# GDPHS_VGA_-_v1_3.net
KiCad netlist of a schematic drawn in EAGLE
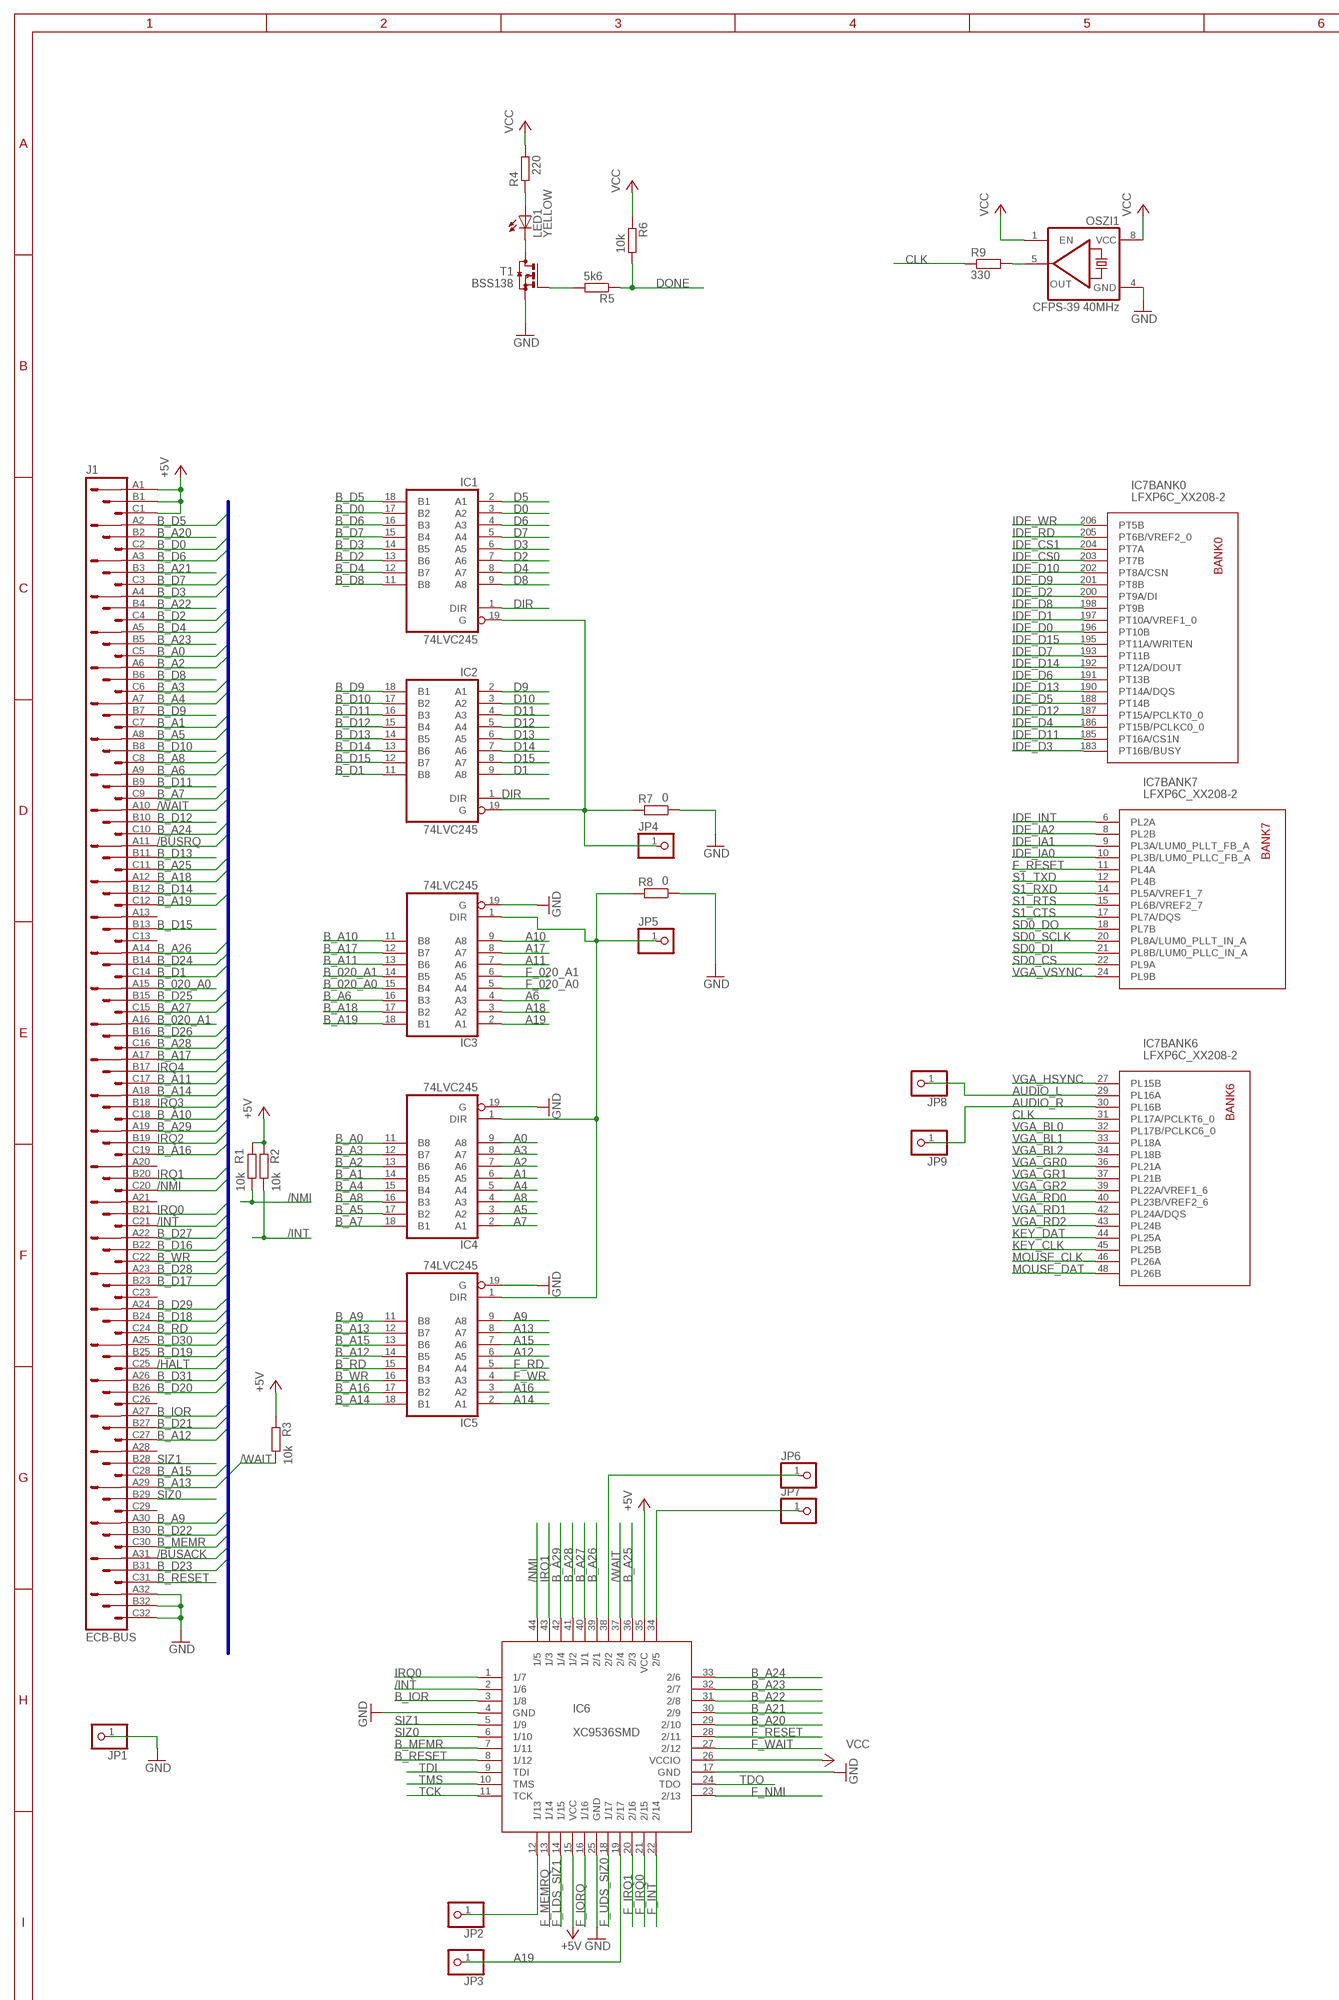
[diagram p0: schematic, sheet 1, part 1 of 2]
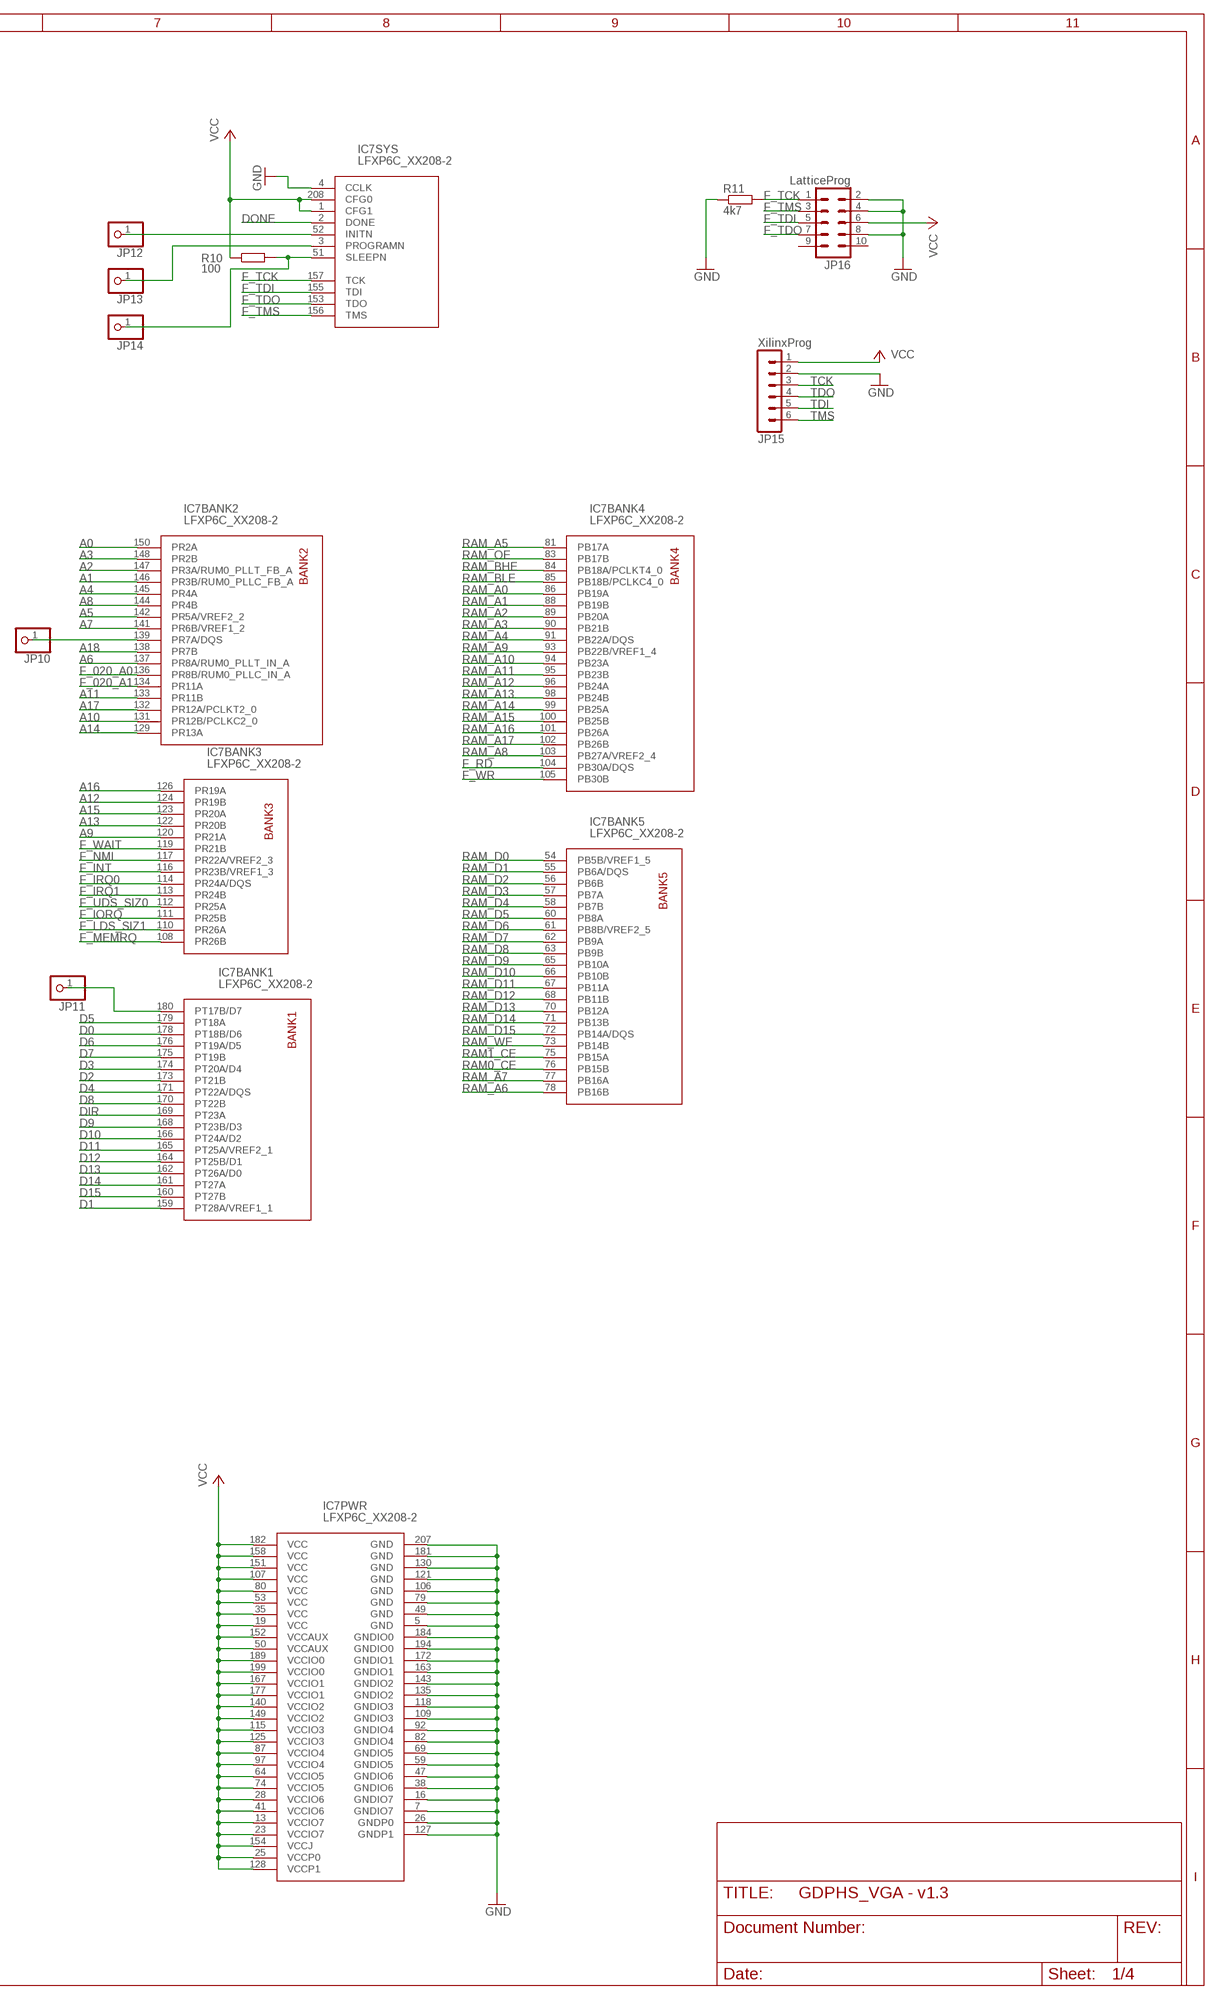
[diagram p1: schematic, sheet 1, part 2 of 2]
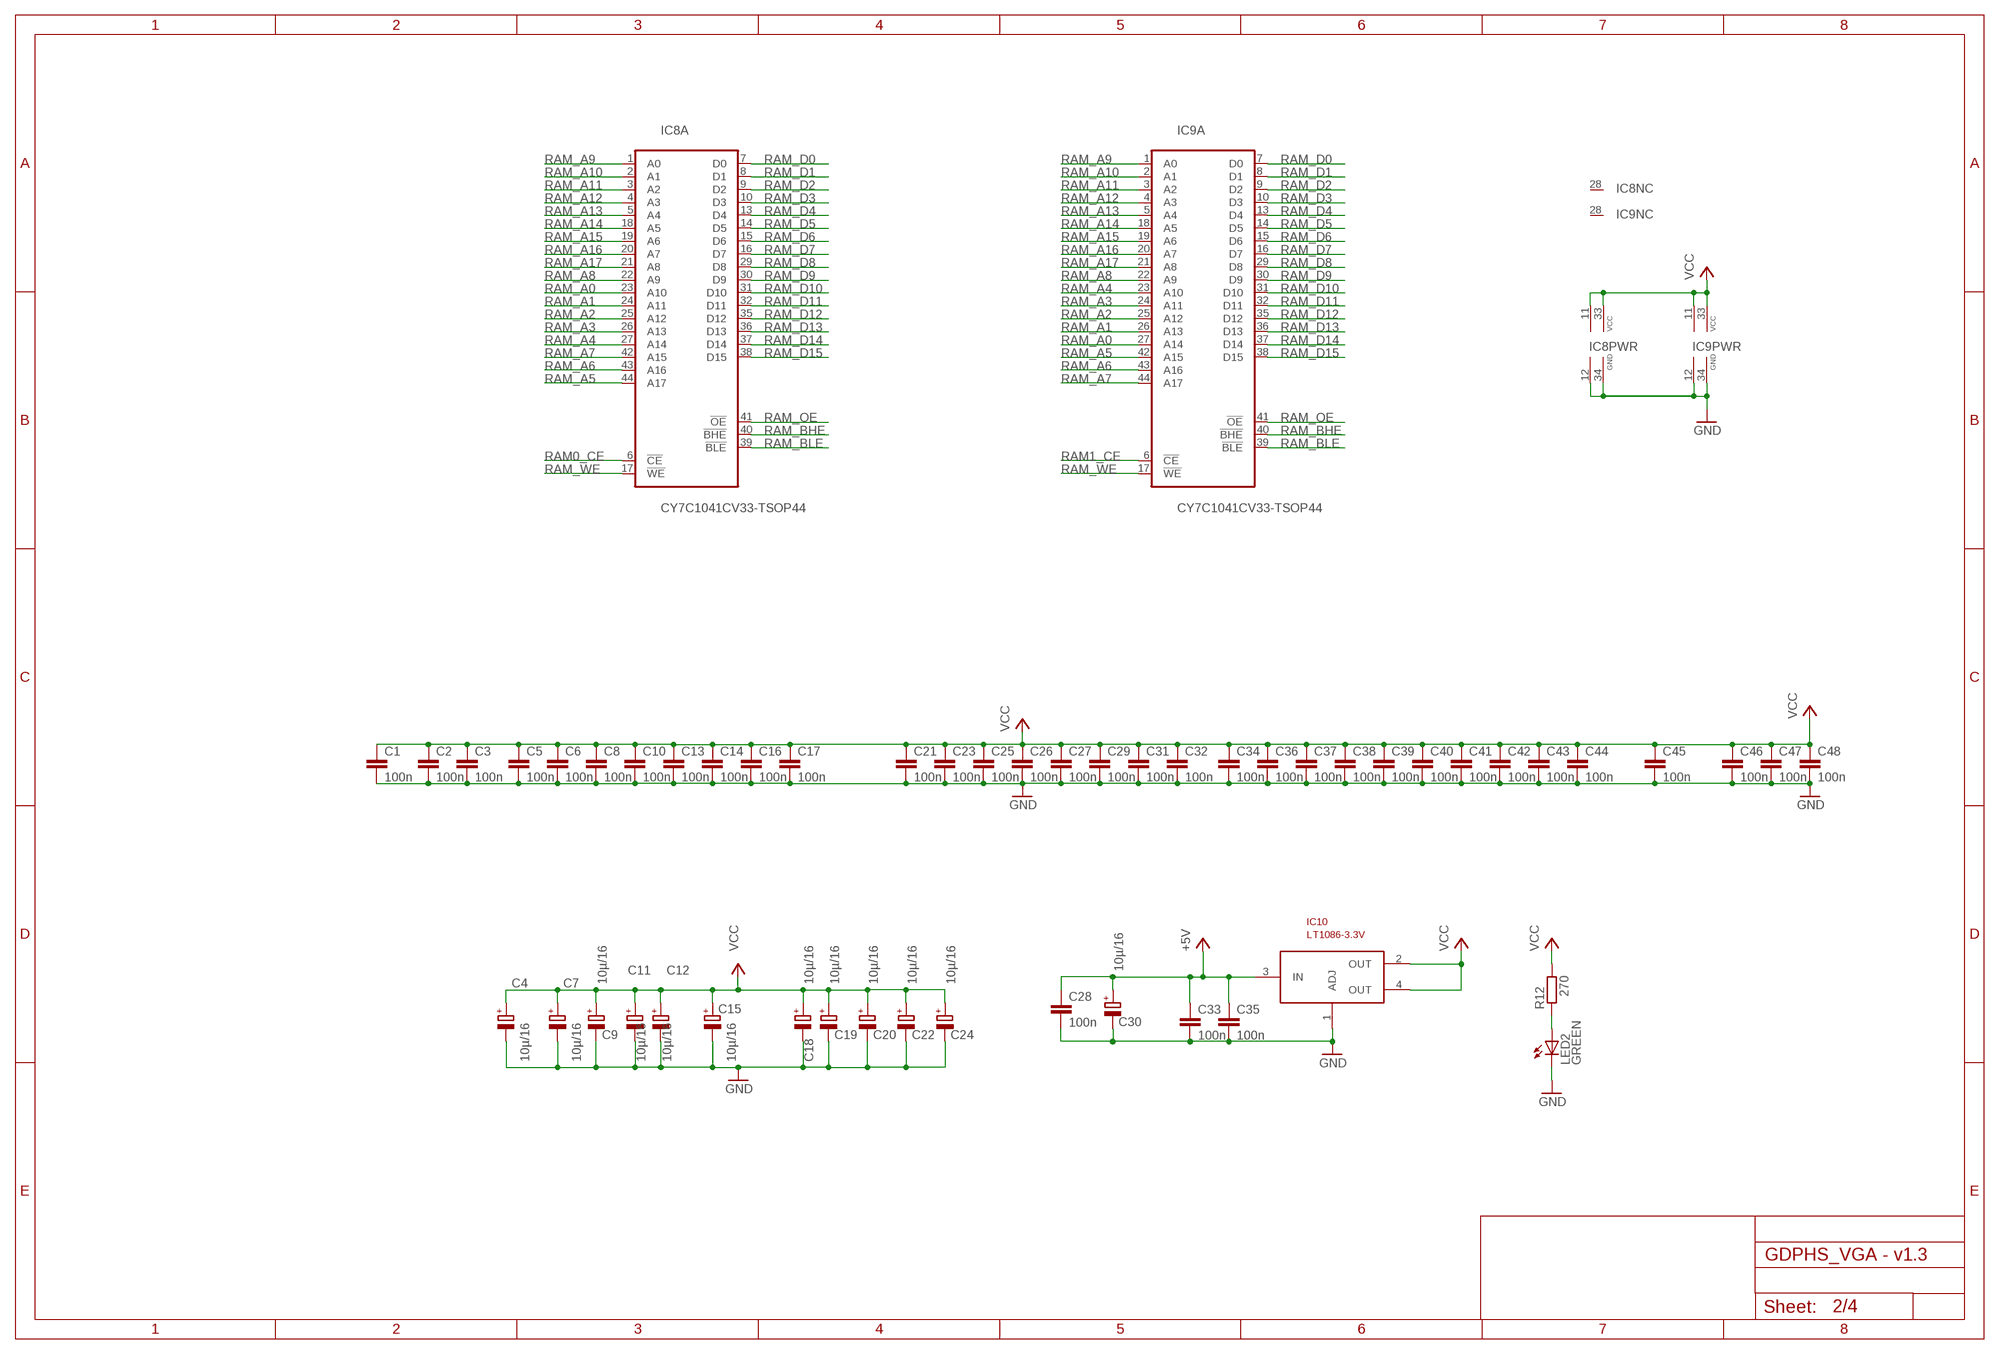
[diagram p2: schematic, sheet 2]
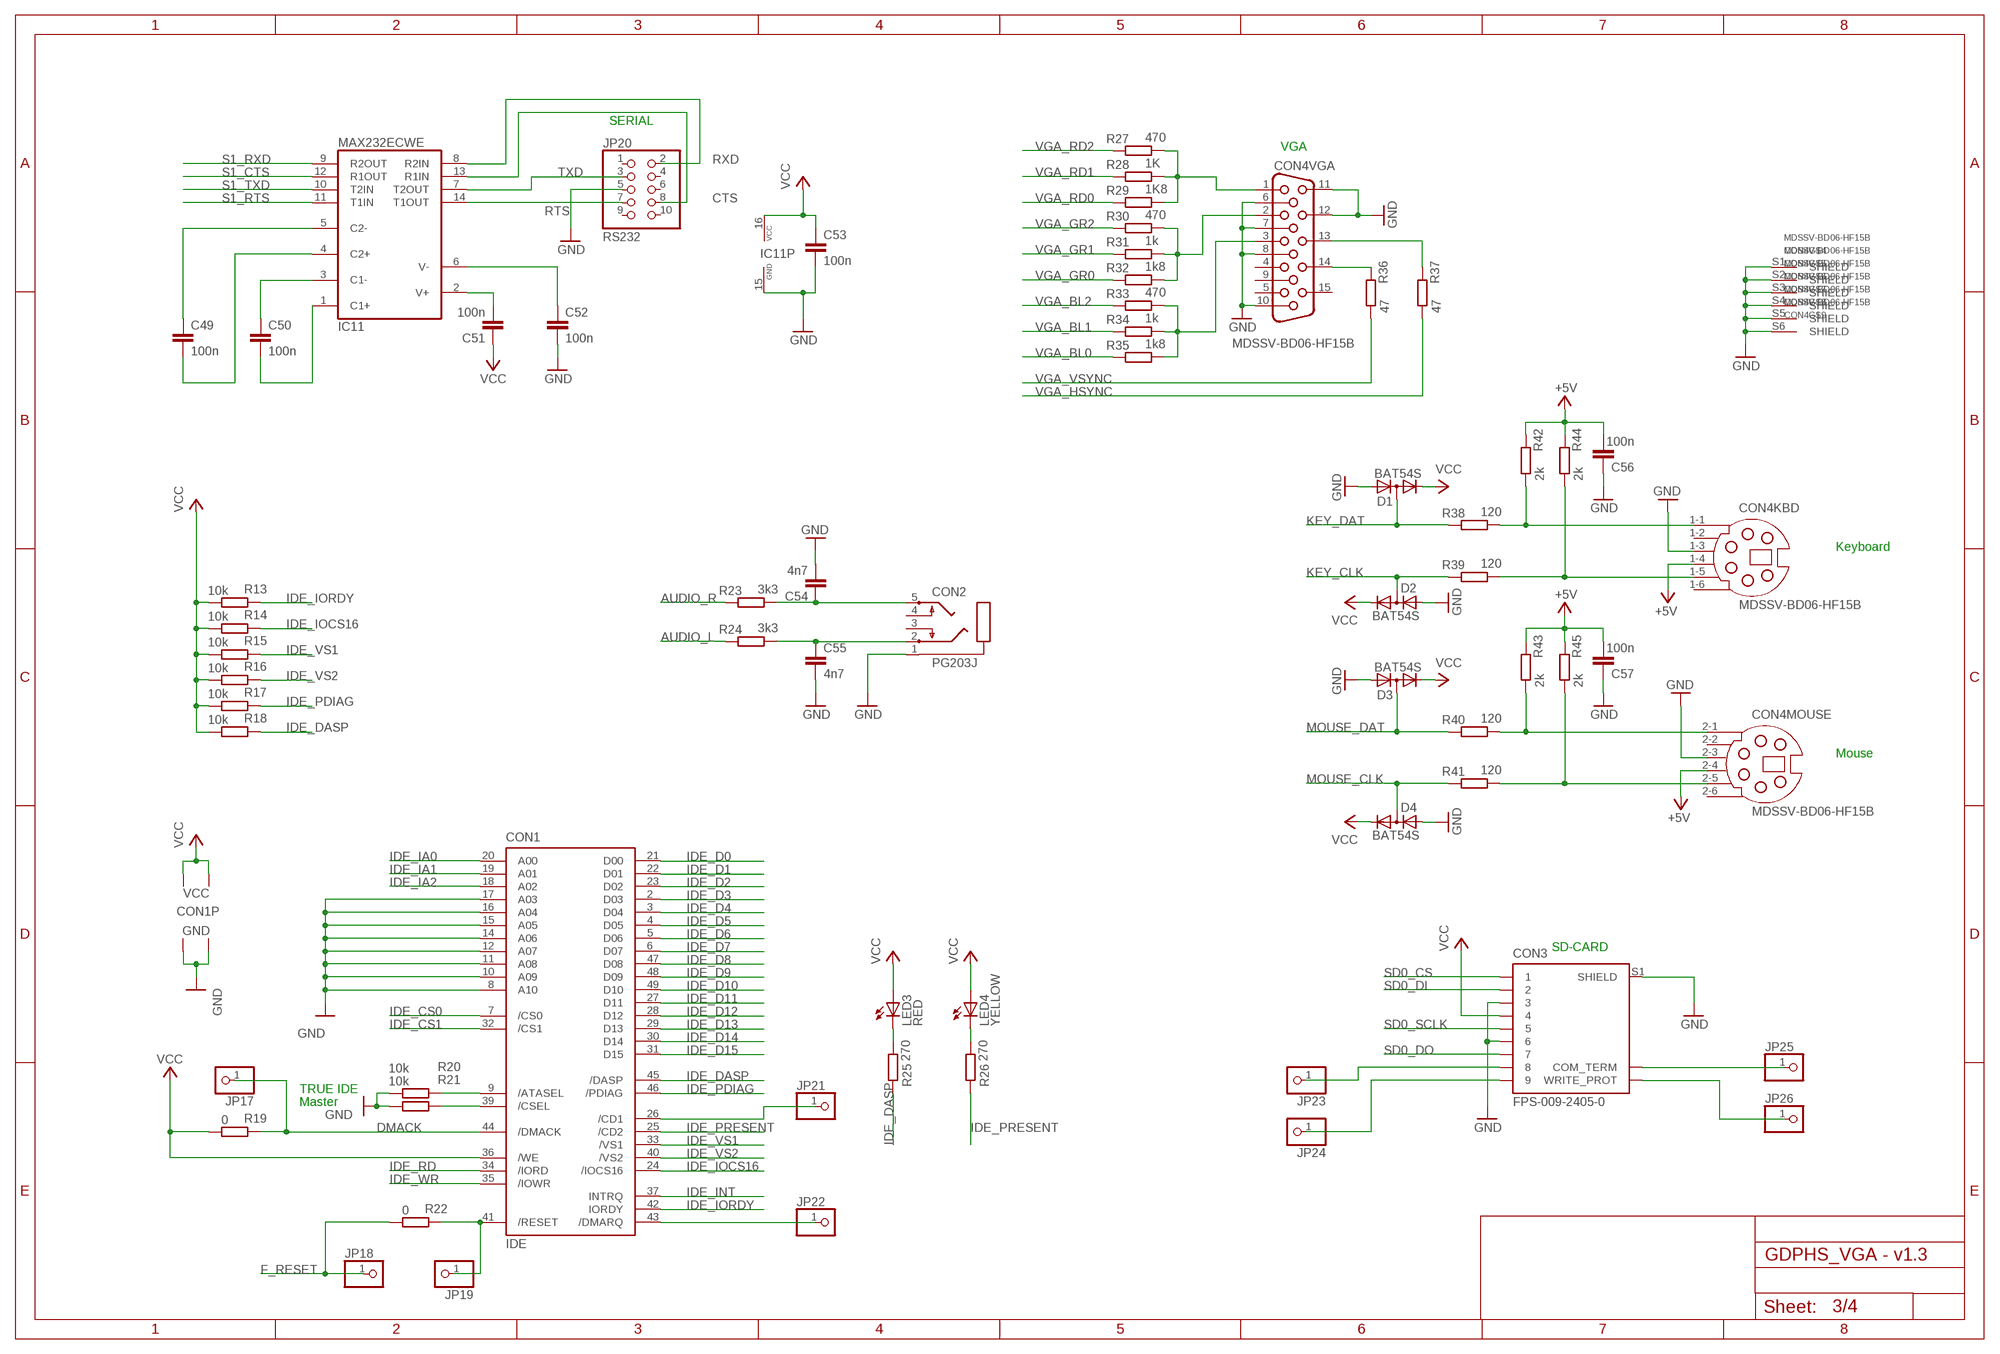
[diagram p3: schematic, sheet 3]
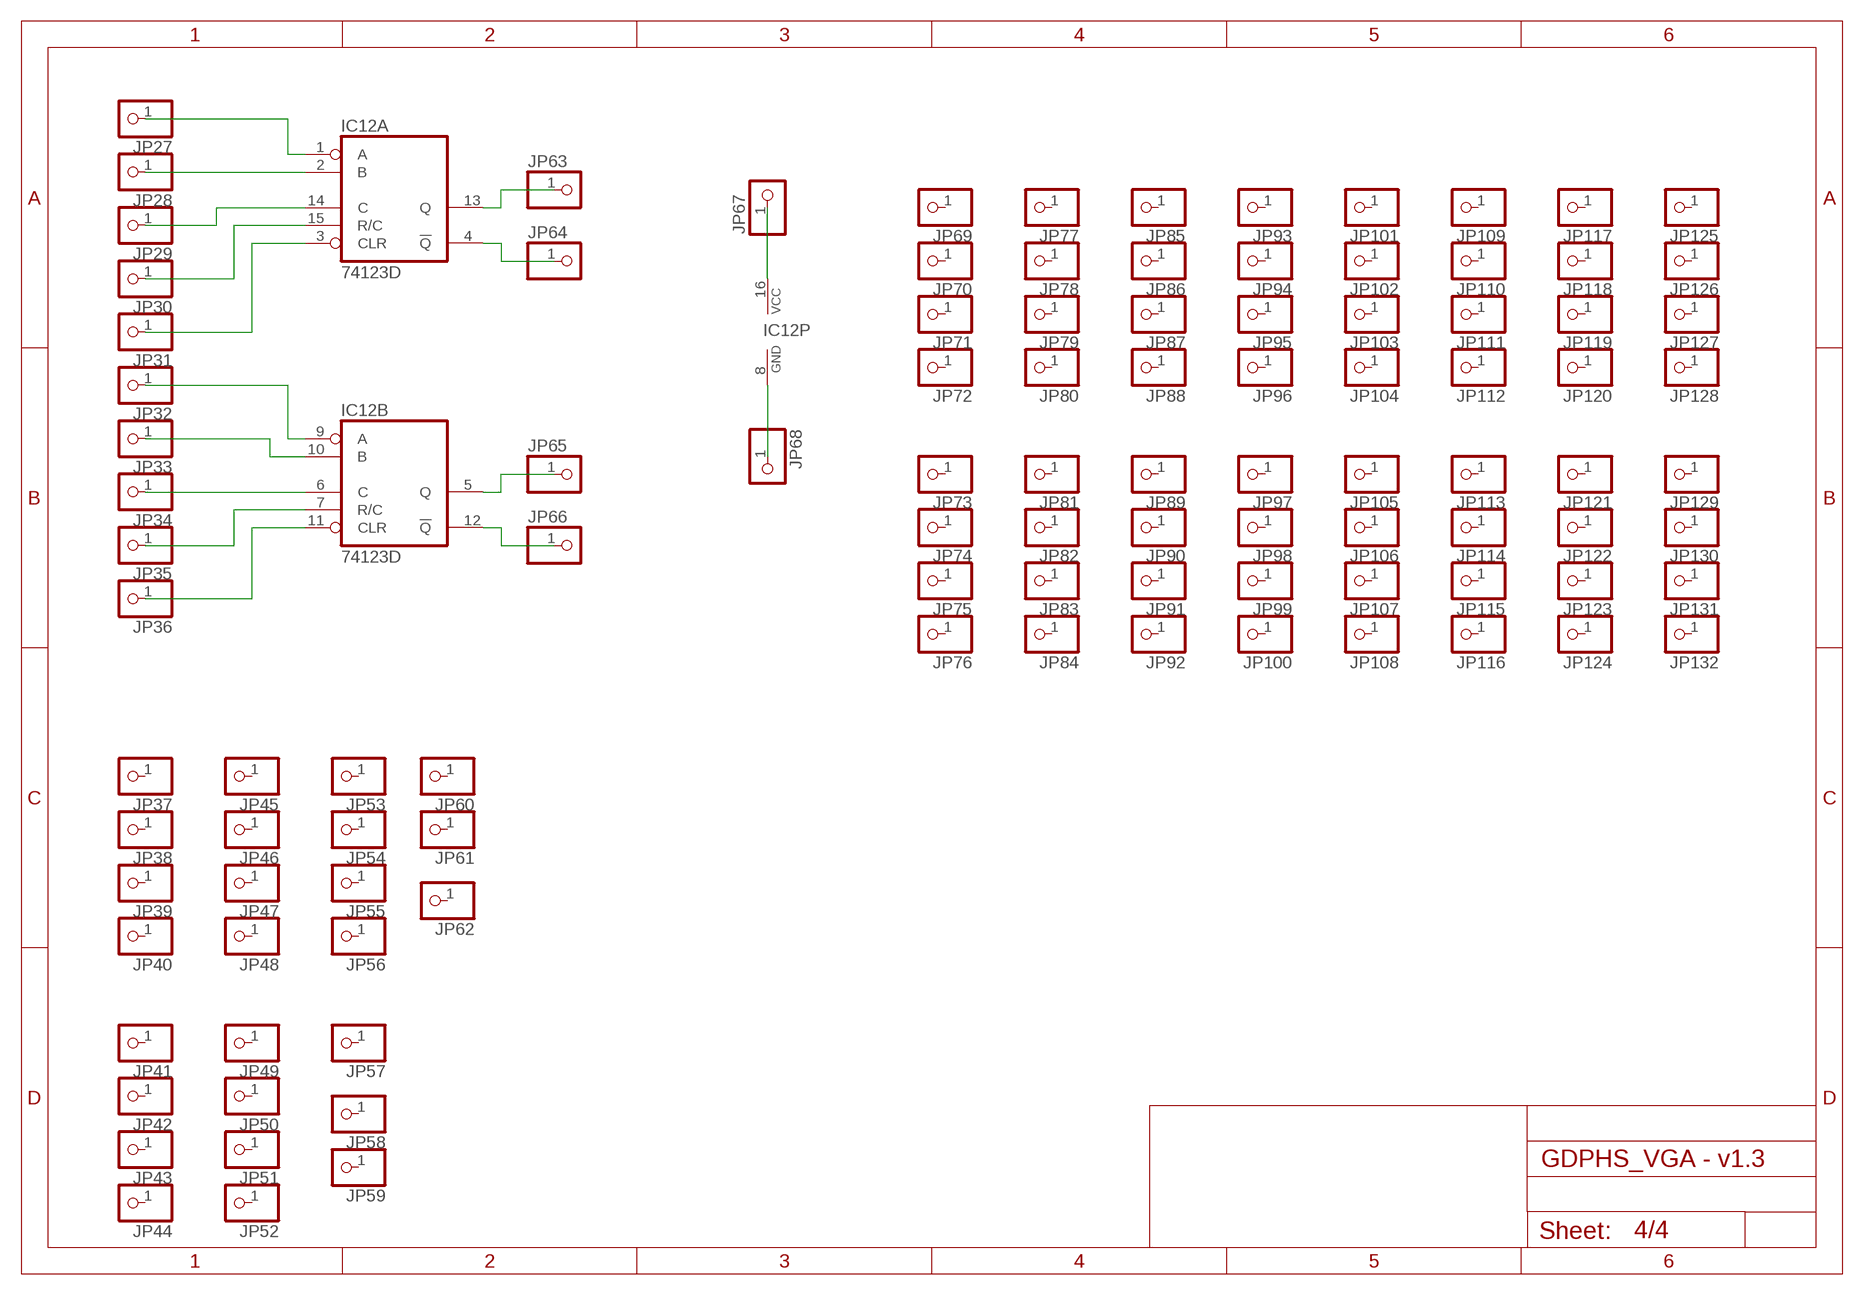
[diagram p4: schematic, sheet 4]

(export (version "E")
  (design (tool "Eeschema 10.0.6"))
  (components
    (comp (ref "IC12")
      (value "74123D")
      (footprint "eagle-import:SO16")
      (libsource (lib "eagle-import") (part "74123D"))
    )
    (comp (ref "JP27")
      (value "PINHD-1X1")
      (footprint "eagle-import:1X01")
      (libsource (lib "eagle-import") (part "PINHD-1X1"))
    )
    (comp (ref "JP28")
      (value "PINHD-1X1")
      (footprint "eagle-import:1X01")
      (libsource (lib "eagle-import") (part "PINHD-1X1"))
    )
    (comp (ref "JP29")
      (value "PINHD-1X1")
      (footprint "eagle-import:1X01")
      (libsource (lib "eagle-import") (part "PINHD-1X1"))
    )
    (comp (ref "JP30")
      (value "PINHD-1X1")
      (footprint "eagle-import:1X01")
      (libsource (lib "eagle-import") (part "PINHD-1X1"))
    )
    (comp (ref "JP31")
      (value "PINHD-1X1")
      (footprint "eagle-import:1X01")
      (libsource (lib "eagle-import") (part "PINHD-1X1"))
    )
    (comp (ref "JP32")
      (value "PINHD-1X1")
      (footprint "eagle-import:1X01")
      (libsource (lib "eagle-import") (part "PINHD-1X1"))
    )
    (comp (ref "JP33")
      (value "PINHD-1X1")
      (footprint "eagle-import:1X01")
      (libsource (lib "eagle-import") (part "PINHD-1X1"))
    )
    (comp (ref "JP34")
      (value "PINHD-1X1")
      (footprint "eagle-import:1X01")
      (libsource (lib "eagle-import") (part "PINHD-1X1"))
    )
    (comp (ref "JP35")
      (value "PINHD-1X1")
      (footprint "eagle-import:1X01")
      (libsource (lib "eagle-import") (part "PINHD-1X1"))
    )
    (comp (ref "JP36")
      (value "PINHD-1X1")
      (footprint "eagle-import:1X01")
      (libsource (lib "eagle-import") (part "PINHD-1X1"))
    )
    (comp (ref "JP37")
      (value "PINHD-1X1")
      (footprint "eagle-import:1X01")
      (libsource (lib "eagle-import") (part "PINHD-1X1"))
    )
    (comp (ref "JP38")
      (value "PINHD-1X1")
      (footprint "eagle-import:1X01")
      (libsource (lib "eagle-import") (part "PINHD-1X1"))
    )
    (comp (ref "JP39")
      (value "PINHD-1X1")
      (footprint "eagle-import:1X01")
      (libsource (lib "eagle-import") (part "PINHD-1X1"))
    )
    (comp (ref "JP40")
      (value "PINHD-1X1")
      (footprint "eagle-import:1X01")
      (libsource (lib "eagle-import") (part "PINHD-1X1"))
    )
    (comp (ref "JP41")
      (value "PINHD-1X1")
      (footprint "eagle-import:1X01")
      (libsource (lib "eagle-import") (part "PINHD-1X1"))
    )
    (comp (ref "JP42")
      (value "PINHD-1X1")
      (footprint "eagle-import:1X01")
      (libsource (lib "eagle-import") (part "PINHD-1X1"))
    )
    (comp (ref "JP43")
      (value "PINHD-1X1")
      (footprint "eagle-import:1X01")
      (libsource (lib "eagle-import") (part "PINHD-1X1"))
    )
    (comp (ref "JP44")
      (value "PINHD-1X1")
      (footprint "eagle-import:1X01")
      (libsource (lib "eagle-import") (part "PINHD-1X1"))
    )
    (comp (ref "JP45")
      (value "PINHD-1X1")
      (footprint "eagle-import:1X01")
      (libsource (lib "eagle-import") (part "PINHD-1X1"))
    )
    (comp (ref "JP46")
      (value "PINHD-1X1")
      (footprint "eagle-import:1X01")
      (libsource (lib "eagle-import") (part "PINHD-1X1"))
    )
    (comp (ref "JP47")
      (value "PINHD-1X1")
      (footprint "eagle-import:1X01")
      (libsource (lib "eagle-import") (part "PINHD-1X1"))
    )
    (comp (ref "JP48")
      (value "PINHD-1X1")
      (footprint "eagle-import:1X01")
      (libsource (lib "eagle-import") (part "PINHD-1X1"))
    )
    (comp (ref "JP49")
      (value "PINHD-1X1")
      (footprint "eagle-import:1X01")
      (libsource (lib "eagle-import") (part "PINHD-1X1"))
    )
    (comp (ref "JP50")
      (value "PINHD-1X1")
      (footprint "eagle-import:1X01")
      (libsource (lib "eagle-import") (part "PINHD-1X1"))
    )
    (comp (ref "JP51")
      (value "PINHD-1X1")
      (footprint "eagle-import:1X01")
      (libsource (lib "eagle-import") (part "PINHD-1X1"))
    )
    (comp (ref "JP52")
      (value "PINHD-1X1")
      (footprint "eagle-import:1X01")
      (libsource (lib "eagle-import") (part "PINHD-1X1"))
    )
    (comp (ref "JP53")
      (value "PINHD-1X1")
      (footprint "eagle-import:1X01")
      (libsource (lib "eagle-import") (part "PINHD-1X1"))
    )
    (comp (ref "JP54")
      (value "PINHD-1X1")
      (footprint "eagle-import:1X01")
      (libsource (lib "eagle-import") (part "PINHD-1X1"))
    )
    (comp (ref "JP55")
      (value "PINHD-1X1")
      (footprint "eagle-import:1X01")
      (libsource (lib "eagle-import") (part "PINHD-1X1"))
    )
    (comp (ref "JP56")
      (value "PINHD-1X1")
      (footprint "eagle-import:1X01")
      (libsource (lib "eagle-import") (part "PINHD-1X1"))
    )
    (comp (ref "JP57")
      (value "PINHD-1X1")
      (footprint "eagle-import:1X01")
      (libsource (lib "eagle-import") (part "PINHD-1X1"))
    )
    (comp (ref "JP58")
      (value "PINHD-1X1")
      (footprint "eagle-import:1X01")
      (libsource (lib "eagle-import") (part "PINHD-1X1"))
    )
    (comp (ref "JP59")
      (value "PINHD-1X1")
      (footprint "eagle-import:1X01")
      (libsource (lib "eagle-import") (part "PINHD-1X1"))
    )
    (comp (ref "JP60")
      (value "PINHD-1X1")
      (footprint "eagle-import:1X01")
      (libsource (lib "eagle-import") (part "PINHD-1X1"))
    )
    (comp (ref "JP61")
      (value "PINHD-1X1")
      (footprint "eagle-import:1X01")
      (libsource (lib "eagle-import") (part "PINHD-1X1"))
    )
    (comp (ref "JP62")
      (value "PINHD-1X1")
      (footprint "eagle-import:1X01")
      (libsource (lib "eagle-import") (part "PINHD-1X1"))
    )
    (comp (ref "JP63")
      (value "PINHD-1X1")
      (footprint "eagle-import:1X01")
      (libsource (lib "eagle-import") (part "PINHD-1X1"))
    )
    (comp (ref "JP64")
      (value "PINHD-1X1")
      (footprint "eagle-import:1X01")
      (libsource (lib "eagle-import") (part "PINHD-1X1"))
    )
    (comp (ref "JP65")
      (value "PINHD-1X1")
      (footprint "eagle-import:1X01")
      (libsource (lib "eagle-import") (part "PINHD-1X1"))
    )
    (comp (ref "JP66")
      (value "PINHD-1X1")
      (footprint "eagle-import:1X01")
      (libsource (lib "eagle-import") (part "PINHD-1X1"))
    )
    (comp (ref "JP67")
      (value "PINHD-1X1")
      (footprint "eagle-import:1X01")
      (libsource (lib "eagle-import") (part "PINHD-1X1"))
    )
    (comp (ref "JP68")
      (value "PINHD-1X1")
      (footprint "eagle-import:1X01")
      (libsource (lib "eagle-import") (part "PINHD-1X1"))
    )
    (comp (ref "JP69")
      (value "PINHD-1X1")
      (footprint "eagle-import:1X01")
      (libsource (lib "eagle-import") (part "PINHD-1X1"))
    )
    (comp (ref "JP70")
      (value "PINHD-1X1")
      (footprint "eagle-import:1X01")
      (libsource (lib "eagle-import") (part "PINHD-1X1"))
    )
    (comp (ref "JP71")
      (value "PINHD-1X1")
      (footprint "eagle-import:1X01")
      (libsource (lib "eagle-import") (part "PINHD-1X1"))
    )
    (comp (ref "JP72")
      (value "PINHD-1X1")
      (footprint "eagle-import:1X01")
      (libsource (lib "eagle-import") (part "PINHD-1X1"))
    )
    (comp (ref "JP73")
      (value "PINHD-1X1")
      (footprint "eagle-import:1X01")
      (libsource (lib "eagle-import") (part "PINHD-1X1"))
    )
    (comp (ref "JP74")
      (value "PINHD-1X1")
      (footprint "eagle-import:1X01")
      (libsource (lib "eagle-import") (part "PINHD-1X1"))
    )
    (comp (ref "JP75")
      (value "PINHD-1X1")
      (footprint "eagle-import:1X01")
      (libsource (lib "eagle-import") (part "PINHD-1X1"))
    )
    (comp (ref "JP76")
      (value "PINHD-1X1")
      (footprint "eagle-import:1X01")
      (libsource (lib "eagle-import") (part "PINHD-1X1"))
    )
    (comp (ref "JP77")
      (value "PINHD-1X1")
      (footprint "eagle-import:1X01")
      (libsource (lib "eagle-import") (part "PINHD-1X1"))
    )
    (comp (ref "JP78")
      (value "PINHD-1X1")
      (footprint "eagle-import:1X01")
      (libsource (lib "eagle-import") (part "PINHD-1X1"))
    )
    (comp (ref "JP79")
      (value "PINHD-1X1")
      (footprint "eagle-import:1X01")
      (libsource (lib "eagle-import") (part "PINHD-1X1"))
    )
    (comp (ref "JP80")
      (value "PINHD-1X1")
      (footprint "eagle-import:1X01")
      (libsource (lib "eagle-import") (part "PINHD-1X1"))
    )
    (comp (ref "JP81")
      (value "PINHD-1X1")
      (footprint "eagle-import:1X01")
      (libsource (lib "eagle-import") (part "PINHD-1X1"))
    )
    (comp (ref "JP82")
      (value "PINHD-1X1")
      (footprint "eagle-import:1X01")
      (libsource (lib "eagle-import") (part "PINHD-1X1"))
    )
    (comp (ref "JP83")
      (value "PINHD-1X1")
      (footprint "eagle-import:1X01")
      (libsource (lib "eagle-import") (part "PINHD-1X1"))
    )
    (comp (ref "JP84")
      (value "PINHD-1X1")
      (footprint "eagle-import:1X01")
      (libsource (lib "eagle-import") (part "PINHD-1X1"))
    )
    (comp (ref "JP85")
      (value "PINHD-1X1")
      (footprint "eagle-import:1X01")
      (libsource (lib "eagle-import") (part "PINHD-1X1"))
    )
    (comp (ref "JP86")
      (value "PINHD-1X1")
      (footprint "eagle-import:1X01")
      (libsource (lib "eagle-import") (part "PINHD-1X1"))
    )
    (comp (ref "JP87")
      (value "PINHD-1X1")
      (footprint "eagle-import:1X01")
      (libsource (lib "eagle-import") (part "PINHD-1X1"))
    )
    (comp (ref "JP88")
      (value "PINHD-1X1")
      (footprint "eagle-import:1X01")
      (libsource (lib "eagle-import") (part "PINHD-1X1"))
    )
    (comp (ref "JP89")
      (value "PINHD-1X1")
      (footprint "eagle-import:1X01")
      (libsource (lib "eagle-import") (part "PINHD-1X1"))
    )
    (comp (ref "JP90")
      (value "PINHD-1X1")
      (footprint "eagle-import:1X01")
      (libsource (lib "eagle-import") (part "PINHD-1X1"))
    )
    (comp (ref "JP91")
      (value "PINHD-1X1")
      (footprint "eagle-import:1X01")
      (libsource (lib "eagle-import") (part "PINHD-1X1"))
    )
    (comp (ref "JP92")
      (value "PINHD-1X1")
      (footprint "eagle-import:1X01")
      (libsource (lib "eagle-import") (part "PINHD-1X1"))
    )
    (comp (ref "JP93")
      (value "PINHD-1X1")
      (footprint "eagle-import:1X01")
      (libsource (lib "eagle-import") (part "PINHD-1X1"))
    )
    (comp (ref "JP94")
      (value "PINHD-1X1")
      (footprint "eagle-import:1X01")
      (libsource (lib "eagle-import") (part "PINHD-1X1"))
    )
    (comp (ref "JP95")
      (value "PINHD-1X1")
      (footprint "eagle-import:1X01")
      (libsource (lib "eagle-import") (part "PINHD-1X1"))
    )
    (comp (ref "JP96")
      (value "PINHD-1X1")
      (footprint "eagle-import:1X01")
      (libsource (lib "eagle-import") (part "PINHD-1X1"))
    )
    (comp (ref "JP97")
      (value "PINHD-1X1")
      (footprint "eagle-import:1X01")
      (libsource (lib "eagle-import") (part "PINHD-1X1"))
    )
    (comp (ref "JP98")
      (value "PINHD-1X1")
      (footprint "eagle-import:1X01")
      (libsource (lib "eagle-import") (part "PINHD-1X1"))
    )
    (comp (ref "JP99")
      (value "PINHD-1X1")
      (footprint "eagle-import:1X01")
      (libsource (lib "eagle-import") (part "PINHD-1X1"))
    )
    (comp (ref "JP100")
      (value "PINHD-1X1")
      (footprint "eagle-import:1X01")
      (libsource (lib "eagle-import") (part "PINHD-1X1"))
    )
    (comp (ref "JP101")
      (value "PINHD-1X1")
      (footprint "eagle-import:1X01")
      (libsource (lib "eagle-import") (part "PINHD-1X1"))
    )
    (comp (ref "JP102")
      (value "PINHD-1X1")
      (footprint "eagle-import:1X01")
      (libsource (lib "eagle-import") (part "PINHD-1X1"))
    )
    (comp (ref "JP103")
      (value "PINHD-1X1")
      (footprint "eagle-import:1X01")
      (libsource (lib "eagle-import") (part "PINHD-1X1"))
    )
    (comp (ref "JP104")
      (value "PINHD-1X1")
      (footprint "eagle-import:1X01")
      (libsource (lib "eagle-import") (part "PINHD-1X1"))
    )
    (comp (ref "JP105")
      (value "PINHD-1X1")
      (footprint "eagle-import:1X01")
      (libsource (lib "eagle-import") (part "PINHD-1X1"))
    )
    (comp (ref "JP106")
      (value "PINHD-1X1")
      (footprint "eagle-import:1X01")
      (libsource (lib "eagle-import") (part "PINHD-1X1"))
    )
    (comp (ref "JP107")
      (value "PINHD-1X1")
      (footprint "eagle-import:1X01")
      (libsource (lib "eagle-import") (part "PINHD-1X1"))
    )
    (comp (ref "JP108")
      (value "PINHD-1X1")
      (footprint "eagle-import:1X01")
      (libsource (lib "eagle-import") (part "PINHD-1X1"))
    )
    (comp (ref "JP109")
      (value "PINHD-1X1")
      (footprint "eagle-import:1X01")
      (libsource (lib "eagle-import") (part "PINHD-1X1"))
    )
    (comp (ref "JP110")
      (value "PINHD-1X1")
      (footprint "eagle-import:1X01")
      (libsource (lib "eagle-import") (part "PINHD-1X1"))
    )
    (comp (ref "JP111")
      (value "PINHD-1X1")
      (footprint "eagle-import:1X01")
      (libsource (lib "eagle-import") (part "PINHD-1X1"))
    )
    (comp (ref "JP112")
      (value "PINHD-1X1")
      (footprint "eagle-import:1X01")
      (libsource (lib "eagle-import") (part "PINHD-1X1"))
    )
    (comp (ref "JP113")
      (value "PINHD-1X1")
      (footprint "eagle-import:1X01")
      (libsource (lib "eagle-import") (part "PINHD-1X1"))
    )
    (comp (ref "JP114")
      (value "PINHD-1X1")
      (footprint "eagle-import:1X01")
      (libsource (lib "eagle-import") (part "PINHD-1X1"))
    )
    (comp (ref "JP115")
      (value "PINHD-1X1")
      (footprint "eagle-import:1X01")
      (libsource (lib "eagle-import") (part "PINHD-1X1"))
    )
    (comp (ref "JP116")
      (value "PINHD-1X1")
      (footprint "eagle-import:1X01")
      (libsource (lib "eagle-import") (part "PINHD-1X1"))
    )
    (comp (ref "JP117")
      (value "PINHD-1X1")
      (footprint "eagle-import:1X01")
      (libsource (lib "eagle-import") (part "PINHD-1X1"))
    )
    (comp (ref "JP118")
      (value "PINHD-1X1")
      (footprint "eagle-import:1X01")
      (libsource (lib "eagle-import") (part "PINHD-1X1"))
    )
    (comp (ref "JP119")
      (value "PINHD-1X1")
      (footprint "eagle-import:1X01")
      (libsource (lib "eagle-import") (part "PINHD-1X1"))
    )
    (comp (ref "JP120")
      (value "PINHD-1X1")
      (footprint "eagle-import:1X01")
      (libsource (lib "eagle-import") (part "PINHD-1X1"))
    )
    (comp (ref "JP121")
      (value "PINHD-1X1")
      (footprint "eagle-import:1X01")
      (libsource (lib "eagle-import") (part "PINHD-1X1"))
    )
    (comp (ref "JP122")
      (value "PINHD-1X1")
      (footprint "eagle-import:1X01")
      (libsource (lib "eagle-import") (part "PINHD-1X1"))
    )
    (comp (ref "JP123")
      (value "PINHD-1X1")
      (footprint "eagle-import:1X01")
      (libsource (lib "eagle-import") (part "PINHD-1X1"))
    )
    (comp (ref "JP124")
      (value "PINHD-1X1")
      (footprint "eagle-import:1X01")
      (libsource (lib "eagle-import") (part "PINHD-1X1"))
    )
    (comp (ref "JP125")
      (value "PINHD-1X1")
      (footprint "eagle-import:1X01")
      (libsource (lib "eagle-import") (part "PINHD-1X1"))
    )
    (comp (ref "JP126")
      (value "PINHD-1X1")
      (footprint "eagle-import:1X01")
      (libsource (lib "eagle-import") (part "PINHD-1X1"))
    )
    (comp (ref "JP127")
      (value "PINHD-1X1")
      (footprint "eagle-import:1X01")
      (libsource (lib "eagle-import") (part "PINHD-1X1"))
    )
    (comp (ref "JP128")
      (value "PINHD-1X1")
      (footprint "eagle-import:1X01")
      (libsource (lib "eagle-import") (part "PINHD-1X1"))
    )
    (comp (ref "JP129")
      (value "PINHD-1X1")
      (footprint "eagle-import:1X01")
      (libsource (lib "eagle-import") (part "PINHD-1X1"))
    )
    (comp (ref "JP130")
      (value "PINHD-1X1")
      (footprint "eagle-import:1X01")
      (libsource (lib "eagle-import") (part "PINHD-1X1"))
    )
    (comp (ref "JP131")
      (value "PINHD-1X1")
      (footprint "eagle-import:1X01")
      (libsource (lib "eagle-import") (part "PINHD-1X1"))
    )
    (comp (ref "JP132")
      (value "PINHD-1X1")
      (footprint "eagle-import:1X01")
      (libsource (lib "eagle-import") (part "PINHD-1X1"))
    )
    (comp (ref "C1")
      (value "100n")
      (footprint "eagle-import:C0805")
      (libsource (lib "eagle-import") (part "C-EUC0805"))
    )
    (comp (ref "C2")
      (value "100n")
      (footprint "eagle-import:C0805")
      (libsource (lib "eagle-import") (part "C-EUC0805"))
    )
    (comp (ref "C3")
      (value "100n")
      (footprint "eagle-import:C0805")
      (libsource (lib "eagle-import") (part "C-EUC0805"))
    )
    (comp (ref "C4")
      (value "10µ/16")
      (footprint "eagle-import:SMC_C")
      (libsource (lib "eagle-import") (part "CPOL-EUSMCC"))
    )
    (comp (ref "C5")
      (value "100n")
      (footprint "eagle-import:C0805")
      (libsource (lib "eagle-import") (part "C-EUC0805"))
    )
    (comp (ref "C6")
      (value "100n")
      (footprint "eagle-import:C0805")
      (libsource (lib "eagle-import") (part "C-EUC0805"))
    )
    (comp (ref "C7")
      (value "10µ/16")
      (footprint "eagle-import:SMC_C")
      (libsource (lib "eagle-import") (part "CPOL-EUSMCC"))
    )
    (comp (ref "C8")
      (value "100n")
      (footprint "eagle-import:C0805")
      (libsource (lib "eagle-import") (part "C-EUC0805"))
    )
    (comp (ref "C9")
      (value "10µ/16")
      (footprint "eagle-import:SMC_C")
      (libsource (lib "eagle-import") (part "CPOL-EUSMCC"))
    )
    (comp (ref "C10")
      (value "100n")
      (footprint "eagle-import:C0805")
      (libsource (lib "eagle-import") (part "C-EUC0805"))
    )
    (comp (ref "C11")
      (value "10µ/16")
      (footprint "eagle-import:SMC_C")
      (libsource (lib "eagle-import") (part "CPOL-EUSMCC"))
    )
    (comp (ref "C12")
      (value "10µ/16")
      (footprint "eagle-import:SMC_C")
      (libsource (lib "eagle-import") (part "CPOL-EUSMCC"))
    )
    (comp (ref "C13")
      (value "100n")
      (footprint "eagle-import:C0805")
      (libsource (lib "eagle-import") (part "C-EUC0805"))
    )
    (comp (ref "C14")
      (value "100n")
      (footprint "eagle-import:C0805")
      (libsource (lib "eagle-import") (part "C-EUC0805"))
    )
    (comp (ref "C15")
      (value "10µ/16")
      (footprint "eagle-import:SMC_C")
      (libsource (lib "eagle-import") (part "CPOL-EUSMCC"))
    )
    (comp (ref "C16")
      (value "100n")
      (footprint "eagle-import:C0805")
      (libsource (lib "eagle-import") (part "C-EUC0805"))
    )
    (comp (ref "C17")
      (value "100n")
      (footprint "eagle-import:C0805")
      (libsource (lib "eagle-import") (part "C-EUC0805"))
    )
    (comp (ref "C18")
      (value "10µ/16")
      (footprint "eagle-import:SMC_C")
      (libsource (lib "eagle-import") (part "CPOL-EUSMCC"))
    )
    (comp (ref "C19")
      (value "10µ/16")
      (footprint "eagle-import:SMC_C")
      (libsource (lib "eagle-import") (part "CPOL-EUSMCC"))
    )
    (comp (ref "C20")
      (value "10µ/16")
      (footprint "eagle-import:SMC_C")
      (libsource (lib "eagle-import") (part "CPOL-EUSMCC"))
    )
    (comp (ref "C21")
      (value "100n")
      (footprint "eagle-import:C0805")
      (libsource (lib "eagle-import") (part "C-EUC0805"))
    )
    (comp (ref "C22")
      (value "10µ/16")
      (footprint "eagle-import:SMC_C")
      (libsource (lib "eagle-import") (part "CPOL-EUSMCC"))
    )
    (comp (ref "C23")
      (value "100n")
      (footprint "eagle-import:C0805")
      (libsource (lib "eagle-import") (part "C-EUC0805"))
    )
    (comp (ref "C24")
      (value "10µ/16")
      (footprint "eagle-import:SMC_C")
      (libsource (lib "eagle-import") (part "CPOL-EUSMCC"))
    )
    (comp (ref "C25")
      (value "100n")
      (footprint "eagle-import:C0805")
      (libsource (lib "eagle-import") (part "C-EUC0805"))
    )
    (comp (ref "C26")
      (value "100n")
      (footprint "eagle-import:C0805")
      (libsource (lib "eagle-import") (part "C-EUC0805"))
    )
    (comp (ref "C27")
      (value "100n")
      (footprint "eagle-import:C0805")
      (libsource (lib "eagle-import") (part "C-EUC0805"))
    )
    (comp (ref "C28")
      (value "100n")
      (footprint "eagle-import:C0805")
      (libsource (lib "eagle-import") (part "C-EUC0805"))
    )
    (comp (ref "C29")
      (value "100n")
      (footprint "eagle-import:C0805")
      (libsource (lib "eagle-import") (part "C-EUC0805"))
    )
    (comp (ref "C30")
      (value "10µ/16")
      (footprint "eagle-import:SMC_C")
      (libsource (lib "eagle-import") (part "CPOL-EUSMCC"))
    )
    (comp (ref "C31")
      (value "100n")
      (footprint "eagle-import:C0805")
      (libsource (lib "eagle-import") (part "C-EUC0805"))
    )
    (comp (ref "C32")
      (value "100n")
      (footprint "eagle-import:C0805")
      (libsource (lib "eagle-import") (part "C-EUC0805"))
    )
    (comp (ref "C33")
      (value "100n")
      (footprint "eagle-import:C0805")
      (libsource (lib "eagle-import") (part "C-EUC0805"))
    )
    (comp (ref "C34")
      (value "100n")
      (footprint "eagle-import:C0805")
      (libsource (lib "eagle-import") (part "C-EUC0805"))
    )
    (comp (ref "C35")
      (value "100n")
      (footprint "eagle-import:C0805")
      (libsource (lib "eagle-import") (part "C-EUC0805"))
    )
    (comp (ref "C36")
      (value "100n")
      (footprint "eagle-import:C0805")
      (libsource (lib "eagle-import") (part "C-EUC0805"))
    )
    (comp (ref "C37")
      (value "100n")
      (footprint "eagle-import:C0805")
      (libsource (lib "eagle-import") (part "C-EUC0805"))
    )
    (comp (ref "C38")
      (value "100n")
      (footprint "eagle-import:C0805")
      (libsource (lib "eagle-import") (part "C-EUC0805"))
    )
    (comp (ref "C39")
      (value "100n")
      (footprint "eagle-import:C0805")
      (libsource (lib "eagle-import") (part "C-EUC0805"))
    )
    (comp (ref "C40")
      (value "100n")
      (footprint "eagle-import:C0805")
      (libsource (lib "eagle-import") (part "C-EUC0805"))
    )
    (comp (ref "C41")
      (value "100n")
      (footprint "eagle-import:C0805")
      (libsource (lib "eagle-import") (part "C-EUC0805"))
    )
    (comp (ref "C42")
      (value "100n")
      (footprint "eagle-import:C0805")
      (libsource (lib "eagle-import") (part "C-EUC0805"))
    )
    (comp (ref "C43")
      (value "100n")
      (footprint "eagle-import:C0805")
      (libsource (lib "eagle-import") (part "C-EUC0805"))
    )
    (comp (ref "C44")
      (value "100n")
      (footprint "eagle-import:C0805")
      (libsource (lib "eagle-import") (part "C-EUC0805"))
    )
    (comp (ref "C45")
      (value "100n")
      (footprint "eagle-import:C0805")
      (libsource (lib "eagle-import") (part "C-EUC0805"))
    )
    (comp (ref "C46")
      (value "100n")
      (footprint "eagle-import:C0805")
      (libsource (lib "eagle-import") (part "C-EUC0805"))
    )
    (comp (ref "C47")
      (value "100n")
      (footprint "eagle-import:C0805")
      (libsource (lib "eagle-import") (part "C-EUC0805"))
    )
    (comp (ref "C48")
      (value "100n")
      (footprint "eagle-import:C0805")
      (libsource (lib "eagle-import") (part "C-EUC0805"))
    )
    (comp (ref "IC8")
      (value "CY7C1041CV33-TSOP44")
      (footprint "eagle-import:TSOP44-400")
      (fields
        (field (name "MF") "Cypress")
        (field (name "MPN") "CY7C1041CV33-10ZSXA")
        (field (name "OC_DIGIKEY") "CY7C1041CV33-10ZSXA-ND")
      )
      (libsource (lib "eagle-import") (part "CY7C1041CV33-TSOP44"))
    )
    (comp (ref "IC9")
      (value "CY7C1041CV33-TSOP44")
      (footprint "eagle-import:TSOP44-400")
      (fields
        (field (name "MF") "Cypress")
        (field (name "MPN") "CY7C1041CV33-10ZSXA")
        (field (name "OC_DIGIKEY") "CY7C1041CV33-10ZSXA-ND")
      )
      (libsource (lib "eagle-import") (part "CY7C1041CV33-TSOP44"))
    )
    (comp (ref "IC10")
      (value "LT1086-3.3V")
      (footprint "eagle-import:MDD")
      (fields (field (name "MF") "Linear Technology") (field (name "MPN") "LT1086CM-3.3#PBF"))
      (libsource (lib "eagle-import") (part "LT1086"))
    )
    (comp (ref "LED2")
      (value "GREEN")
      (footprint "eagle-import:CHIPLED_0805")
      (libsource (lib "eagle-import") (part "LEDCHIPLED_0805"))
    )
    (comp (ref "R12")
      (value "270")
      (footprint "eagle-import:M0805")
      (libsource (lib "eagle-import") (part "R-EU_M0805"))
    )
    (comp (ref "IC1")
      (value "74LVC245")
      (footprint "eagle-import:SO20W")
      (fields
        (field (name "MF") "Texas Instruments")
        (field (name "MPN") "SN74LVC245ADWR")
        (field (name "OC_DIGIKEY") "296-1232-1-ND")
      )
      (libsource (lib "eagle-import") (part "74245DWHCT"))
    )
    (comp (ref "IC2")
      (value "74LVC245")
      (footprint "eagle-import:SO20W")
      (fields
        (field (name "MF") "Texas Instruments")
        (field (name "MPN") "SN74LVC245ADWR")
        (field (name "OC_DIGIKEY") "296-1232-1-ND")
      )
      (libsource (lib "eagle-import") (part "74245DWHCT"))
    )
    (comp (ref "IC3")
      (value "74LVC245")
      (footprint "eagle-import:SO20W")
      (fields
        (field (name "MF") "Texas Instruments")
        (field (name "MF_1") "Texas Instruments")
        (field (name "MPN") "SN74LVC245ADWR")
      )
      (libsource (lib "eagle-import") (part "74245DWHCT"))
    )
    (comp (ref "IC4")
      (value "74LVC245")
      (footprint "eagle-import:SO20W")
      (fields
        (field (name "MF") "Texas Instruments")
        (field (name "MPN") "SN74LVC245ADWR")
        (field (name "OC_DIGIKEY") "296-1232-1-ND")
      )
      (libsource (lib "eagle-import") (part "74245DWHCT"))
    )
    (comp (ref "IC5")
      (value "74LVC245")
      (footprint "eagle-import:SO20W")
      (fields
        (field (name "MF") "Texas Instruments")
        (field (name "MPN") "SN74LVC245ADWR")
        (field (name "OC_DIGIKEY") "296-1232-1-ND")
      )
      (libsource (lib "eagle-import") (part "74245DWHCT"))
    )
    (comp (ref "IC6")
      (value "XC9536SMD")
      (footprint "eagle-import:TQFP44")
      (fields (field (name "MF") "Xilinx") (field (name "MPN") "XC9536-7VQ44C"))
      (libsource (lib "eagle-import") (part "XC9536SMD"))
    )
    (comp (ref "IC7")
      (value "LFXP6C_XX208-2")
      (footprint "eagle-import:PQFP_208")
      (fields
        (field (name "MF") "Lattice Semiconductor")
        (field (name "MPN") "LFXP6C-3QN208C")
        (field (name "OC_DIGIKEY") "220-1261-ND")
      )
      (libsource (lib "eagle-import") (part "LFXP6C_XX208-2"))
    )
    (comp (ref "J1")
      (value "ECB-BUS")
      (footprint "eagle-import:VG96K")
      (libsource (lib "eagle-import") (part "VG96K"))
    )
    (comp (ref "JP1")
      (value "PINHD-1X1")
      (footprint "eagle-import:1X01")
      (libsource (lib "eagle-import") (part "PINHD-1X1"))
    )
    (comp (ref "JP2")
      (value "PINHD-1X1")
      (footprint "eagle-import:1X01")
      (libsource (lib "eagle-import") (part "PINHD-1X1"))
    )
    (comp (ref "JP3")
      (value "PINHD-1X1")
      (footprint "eagle-import:1X01")
      (libsource (lib "eagle-import") (part "PINHD-1X1"))
    )
    (comp (ref "JP4")
      (value "PINHD-1X1")
      (footprint "eagle-import:1X01")
      (libsource (lib "eagle-import") (part "PINHD-1X1"))
    )
    (comp (ref "JP5")
      (value "PINHD-1X1")
      (footprint "eagle-import:1X01")
      (libsource (lib "eagle-import") (part "PINHD-1X1"))
    )
    (comp (ref "JP6")
      (value "PINHD-1X1")
      (footprint "eagle-import:1X01")
      (libsource (lib "eagle-import") (part "PINHD-1X1"))
    )
    (comp (ref "JP7")
      (value "PINHD-1X1")
      (footprint "eagle-import:1X01")
      (libsource (lib "eagle-import") (part "PINHD-1X1"))
    )
    (comp (ref "JP8")
      (value "PINHD-1X1")
      (footprint "eagle-import:1X01")
      (libsource (lib "eagle-import") (part "PINHD-1X1"))
    )
    (comp (ref "JP9")
      (value "PINHD-1X1")
      (footprint "eagle-import:1X01")
      (libsource (lib "eagle-import") (part "PINHD-1X1"))
    )
    (comp (ref "JP10")
      (value "PINHD-1X1")
      (footprint "eagle-import:1X01")
      (libsource (lib "eagle-import") (part "PINHD-1X1"))
    )
    (comp (ref "JP11")
      (value "PINHD-1X1")
      (footprint "eagle-import:1X01")
      (libsource (lib "eagle-import") (part "PINHD-1X1"))
    )
    (comp (ref "JP12")
      (value "PINHD-1X1")
      (footprint "eagle-import:1X01")
      (libsource (lib "eagle-import") (part "PINHD-1X1"))
    )
    (comp (ref "JP13")
      (value "PINHD-1X1")
      (footprint "eagle-import:1X01")
      (libsource (lib "eagle-import") (part "PINHD-1X1"))
    )
    (comp (ref "JP14")
      (value "PINHD-1X1")
      (footprint "eagle-import:1X01")
      (libsource (lib "eagle-import") (part "PINHD-1X1"))
    )
    (comp (ref "JP15")
      (value "XilinxProg")
      (footprint "eagle-import:MA06-1")
      (libsource (lib "eagle-import") (part "MA06-1"))
    )
    (comp (ref "JP16")
      (value "LatticeProg")
      (footprint "eagle-import:MA05-2")
      (libsource (lib "eagle-import") (part "MA05-2"))
    )
    (comp (ref "LED1")
      (value "YELLOW")
      (footprint "eagle-import:CHIPLED_0805")
      (libsource (lib "eagle-import") (part "LEDCHIPLED_0805"))
    )
    (comp (ref "OSZI1")
      (value "CFPS-39 40MHz")
      (footprint "eagle-import:CFPS7X")
      (fields
        (field (name "MF") "    IQD FREQUENCY PRODUCTS")
        (field (name "MPN") "LF SPXO018042 - QUARZ, 40MHZ, 15PF, SMD")
      )
      (libsource (lib "eagle-import") (part "CRYSTAL_RESONATORCFPS7X"))
    )
    (comp (ref "R1")
      (value "10k")
      (footprint "eagle-import:M0805")
      (libsource (lib "eagle-import") (part "R-EU_M0805"))
    )
    (comp (ref "R2")
      (value "10k")
      (footprint "eagle-import:M0805")
      (libsource (lib "eagle-import") (part "R-EU_M0805"))
    )
    (comp (ref "R3")
      (value "10k")
      (footprint "eagle-import:M0805")
      (libsource (lib "eagle-import") (part "R-EU_M0805"))
    )
    (comp (ref "R4")
      (value "220")
      (footprint "eagle-import:M0805")
      (libsource (lib "eagle-import") (part "R-EU_M0805"))
    )
    (comp (ref "R5")
      (value "5k6")
      (footprint "eagle-import:M0805")
      (libsource (lib "eagle-import") (part "R-EU_M0805"))
    )
    (comp (ref "R6")
      (value "10k")
      (footprint "eagle-import:M0805")
      (libsource (lib "eagle-import") (part "R-EU_M0805"))
    )
    (comp (ref "R7")
      (value "0")
      (footprint "eagle-import:M0805")
      (libsource (lib "eagle-import") (part "R-EU_M0805"))
    )
    (comp (ref "R8")
      (value "0")
      (footprint "eagle-import:M0805")
      (libsource (lib "eagle-import") (part "R-EU_M0805"))
    )
    (comp (ref "R9")
      (value "330")
      (footprint "eagle-import:M0805")
      (libsource (lib "eagle-import") (part "R-EU_M0805"))
    )
    (comp (ref "R10")
      (value "100")
      (footprint "eagle-import:M0805")
      (libsource (lib "eagle-import") (part "R-EU_M0805"))
    )
    (comp (ref "R11")
      (value "4k7")
      (footprint "eagle-import:M0805")
      (libsource (lib "eagle-import") (part "R-EU_M0805"))
    )
    (comp (ref "T1")
      (value "BSS138")
      (footprint "eagle-import:SOT23")
      (fields (field (name "MF") "Fairchild Semiconductor"))
      (libsource (lib "eagle-import") (part "BSS123"))
    )
    (comp (ref "C49")
      (value "100n")
      (footprint "eagle-import:C0805")
      (libsource (lib "eagle-import") (part "C-EUC0805"))
    )
    (comp (ref "C50")
      (value "100n")
      (footprint "eagle-import:C0805")
      (libsource (lib "eagle-import") (part "C-EUC0805"))
    )
    (comp (ref "C51")
      (value "100n")
      (footprint "eagle-import:C0805")
      (libsource (lib "eagle-import") (part "C-EUC0805"))
    )
    (comp (ref "C52")
      (value "100n")
      (footprint "eagle-import:C0805")
      (libsource (lib "eagle-import") (part "C-EUC0805"))
    )
    (comp (ref "C53")
      (value "100n")
      (footprint "eagle-import:C0805")
      (libsource (lib "eagle-import") (part "C-EUC0805"))
    )
    (comp (ref "C54")
      (value "4n7")
      (footprint "eagle-import:C0805")
      (libsource (lib "eagle-import") (part "C-EUC0805"))
    )
    (comp (ref "C55")
      (value "4n7")
      (footprint "eagle-import:C0805")
      (libsource (lib "eagle-import") (part "C-EUC0805"))
    )
    (comp (ref "C56")
      (value "100n")
      (footprint "eagle-import:C0805")
      (libsource (lib "eagle-import") (part "C-EUC0805"))
    )
    (comp (ref "C57")
      (value "100n")
      (footprint "eagle-import:C0805")
      (libsource (lib "eagle-import") (part "C-EUC0805"))
    )
    (comp (ref "CON1")
      (value "IDE")
      (footprint "eagle-import:CF-050-P2-X03-10-DS-1")
      (fields
        (field (name "MF") "Yamaichi")
        (field (name "MPN") "CF-050P2-103-10-DS1")
        (field (name "OC_REICHELT") "CONNECTOR CF 02")
      )
      (libsource (lib "eagle-import") (part "CF-CARD-IDE_MODEYAMAI-CF-CARD-I-II"))
    )
    (comp (ref "CON2")
      (value "PG203J")
      (footprint "eagle-import:PG203J")
      (libsource (lib "eagle-import") (part "PG203J"))
    )
    (comp (ref "CON3")
      (value "FPS-009-2405-0")
      (footprint "eagle-import:FPS-009-2405-0")
      (fields (field (name "MF") "Yamaichi"))
      (libsource (lib "eagle-import") (part "FPS-009-2405-0"))
    )
    (comp (ref "CON4")
      (value "MDSSV-BD06-HF15B")
      (footprint "eagle-import:MDSSV-BD06-HF15-B")
      (fields
        (field (name "MF") "Norcomp Inc.")
        (field (name "MPN") "999-H15-PS2L571")
        (field (name "OC_DIGIKEY") "999-H15FA-ND")
      )
      (libsource (lib "eagle-import") (part "MDSSV-BD06-HF15B"))
    )
    (comp (ref "D1")
      (value "BAT54S")
      (footprint "eagle-import:SOT23")
      (libsource (lib "eagle-import") (part "DIODE_2CACA-SOT23"))
    )
    (comp (ref "D2")
      (value "BAT54S")
      (footprint "eagle-import:SOT23")
      (libsource (lib "eagle-import") (part "DIODE_2CACA-SOT23"))
    )
    (comp (ref "D3")
      (value "BAT54S")
      (footprint "eagle-import:SOT23")
      (libsource (lib "eagle-import") (part "DIODE_2CACA-SOT23"))
    )
    (comp (ref "D4")
      (value "BAT54S")
      (footprint "eagle-import:SOT23")
      (libsource (lib "eagle-import") (part "DIODE_2CACA-SOT23"))
    )
    (comp (ref "IC11")
      (value "MAX232ECWE")
      (footprint "eagle-import:SO16L")
      (fields (field (name "MF") "MAXIM") (field (name "MPN") "MAX232ECWE+"))
      (libsource (lib "eagle-import") (part "MAX232ECWE"))
    )
    (comp (ref "JP17")
      (value "PINHD-1X1")
      (footprint "eagle-import:1X01")
      (libsource (lib "eagle-import") (part "PINHD-1X1"))
    )
    (comp (ref "JP18")
      (value "PINHD-1X1")
      (footprint "eagle-import:1X01")
      (libsource (lib "eagle-import") (part "PINHD-1X1"))
    )
    (comp (ref "JP19")
      (value "PINHD-1X1")
      (footprint "eagle-import:1X01")
      (libsource (lib "eagle-import") (part "PINHD-1X1"))
    )
    (comp (ref "JP20")
      (value "RS232")
      (footprint "eagle-import:2X05")
      (libsource (lib "eagle-import") (part "PINHD-2X5"))
    )
    (comp (ref "JP21")
      (value "PINHD-1X1")
      (footprint "eagle-import:1X01")
      (libsource (lib "eagle-import") (part "PINHD-1X1"))
    )
    (comp (ref "JP22")
      (value "PINHD-1X1")
      (footprint "eagle-import:1X01")
      (libsource (lib "eagle-import") (part "PINHD-1X1"))
    )
    (comp (ref "JP23")
      (value "PINHD-1X1")
      (footprint "eagle-import:1X01")
      (libsource (lib "eagle-import") (part "PINHD-1X1"))
    )
    (comp (ref "JP24")
      (value "PINHD-1X1")
      (footprint "eagle-import:1X01")
      (libsource (lib "eagle-import") (part "PINHD-1X1"))
    )
    (comp (ref "JP25")
      (value "PINHD-1X1")
      (footprint "eagle-import:1X01")
      (libsource (lib "eagle-import") (part "PINHD-1X1"))
    )
    (comp (ref "JP26")
      (value "PINHD-1X1")
      (footprint "eagle-import:1X01")
      (libsource (lib "eagle-import") (part "PINHD-1X1"))
    )
    (comp (ref "LED3")
      (value "RED")
      (footprint "eagle-import:CHIPLED_0805")
      (libsource (lib "eagle-import") (part "LEDCHIPLED_0805"))
    )
    (comp (ref "LED4")
      (value "YELLOW")
      (footprint "eagle-import:CHIPLED_0805")
      (libsource (lib "eagle-import") (part "LEDCHIPLED_0805"))
    )
    (comp (ref "R13")
      (value "10k")
      (footprint "eagle-import:M0805")
      (libsource (lib "eagle-import") (part "R-EU_M0805"))
    )
    (comp (ref "R14")
      (value "10k")
      (footprint "eagle-import:M0805")
      (libsource (lib "eagle-import") (part "R-EU_M0805"))
    )
    (comp (ref "R15")
      (value "10k")
      (footprint "eagle-import:M0805")
      (libsource (lib "eagle-import") (part "R-EU_M0805"))
    )
    (comp (ref "R16")
      (value "10k")
      (footprint "eagle-import:M0805")
      (libsource (lib "eagle-import") (part "R-EU_M0805"))
    )
    (comp (ref "R17")
      (value "10k")
      (footprint "eagle-import:M0805")
      (libsource (lib "eagle-import") (part "R-EU_M0805"))
    )
    (comp (ref "R18")
      (value "10k")
      (footprint "eagle-import:M0805")
      (libsource (lib "eagle-import") (part "R-EU_M0805"))
    )
    (comp (ref "R19")
      (value "0")
      (footprint "eagle-import:M0805")
      (libsource (lib "eagle-import") (part "R-EU_M0805"))
    )
    (comp (ref "R20")
      (value "10k")
      (footprint "eagle-import:M0805")
      (libsource (lib "eagle-import") (part "R-EU_M0805"))
    )
    (comp (ref "R21")
      (value "10k")
      (footprint "eagle-import:M0805")
      (libsource (lib "eagle-import") (part "R-EU_M0805"))
    )
    (comp (ref "R22")
      (value "0")
      (footprint "eagle-import:M0805")
      (libsource (lib "eagle-import") (part "R-EU_M0805"))
    )
    (comp (ref "R23")
      (value "3k3")
      (footprint "eagle-import:M0805")
      (libsource (lib "eagle-import") (part "R-EU_M0805"))
    )
    (comp (ref "R24")
      (value "3k3")
      (footprint "eagle-import:M0805")
      (libsource (lib "eagle-import") (part "R-EU_M0805"))
    )
    (comp (ref "R25")
      (value "270")
      (footprint "eagle-import:M0805")
      (libsource (lib "eagle-import") (part "R-EU_M0805"))
    )
    (comp (ref "R26")
      (value "270")
      (footprint "eagle-import:M0805")
      (libsource (lib "eagle-import") (part "R-EU_M0805"))
    )
    (comp (ref "R27")
      (value "470")
      (footprint "eagle-import:M0805")
      (libsource (lib "eagle-import") (part "R-EU_M0805"))
    )
    (comp (ref "R28")
      (value "1K")
      (footprint "eagle-import:M0805")
      (libsource (lib "eagle-import") (part "R-EU_M0805"))
    )
    (comp (ref "R29")
      (value "1K8")
      (footprint "eagle-import:M0805")
      (libsource (lib "eagle-import") (part "R-EU_M0805"))
    )
    (comp (ref "R30")
      (value "470")
      (footprint "eagle-import:M0805")
      (libsource (lib "eagle-import") (part "R-EU_M0805"))
    )
    (comp (ref "R31")
      (value "1k")
      (footprint "eagle-import:M0805")
      (libsource (lib "eagle-import") (part "R-EU_M0805"))
    )
    (comp (ref "R32")
      (value "1k8")
      (footprint "eagle-import:M0805")
      (libsource (lib "eagle-import") (part "R-EU_M0805"))
    )
    (comp (ref "R33")
      (value "470")
      (footprint "eagle-import:M0805")
      (libsource (lib "eagle-import") (part "R-EU_M0805"))
    )
    (comp (ref "R34")
      (value "1k")
      (footprint "eagle-import:M0805")
      (libsource (lib "eagle-import") (part "R-EU_M0805"))
    )
    (comp (ref "R35")
      (value "1k8")
      (footprint "eagle-import:M0805")
      (libsource (lib "eagle-import") (part "R-EU_M0805"))
    )
    (comp (ref "R36")
      (value "47")
      (footprint "eagle-import:M0805")
      (libsource (lib "eagle-import") (part "R-EU_M0805"))
    )
    (comp (ref "R37")
      (value "47")
      (footprint "eagle-import:M0805")
      (libsource (lib "eagle-import") (part "R-EU_M0805"))
    )
    (comp (ref "R38")
      (value "120")
      (footprint "eagle-import:M0805")
      (libsource (lib "eagle-import") (part "R-EU_M0805"))
    )
    (comp (ref "R39")
      (value "120")
      (footprint "eagle-import:M0805")
      (libsource (lib "eagle-import") (part "R-EU_M0805"))
    )
    (comp (ref "R40")
      (value "120")
      (footprint "eagle-import:M0805")
      (libsource (lib "eagle-import") (part "R-EU_M0805"))
    )
    (comp (ref "R41")
      (value "120")
      (footprint "eagle-import:M0805")
      (libsource (lib "eagle-import") (part "R-EU_M0805"))
    )
    (comp (ref "R42")
      (value "2k")
      (footprint "eagle-import:M0805")
      (libsource (lib "eagle-import") (part "R-EU_M0805"))
    )
    (comp (ref "R43")
      (value "2k")
      (footprint "eagle-import:M0805")
      (libsource (lib "eagle-import") (part "R-EU_M0805"))
    )
    (comp (ref "R44")
      (value "2k")
      (footprint "eagle-import:M0805")
      (libsource (lib "eagle-import") (part "R-EU_M0805"))
    )
    (comp (ref "R45")
      (value "2k")
      (footprint "eagle-import:M0805")
      (libsource (lib "eagle-import") (part "R-EU_M0805"))
    )
  )
  (nets
    (net (code "1") (name "+5V") (class "Default")
      (node (ref "C28") (pin "1") (pinfunction "1_1") (pintype "passive"))
      (node (ref "C30") (pin "+") (pinfunction "+_+") (pintype "passive"))
      (node (ref "C33") (pin "1") (pinfunction "1_1") (pintype "passive"))
      (node (ref "C35") (pin "1") (pinfunction "1_1") (pintype "passive"))
      (node (ref "C56") (pin "2") (pinfunction "2_2") (pintype "passive"))
      (node (ref "C57") (pin "2") (pinfunction "2_2") (pintype "passive"))
      (node (ref "CON4") (pin "1-4") (pinfunction "4_1-4") (pintype "passive"))
      (node (ref "CON4") (pin "2-4") (pinfunction "4_2-4") (pintype "passive"))
      (node (ref "IC10") (pin "3") (pinfunction "IN_3") (pintype "power_in"))
      (node (ref "IC6") (pin "15") (pinfunction "VCC_15") (pintype "power_in"))
      (node (ref "IC6") (pin "35") (pinfunction "VCC_35") (pintype "power_in"))
      (node (ref "J1") (pin "A1") (pinfunction "A1_A1") (pintype "passive"))
      (node (ref "J1") (pin "B1") (pinfunction "B1_B1") (pintype "passive"))
      (node (ref "J1") (pin "C1") (pinfunction "C1_C1") (pintype "passive"))
      (node (ref "R1") (pin "2") (pinfunction "2_2") (pintype "passive"))
      (node (ref "R2") (pin "2") (pinfunction "2_2") (pintype "passive"))
      (node (ref "R3") (pin "2") (pinfunction "2_2") (pintype "passive"))
      (node (ref "R42") (pin "1") (pinfunction "1_1") (pintype "passive"))
      (node (ref "R43") (pin "1") (pinfunction "1_1") (pintype "passive"))
      (node (ref "R44") (pin "1") (pinfunction "1_1") (pintype "passive"))
      (node (ref "R45") (pin "1") (pinfunction "1_1") (pintype "passive"))
    )
    (net (code "2") (name "A0") (class "Default")
      (node (ref "IC4") (pin "9") (pinfunction "A8_9") (pintype "bidirectional"))
      (node (ref "IC7") (pin "150") (pinfunction "PR2A_150") (pintype "bidirectional"))
    )
    (net (code "3") (name "A1") (class "Default")
      (node (ref "IC4") (pin "6") (pinfunction "A5_6") (pintype "bidirectional"))
      (node (ref "IC7") (pin "146") (pinfunction "PR3B/RUM0_PLLC_FB_A_146") (pintype "bidirectional"))
    )
    (net (code "4") (name "A2") (class "Default")
      (node (ref "IC4") (pin "7") (pinfunction "A6_7") (pintype "bidirectional"))
      (node (ref "IC7") (pin "147") (pinfunction "PR3A/RUM0_PLLT_FB_A_147") (pintype "bidirectional"))
    )
    (net (code "5") (name "A3") (class "Default")
      (node (ref "IC4") (pin "8") (pinfunction "A7_8") (pintype "bidirectional"))
      (node (ref "IC7") (pin "148") (pinfunction "PR2B_148") (pintype "bidirectional"))
    )
    (net (code "6") (name "A4") (class "Default")
      (node (ref "IC4") (pin "5") (pinfunction "A4_5") (pintype "bidirectional"))
      (node (ref "IC7") (pin "145") (pinfunction "PR4A_145") (pintype "bidirectional"))
    )
    (net (code "7") (name "A5") (class "Default")
      (node (ref "IC4") (pin "3") (pinfunction "A2_3") (pintype "bidirectional"))
      (node (ref "IC7") (pin "142") (pinfunction "PR5A/VREF2_2_142") (pintype "bidirectional"))
    )
    (net (code "8") (name "A6") (class "Default")
      (node (ref "IC3") (pin "4") (pinfunction "A3_4") (pintype "bidirectional"))
      (node (ref "IC7") (pin "137") (pinfunction "PR8A/RUM0_PLLT_IN_A_137") (pintype "bidirectional"))
    )
    (net (code "9") (name "A7") (class "Default")
      (node (ref "IC4") (pin "2") (pinfunction "A1_2") (pintype "bidirectional"))
      (node (ref "IC7") (pin "141") (pinfunction "PR6B/VREF1_2_141") (pintype "bidirectional"))
    )
    (net (code "10") (name "A8") (class "Default")
      (node (ref "IC4") (pin "4") (pinfunction "A3_4") (pintype "bidirectional"))
      (node (ref "IC7") (pin "144") (pinfunction "PR4B_144") (pintype "bidirectional"))
    )
    (net (code "11") (name "A9") (class "Default")
      (node (ref "IC5") (pin "9") (pinfunction "A8_9") (pintype "bidirectional"))
      (node (ref "IC7") (pin "120") (pinfunction "PR21A_120") (pintype "bidirectional"))
    )
    (net (code "12") (name "A10") (class "Default")
      (node (ref "IC3") (pin "9") (pinfunction "A8_9") (pintype "bidirectional"))
      (node (ref "IC7") (pin "131") (pinfunction "PR12B/PCLKC2_0_131") (pintype "bidirectional"))
    )
    (net (code "13") (name "A11") (class "Default")
      (node (ref "IC3") (pin "7") (pinfunction "A6_7") (pintype "bidirectional"))
      (node (ref "IC7") (pin "133") (pinfunction "PR11B_133") (pintype "bidirectional"))
    )
    (net (code "14") (name "A12") (class "Default")
      (node (ref "IC5") (pin "6") (pinfunction "A5_6") (pintype "bidirectional"))
      (node (ref "IC7") (pin "124") (pinfunction "PR19B_124") (pintype "bidirectional"))
    )
    (net (code "15") (name "A13") (class "Default")
      (node (ref "IC5") (pin "8") (pinfunction "A7_8") (pintype "bidirectional"))
      (node (ref "IC7") (pin "122") (pinfunction "PR20B_122") (pintype "bidirectional"))
    )
    (net (code "16") (name "A14") (class "Default")
      (node (ref "IC5") (pin "2") (pinfunction "A1_2") (pintype "bidirectional"))
      (node (ref "IC7") (pin "129") (pinfunction "PR13A_129") (pintype "bidirectional"))
    )
    (net (code "17") (name "A15") (class "Default")
      (node (ref "IC5") (pin "7") (pinfunction "A6_7") (pintype "bidirectional"))
      (node (ref "IC7") (pin "123") (pinfunction "PR20A_123") (pintype "bidirectional"))
    )
    (net (code "18") (name "A16") (class "Default")
      (node (ref "IC5") (pin "3") (pinfunction "A2_3") (pintype "bidirectional"))
      (node (ref "IC7") (pin "126") (pinfunction "PR19A_126") (pintype "bidirectional"))
    )
    (net (code "19") (name "A17") (class "Default")
      (node (ref "IC3") (pin "8") (pinfunction "A7_8") (pintype "bidirectional"))
      (node (ref "IC7") (pin "132") (pinfunction "PR12A/PCLKT2_0_132") (pintype "bidirectional"))
    )
    (net (code "20") (name "A18") (class "Default")
      (node (ref "IC3") (pin "3") (pinfunction "A2_3") (pintype "bidirectional"))
      (node (ref "IC7") (pin "138") (pinfunction "PR7B_138") (pintype "bidirectional"))
    )
    (net (code "21") (name "A19") (class "Default")
      (node (ref "IC3") (pin "2") (pinfunction "A1_2") (pintype "bidirectional"))
      (node (ref "IC6") (pin "19") (pinfunction "2/17_19") (pintype "bidirectional"))
      (node (ref "JP3") (pin "1") (pinfunction "1_1") (pintype "passive"))
    )
    (net (code "22") (name "AUDIO_L") (class "Default")
      (node (ref "IC7") (pin "29") (pinfunction "PL16A_29") (pintype "bidirectional"))
      (node (ref "JP8") (pin "1") (pinfunction "1_1") (pintype "passive"))
      (node (ref "R24") (pin "1") (pinfunction "1_1") (pintype "passive"))
    )
    (net (code "23") (name "AUDIO_R") (class "Default")
      (node (ref "IC7") (pin "30") (pinfunction "PL16B_30") (pintype "bidirectional"))
      (node (ref "JP9") (pin "1") (pinfunction "1_1") (pintype "passive"))
      (node (ref "R23") (pin "1") (pinfunction "1_1") (pintype "passive"))
    )
    (net (code "24") (name "B_020_A0") (class "Default")
      (node (ref "IC3") (pin "15") (pinfunction "B4_15") (pintype "bidirectional"))
      (node (ref "J1") (pin "A15") (pinfunction "A15_A15") (pintype "passive"))
    )
    (net (code "25") (name "B_020_A1") (class "Default")
      (node (ref "IC3") (pin "14") (pinfunction "B5_14") (pintype "bidirectional"))
      (node (ref "J1") (pin "A16") (pinfunction "A16_A16") (pintype "passive"))
    )
    (net (code "26") (name "B_A0") (class "Default")
      (node (ref "IC4") (pin "11") (pinfunction "B8_11") (pintype "bidirectional"))
      (node (ref "J1") (pin "C5") (pinfunction "C5_C5") (pintype "passive"))
    )
    (net (code "27") (name "B_A1") (class "Default")
      (node (ref "IC4") (pin "14") (pinfunction "B5_14") (pintype "bidirectional"))
      (node (ref "J1") (pin "C7") (pinfunction "C7_C7") (pintype "passive"))
    )
    (net (code "28") (name "B_A2") (class "Default")
      (node (ref "IC4") (pin "13") (pinfunction "B6_13") (pintype "bidirectional"))
      (node (ref "J1") (pin "A6") (pinfunction "A6_A6") (pintype "passive"))
    )
    (net (code "29") (name "B_A3") (class "Default")
      (node (ref "IC4") (pin "12") (pinfunction "B7_12") (pintype "bidirectional"))
      (node (ref "J1") (pin "C6") (pinfunction "C6_C6") (pintype "passive"))
    )
    (net (code "30") (name "B_A4") (class "Default")
      (node (ref "IC4") (pin "15") (pinfunction "B4_15") (pintype "bidirectional"))
      (node (ref "J1") (pin "A7") (pinfunction "A7_A7") (pintype "passive"))
    )
    (net (code "31") (name "B_A5") (class "Default")
      (node (ref "IC4") (pin "17") (pinfunction "B2_17") (pintype "bidirectional"))
      (node (ref "J1") (pin "A8") (pinfunction "A8_A8") (pintype "passive"))
    )
    (net (code "32") (name "B_A6") (class "Default")
      (node (ref "IC3") (pin "16") (pinfunction "B3_16") (pintype "bidirectional"))
      (node (ref "J1") (pin "A9") (pinfunction "A9_A9") (pintype "passive"))
    )
    (net (code "33") (name "B_A7") (class "Default")
      (node (ref "IC4") (pin "18") (pinfunction "B1_18") (pintype "bidirectional"))
      (node (ref "J1") (pin "C9") (pinfunction "C9_C9") (pintype "passive"))
    )
    (net (code "34") (name "B_A8") (class "Default")
      (node (ref "IC4") (pin "16") (pinfunction "B3_16") (pintype "bidirectional"))
      (node (ref "J1") (pin "C8") (pinfunction "C8_C8") (pintype "passive"))
    )
    (net (code "35") (name "B_A9") (class "Default")
      (node (ref "IC5") (pin "11") (pinfunction "B8_11") (pintype "bidirectional"))
      (node (ref "J1") (pin "A30") (pinfunction "A30_A30") (pintype "passive"))
    )
    (net (code "36") (name "B_A10") (class "Default")
      (node (ref "IC3") (pin "11") (pinfunction "B8_11") (pintype "bidirectional"))
      (node (ref "J1") (pin "C18") (pinfunction "C18_C18") (pintype "passive"))
    )
    (net (code "37") (name "B_A11") (class "Default")
      (node (ref "IC3") (pin "13") (pinfunction "B6_13") (pintype "bidirectional"))
      (node (ref "J1") (pin "C17") (pinfunction "C17_C17") (pintype "passive"))
    )
    (net (code "38") (name "B_A12") (class "Default")
      (node (ref "IC5") (pin "14") (pinfunction "B5_14") (pintype "bidirectional"))
      (node (ref "J1") (pin "C27") (pinfunction "C27_C27") (pintype "passive"))
    )
    (net (code "39") (name "B_A13") (class "Default")
      (node (ref "IC5") (pin "12") (pinfunction "B7_12") (pintype "bidirectional"))
      (node (ref "J1") (pin "A29") (pinfunction "A29_A29") (pintype "passive"))
    )
    (net (code "40") (name "B_A14") (class "Default")
      (node (ref "IC5") (pin "18") (pinfunction "B1_18") (pintype "bidirectional"))
      (node (ref "J1") (pin "A18") (pinfunction "A18_A18") (pintype "passive"))
    )
    (net (code "41") (name "B_A15") (class "Default")
      (node (ref "IC5") (pin "13") (pinfunction "B6_13") (pintype "bidirectional"))
      (node (ref "J1") (pin "C28") (pinfunction "C28_C28") (pintype "passive"))
    )
    (net (code "42") (name "B_A16") (class "Default")
      (node (ref "IC5") (pin "17") (pinfunction "B2_17") (pintype "bidirectional"))
      (node (ref "J1") (pin "C19") (pinfunction "C19_C19") (pintype "passive"))
    )
    (net (code "43") (name "B_A17") (class "Default")
      (node (ref "IC3") (pin "12") (pinfunction "B7_12") (pintype "bidirectional"))
      (node (ref "J1") (pin "A17") (pinfunction "A17_A17") (pintype "passive"))
    )
    (net (code "44") (name "B_A18") (class "Default")
      (node (ref "IC3") (pin "17") (pinfunction "B2_17") (pintype "bidirectional"))
      (node (ref "J1") (pin "A12") (pinfunction "A12_A12") (pintype "passive"))
    )
    (net (code "45") (name "B_A19") (class "Default")
      (node (ref "IC3") (pin "18") (pinfunction "B1_18") (pintype "bidirectional"))
      (node (ref "J1") (pin "C12") (pinfunction "C12_C12") (pintype "passive"))
    )
    (net (code "46") (name "B_A20") (class "Default")
      (node (ref "IC6") (pin "29") (pinfunction "2/10_29") (pintype "bidirectional"))
      (node (ref "J1") (pin "B2") (pinfunction "B2_B2") (pintype "passive"))
    )
    (net (code "47") (name "B_A21") (class "Default")
      (node (ref "IC6") (pin "30") (pinfunction "2/9_30") (pintype "bidirectional"))
      (node (ref "J1") (pin "B3") (pinfunction "B3_B3") (pintype "passive"))
    )
    (net (code "48") (name "B_A22") (class "Default")
      (node (ref "IC6") (pin "31") (pinfunction "2/8_31") (pintype "bidirectional"))
      (node (ref "J1") (pin "B4") (pinfunction "B4_B4") (pintype "passive"))
    )
    (net (code "49") (name "B_A23") (class "Default")
      (node (ref "IC6") (pin "32") (pinfunction "2/7_32") (pintype "bidirectional"))
      (node (ref "J1") (pin "B5") (pinfunction "B5_B5") (pintype "passive"))
    )
    (net (code "50") (name "B_A24") (class "Default")
      (node (ref "IC6") (pin "33") (pinfunction "2/6_33") (pintype "bidirectional"))
      (node (ref "J1") (pin "C10") (pinfunction "C10_C10") (pintype "passive"))
    )
    (net (code "51") (name "B_A25") (class "Default")
      (node (ref "IC6") (pin "36") (pinfunction "2/3_36") (pintype "bidirectional"))
      (node (ref "J1") (pin "C11") (pinfunction "C11_C11") (pintype "passive"))
    )
    (net (code "52") (name "B_A26") (class "Default")
      (node (ref "IC6") (pin "39") (pinfunction "2/1_39") (pintype "bidirectional"))
      (node (ref "J1") (pin "A14") (pinfunction "A14_A14") (pintype "passive"))
    )
    (net (code "53") (name "B_A27") (class "Default")
      (node (ref "IC6") (pin "40") (pinfunction "1/1_40") (pintype "bidirectional"))
      (node (ref "J1") (pin "C15") (pinfunction "C15_C15") (pintype "passive"))
    )
    (net (code "54") (name "B_A28") (class "Default")
      (node (ref "IC6") (pin "41") (pinfunction "1/2_41") (pintype "bidirectional"))
      (node (ref "J1") (pin "C16") (pinfunction "C16_C16") (pintype "passive"))
    )
    (net (code "55") (name "B_A29") (class "Default")
      (node (ref "IC6") (pin "42") (pinfunction "1/4_42") (pintype "bidirectional"))
      (node (ref "J1") (pin "A19") (pinfunction "A19_A19") (pintype "passive"))
    )
    (net (code "56") (name "B_D0") (class "Default")
      (node (ref "IC1") (pin "17") (pinfunction "B2_17") (pintype "bidirectional"))
      (node (ref "J1") (pin "C2") (pinfunction "C2_C2") (pintype "passive"))
    )
    (net (code "57") (name "B_D1") (class "Default")
      (node (ref "IC2") (pin "11") (pinfunction "B8_11") (pintype "bidirectional"))
      (node (ref "J1") (pin "C14") (pinfunction "C14_C14") (pintype "passive"))
    )
    (net (code "58") (name "B_D2") (class "Default")
      (node (ref "IC1") (pin "13") (pinfunction "B6_13") (pintype "bidirectional"))
      (node (ref "J1") (pin "C4") (pinfunction "C4_C4") (pintype "passive"))
    )
    (net (code "59") (name "B_D3") (class "Default")
      (node (ref "IC1") (pin "14") (pinfunction "B5_14") (pintype "bidirectional"))
      (node (ref "J1") (pin "A4") (pinfunction "A4_A4") (pintype "passive"))
    )
    (net (code "60") (name "B_D4") (class "Default")
      (node (ref "IC1") (pin "12") (pinfunction "B7_12") (pintype "bidirectional"))
      (node (ref "J1") (pin "A5") (pinfunction "A5_A5") (pintype "passive"))
    )
    (net (code "61") (name "B_D5") (class "Default")
      (node (ref "IC1") (pin "18") (pinfunction "B1_18") (pintype "bidirectional"))
      (node (ref "J1") (pin "A2") (pinfunction "A2_A2") (pintype "passive"))
    )
    (net (code "62") (name "B_D6") (class "Default")
      (node (ref "IC1") (pin "16") (pinfunction "B3_16") (pintype "bidirectional"))
      (node (ref "J1") (pin "A3") (pinfunction "A3_A3") (pintype "passive"))
    )
    (net (code "63") (name "B_D7") (class "Default")
      (node (ref "IC1") (pin "15") (pinfunction "B4_15") (pintype "bidirectional"))
      (node (ref "J1") (pin "C3") (pinfunction "C3_C3") (pintype "passive"))
    )
    (net (code "64") (name "B_D8") (class "Default")
      (node (ref "IC1") (pin "11") (pinfunction "B8_11") (pintype "bidirectional"))
      (node (ref "J1") (pin "B6") (pinfunction "B6_B6") (pintype "passive"))
    )
    (net (code "65") (name "B_D9") (class "Default")
      (node (ref "IC2") (pin "18") (pinfunction "B1_18") (pintype "bidirectional"))
      (node (ref "J1") (pin "B7") (pinfunction "B7_B7") (pintype "passive"))
    )
    (net (code "66") (name "B_D10") (class "Default")
      (node (ref "IC2") (pin "17") (pinfunction "B2_17") (pintype "bidirectional"))
      (node (ref "J1") (pin "B8") (pinfunction "B8_B8") (pintype "passive"))
    )
    (net (code "67") (name "B_D11") (class "Default")
      (node (ref "IC2") (pin "16") (pinfunction "B3_16") (pintype "bidirectional"))
      (node (ref "J1") (pin "B9") (pinfunction "B9_B9") (pintype "passive"))
    )
    (net (code "68") (name "B_D12") (class "Default")
      (node (ref "IC2") (pin "15") (pinfunction "B4_15") (pintype "bidirectional"))
      (node (ref "J1") (pin "B10") (pinfunction "B10_B10") (pintype "passive"))
    )
    (net (code "69") (name "B_D13") (class "Default")
      (node (ref "IC2") (pin "14") (pinfunction "B5_14") (pintype "bidirectional"))
      (node (ref "J1") (pin "B11") (pinfunction "B11_B11") (pintype "passive"))
    )
    (net (code "70") (name "B_D14") (class "Default")
      (node (ref "IC2") (pin "13") (pinfunction "B6_13") (pintype "bidirectional"))
      (node (ref "J1") (pin "B12") (pinfunction "B12_B12") (pintype "passive"))
    )
    (net (code "71") (name "B_D15") (class "Default")
      (node (ref "IC2") (pin "12") (pinfunction "B7_12") (pintype "bidirectional"))
      (node (ref "J1") (pin "B13") (pinfunction "B13_B13") (pintype "passive"))
    )
    (net (code "72") (name "B_D16") (class "Default")
      (node (ref "J1") (pin "B22") (pinfunction "B22_B22") (pintype "passive"))
    )
    (net (code "73") (name "B_D17") (class "Default")
      (node (ref "J1") (pin "B23") (pinfunction "B23_B23") (pintype "passive"))
    )
    (net (code "74") (name "B_D18") (class "Default")
      (node (ref "J1") (pin "B24") (pinfunction "B24_B24") (pintype "passive"))
    )
    (net (code "75") (name "B_D19") (class "Default")
      (node (ref "J1") (pin "B25") (pinfunction "B25_B25") (pintype "passive"))
    )
    (net (code "76") (name "B_D20") (class "Default")
      (node (ref "J1") (pin "B26") (pinfunction "B26_B26") (pintype "passive"))
    )
    (net (code "77") (name "B_D21") (class "Default")
      (node (ref "J1") (pin "B27") (pinfunction "B27_B27") (pintype "passive"))
    )
    (net (code "78") (name "B_D22") (class "Default")
      (node (ref "J1") (pin "B30") (pinfunction "B30_B30") (pintype "passive"))
    )
    (net (code "79") (name "B_D23") (class "Default")
      (node (ref "J1") (pin "B31") (pinfunction "B31_B31") (pintype "passive"))
    )
    (net (code "80") (name "B_D24") (class "Default")
      (node (ref "J1") (pin "B14") (pinfunction "B14_B14") (pintype "passive"))
    )
    (net (code "81") (name "B_D25") (class "Default")
      (node (ref "J1") (pin "B15") (pinfunction "B15_B15") (pintype "passive"))
    )
    (net (code "82") (name "B_D26") (class "Default")
      (node (ref "J1") (pin "B16") (pinfunction "B16_B16") (pintype "passive"))
    )
    (net (code "83") (name "B_D27") (class "Default")
      (node (ref "J1") (pin "A22") (pinfunction "A22_A22") (pintype "passive"))
    )
    (net (code "84") (name "B_D28") (class "Default")
      (node (ref "J1") (pin "A23") (pinfunction "A23_A23") (pintype "passive"))
    )
    (net (code "85") (name "B_D29") (class "Default")
      (node (ref "J1") (pin "A24") (pinfunction "A24_A24") (pintype "passive"))
    )
    (net (code "86") (name "B_D30") (class "Default")
      (node (ref "J1") (pin "A25") (pinfunction "A25_A25") (pintype "passive"))
    )
    (net (code "87") (name "B_D31") (class "Default")
      (node (ref "J1") (pin "A26") (pinfunction "A26_A26") (pintype "passive"))
    )
    (net (code "88") (name "B_IOR") (class "Default")
      (node (ref "IC6") (pin "3") (pinfunction "1/8_3") (pintype "bidirectional"))
      (node (ref "J1") (pin "A27") (pinfunction "A27_A27") (pintype "passive"))
    )
    (net (code "89") (name "B_MEMR") (class "Default")
      (node (ref "IC6") (pin "7") (pinfunction "1/11_7") (pintype "bidirectional"))
      (node (ref "J1") (pin "C30") (pinfunction "C30_C30") (pintype "passive"))
    )
    (net (code "90") (name "B_RD") (class "Default")
      (node (ref "IC5") (pin "15") (pinfunction "B4_15") (pintype "bidirectional"))
      (node (ref "J1") (pin "C24") (pinfunction "C24_C24") (pintype "passive"))
    )
    (net (code "91") (name "B_RESET") (class "Default")
      (node (ref "IC6") (pin "8") (pinfunction "1/12_8") (pintype "bidirectional"))
      (node (ref "J1") (pin "C31") (pinfunction "C31_C31") (pintype "passive"))
    )
    (net (code "92") (name "B_WR") (class "Default")
      (node (ref "IC5") (pin "16") (pinfunction "B3_16") (pintype "bidirectional"))
      (node (ref "J1") (pin "C22") (pinfunction "C22_C22") (pintype "passive"))
    )
    (net (code "93") (name "CLK") (class "Default")
      (node (ref "IC7") (pin "31") (pinfunction "PL17A/PCLKT6_0_31") (pintype "bidirectional"))
      (node (ref "R9") (pin "1") (pinfunction "1_1") (pintype "passive"))
    )
    (net (code "94") (name "D0") (class "Default")
      (node (ref "IC1") (pin "3") (pinfunction "A2_3") (pintype "bidirectional"))
      (node (ref "IC7") (pin "178") (pinfunction "PT18B/D6_178") (pintype "bidirectional"))
    )
    (net (code "95") (name "D1") (class "Default")
      (node (ref "IC2") (pin "9") (pinfunction "A8_9") (pintype "bidirectional"))
      (node (ref "IC7") (pin "159") (pinfunction "PT28A/VREF1_1_159") (pintype "bidirectional"))
    )
    (net (code "96") (name "D2") (class "Default")
      (node (ref "IC1") (pin "7") (pinfunction "A6_7") (pintype "bidirectional"))
      (node (ref "IC7") (pin "173") (pinfunction "PT21B_173") (pintype "bidirectional"))
    )
    (net (code "97") (name "D3") (class "Default")
      (node (ref "IC1") (pin "6") (pinfunction "A5_6") (pintype "bidirectional"))
      (node (ref "IC7") (pin "174") (pinfunction "PT20A/D4_174") (pintype "bidirectional"))
    )
    (net (code "98") (name "D4") (class "Default")
      (node (ref "IC1") (pin "8") (pinfunction "A7_8") (pintype "bidirectional"))
      (node (ref "IC7") (pin "171") (pinfunction "PT22A/DQS_171") (pintype "bidirectional"))
    )
    (net (code "99") (name "D5") (class "Default")
      (node (ref "IC1") (pin "2") (pinfunction "A1_2") (pintype "bidirectional"))
      (node (ref "IC7") (pin "179") (pinfunction "PT18A_179") (pintype "bidirectional"))
    )
    (net (code "100") (name "D6") (class "Default")
      (node (ref "IC1") (pin "4") (pinfunction "A3_4") (pintype "bidirectional"))
      (node (ref "IC7") (pin "176") (pinfunction "PT19A/D5_176") (pintype "bidirectional"))
    )
    (net (code "101") (name "D7") (class "Default")
      (node (ref "IC1") (pin "5") (pinfunction "A4_5") (pintype "bidirectional"))
      (node (ref "IC7") (pin "175") (pinfunction "PT19B_175") (pintype "bidirectional"))
    )
    (net (code "102") (name "D8") (class "Default")
      (node (ref "IC1") (pin "9") (pinfunction "A8_9") (pintype "bidirectional"))
      (node (ref "IC7") (pin "170") (pinfunction "PT22B_170") (pintype "bidirectional"))
    )
    (net (code "103") (name "D9") (class "Default")
      (node (ref "IC2") (pin "2") (pinfunction "A1_2") (pintype "bidirectional"))
      (node (ref "IC7") (pin "168") (pinfunction "PT23B/D3_168") (pintype "bidirectional"))
    )
    (net (code "104") (name "D10") (class "Default")
      (node (ref "IC2") (pin "3") (pinfunction "A2_3") (pintype "bidirectional"))
      (node (ref "IC7") (pin "166") (pinfunction "PT24A/D2_166") (pintype "bidirectional"))
    )
    (net (code "105") (name "D11") (class "Default")
      (node (ref "IC2") (pin "4") (pinfunction "A3_4") (pintype "bidirectional"))
      (node (ref "IC7") (pin "165") (pinfunction "PT25A/VREF2_1_165") (pintype "bidirectional"))
    )
    (net (code "106") (name "D12") (class "Default")
      (node (ref "IC2") (pin "5") (pinfunction "A4_5") (pintype "bidirectional"))
      (node (ref "IC7") (pin "164") (pinfunction "PT25B/D1_164") (pintype "bidirectional"))
    )
    (net (code "107") (name "D13") (class "Default")
      (node (ref "IC2") (pin "6") (pinfunction "A5_6") (pintype "bidirectional"))
      (node (ref "IC7") (pin "162") (pinfunction "PT26A/D0_162") (pintype "bidirectional"))
    )
    (net (code "108") (name "D14") (class "Default")
      (node (ref "IC2") (pin "7") (pinfunction "A6_7") (pintype "bidirectional"))
      (node (ref "IC7") (pin "161") (pinfunction "PT27A_161") (pintype "bidirectional"))
    )
    (net (code "109") (name "D15") (class "Default")
      (node (ref "IC2") (pin "8") (pinfunction "A7_8") (pintype "bidirectional"))
      (node (ref "IC7") (pin "160") (pinfunction "PT27B_160") (pintype "bidirectional"))
    )
    (net (code "110") (name "DIR") (class "Default")
      (node (ref "IC1") (pin "1") (pinfunction "DIR_1") (pintype "input"))
      (node (ref "IC2") (pin "1") (pinfunction "DIR_1") (pintype "input"))
      (node (ref "IC7") (pin "169") (pinfunction "PT23A_169") (pintype "bidirectional"))
    )
    (net (code "111") (name "DMACK") (class "Default")
      (node (ref "CON1") (pin "44") (pinfunction "/DMACK_44") (pintype "input"))
      (node (ref "JP17") (pin "1") (pinfunction "1_1") (pintype "passive"))
      (node (ref "R19") (pin "1") (pinfunction "1_1") (pintype "passive"))
    )
    (net (code "112") (name "DONE") (class "Default")
      (node (ref "IC7") (pin "2") (pinfunction "DONE_2") (pintype "bidirectional"))
      (node (ref "R5") (pin "1") (pinfunction "1_1") (pintype "passive"))
      (node (ref "R6") (pin "2") (pinfunction "2_2") (pintype "passive"))
    )
    (net (code "113") (name "F_020_A0") (class "Default")
      (node (ref "IC3") (pin "5") (pinfunction "A4_5") (pintype "bidirectional"))
      (node (ref "IC7") (pin "136") (pinfunction "PR8B/RUM0_PLLC_IN_A_136") (pintype "bidirectional"))
    )
    (net (code "114") (name "F_020_A1") (class "Default")
      (node (ref "IC3") (pin "6") (pinfunction "A5_6") (pintype "bidirectional"))
      (node (ref "IC7") (pin "134") (pinfunction "PR11A_134") (pintype "bidirectional"))
    )
    (net (code "115") (name "F_INT") (class "Default")
      (node (ref "IC6") (pin "22") (pinfunction "2/14_22") (pintype "bidirectional"))
      (node (ref "IC7") (pin "116") (pinfunction "PR23B/VREF1_3_116") (pintype "bidirectional"))
    )
    (net (code "116") (name "F_IORQ") (class "Default")
      (node (ref "IC6") (pin "16") (pinfunction "1/16_16") (pintype "bidirectional"))
      (node (ref "IC7") (pin "111") (pinfunction "PR25B_111") (pintype "bidirectional"))
    )
    (net (code "117") (name "F_IRQ0") (class "Default")
      (node (ref "IC6") (pin "21") (pinfunction "2/15_21") (pintype "bidirectional"))
      (node (ref "IC7") (pin "114") (pinfunction "PR24A/DQS_114") (pintype "bidirectional"))
    )
    (net (code "118") (name "F_IRQ1") (class "Default")
      (node (ref "IC6") (pin "20") (pinfunction "2/16_20") (pintype "bidirectional"))
      (node (ref "IC7") (pin "113") (pinfunction "PR24B_113") (pintype "bidirectional"))
    )
    (net (code "119") (name "F_LDS_SIZ1") (class "Default")
      (node (ref "IC6") (pin "14") (pinfunction "1/15_14") (pintype "bidirectional"))
      (node (ref "IC7") (pin "110") (pinfunction "PR26A_110") (pintype "bidirectional"))
    )
    (net (code "120") (name "F_MEMRQ") (class "Default")
      (node (ref "IC6") (pin "13") (pinfunction "1/14_13") (pintype "bidirectional"))
      (node (ref "IC7") (pin "108") (pinfunction "PR26B_108") (pintype "bidirectional"))
    )
    (net (code "121") (name "F_NMI") (class "Default")
      (node (ref "IC6") (pin "23") (pinfunction "2/13_23") (pintype "bidirectional"))
      (node (ref "IC7") (pin "117") (pinfunction "PR22A/VREF2_3_117") (pintype "bidirectional"))
    )
    (net (code "122") (name "F_RD") (class "Default")
      (node (ref "IC5") (pin "5") (pinfunction "A4_5") (pintype "bidirectional"))
      (node (ref "IC7") (pin "104") (pinfunction "PB30A/DQS_104") (pintype "bidirectional"))
    )
    (net (code "123") (name "F_RESET") (class "Default")
      (node (ref "IC6") (pin "28") (pinfunction "2/11_28") (pintype "bidirectional"))
      (node (ref "IC7") (pin "11") (pinfunction "PL4A_11") (pintype "bidirectional"))
      (node (ref "JP18") (pin "1") (pinfunction "1_1") (pintype "passive"))
      (node (ref "R22") (pin "2") (pinfunction "2_2") (pintype "passive"))
    )
    (net (code "124") (name "F_TCK") (class "Default")
      (node (ref "IC7") (pin "157") (pinfunction "TCK_157") (pintype "input"))
      (node (ref "JP16") (pin "1") (pinfunction "1_1") (pintype "passive"))
      (node (ref "R11") (pin "2") (pinfunction "2_2") (pintype "passive"))
    )
    (net (code "125") (name "F_TDI") (class "Default")
      (node (ref "IC7") (pin "155") (pinfunction "TDI_155") (pintype "input"))
      (node (ref "JP16") (pin "5") (pinfunction "5_5") (pintype "passive"))
    )
    (net (code "126") (name "F_TDO") (class "Default")
      (node (ref "IC7") (pin "153") (pinfunction "TDO_153") (pintype "output"))
      (node (ref "JP16") (pin "7") (pinfunction "7_7") (pintype "passive"))
    )
    (net (code "127") (name "F_TMS") (class "Default")
      (node (ref "IC7") (pin "156") (pinfunction "TMS_156") (pintype "input"))
      (node (ref "JP16") (pin "3") (pinfunction "3_3") (pintype "passive"))
    )
    (net (code "128") (name "F_UDS_SIZ0") (class "Default")
      (node (ref "IC6") (pin "18") (pinfunction "1/17_18") (pintype "bidirectional"))
      (node (ref "IC7") (pin "112") (pinfunction "PR25A_112") (pintype "bidirectional"))
    )
    (net (code "129") (name "F_WAIT") (class "Default")
      (node (ref "IC6") (pin "27") (pinfunction "2/12_27") (pintype "bidirectional"))
      (node (ref "IC7") (pin "119") (pinfunction "PR21B_119") (pintype "bidirectional"))
    )
    (net (code "130") (name "F_WR") (class "Default")
      (node (ref "IC5") (pin "4") (pinfunction "A3_4") (pintype "bidirectional"))
      (node (ref "IC7") (pin "105") (pinfunction "PB30B_105") (pintype "bidirectional"))
    )
    (net (code "131") (name "GND") (class "Default")
      (node (ref "C1") (pin "2") (pinfunction "2_2") (pintype "passive"))
      (node (ref "C10") (pin "2") (pinfunction "2_2") (pintype "passive"))
      (node (ref "C11") (pin "-") (pinfunction "-_-") (pintype "passive"))
      (node (ref "C12") (pin "-") (pinfunction "-_-") (pintype "passive"))
      (node (ref "C13") (pin "2") (pinfunction "2_2") (pintype "passive"))
      (node (ref "C14") (pin "2") (pinfunction "2_2") (pintype "passive"))
      (node (ref "C15") (pin "-") (pinfunction "-_-") (pintype "passive"))
      (node (ref "C16") (pin "2") (pinfunction "2_2") (pintype "passive"))
      (node (ref "C17") (pin "2") (pinfunction "2_2") (pintype "passive"))
      (node (ref "C18") (pin "-") (pinfunction "-_-") (pintype "passive"))
      (node (ref "C19") (pin "-") (pinfunction "-_-") (pintype "passive"))
      (node (ref "C2") (pin "2") (pinfunction "2_2") (pintype "passive"))
      (node (ref "C20") (pin "-") (pinfunction "-_-") (pintype "passive"))
      (node (ref "C21") (pin "2") (pinfunction "2_2") (pintype "passive"))
      (node (ref "C22") (pin "-") (pinfunction "-_-") (pintype "passive"))
      (node (ref "C23") (pin "2") (pinfunction "2_2") (pintype "passive"))
      (node (ref "C24") (pin "-") (pinfunction "-_-") (pintype "passive"))
      (node (ref "C25") (pin "2") (pinfunction "2_2") (pintype "passive"))
      (node (ref "C26") (pin "2") (pinfunction "2_2") (pintype "passive"))
      (node (ref "C27") (pin "2") (pinfunction "2_2") (pintype "passive"))
      (node (ref "C28") (pin "2") (pinfunction "2_2") (pintype "passive"))
      (node (ref "C29") (pin "2") (pinfunction "2_2") (pintype "passive"))
      (node (ref "C3") (pin "2") (pinfunction "2_2") (pintype "passive"))
      (node (ref "C30") (pin "-") (pinfunction "-_-") (pintype "passive"))
      (node (ref "C31") (pin "2") (pinfunction "2_2") (pintype "passive"))
      (node (ref "C32") (pin "2") (pinfunction "2_2") (pintype "passive"))
      (node (ref "C33") (pin "2") (pinfunction "2_2") (pintype "passive"))
      (node (ref "C34") (pin "2") (pinfunction "2_2") (pintype "passive"))
      (node (ref "C35") (pin "2") (pinfunction "2_2") (pintype "passive"))
      (node (ref "C36") (pin "2") (pinfunction "2_2") (pintype "passive"))
      (node (ref "C37") (pin "2") (pinfunction "2_2") (pintype "passive"))
      (node (ref "C38") (pin "2") (pinfunction "2_2") (pintype "passive"))
      (node (ref "C39") (pin "2") (pinfunction "2_2") (pintype "passive"))
      (node (ref "C4") (pin "-") (pinfunction "-_-") (pintype "passive"))
      (node (ref "C40") (pin "2") (pinfunction "2_2") (pintype "passive"))
      (node (ref "C41") (pin "2") (pinfunction "2_2") (pintype "passive"))
      (node (ref "C42") (pin "2") (pinfunction "2_2") (pintype "passive"))
      (node (ref "C43") (pin "2") (pinfunction "2_2") (pintype "passive"))
      (node (ref "C44") (pin "2") (pinfunction "2_2") (pintype "passive"))
      (node (ref "C45") (pin "2") (pinfunction "2_2") (pintype "passive"))
      (node (ref "C46") (pin "2") (pinfunction "2_2") (pintype "passive"))
      (node (ref "C47") (pin "2") (pinfunction "2_2") (pintype "passive"))
      (node (ref "C48") (pin "2") (pinfunction "2_2") (pintype "passive"))
      (node (ref "C5") (pin "2") (pinfunction "2_2") (pintype "passive"))
      (node (ref "C52") (pin "2") (pinfunction "2_2") (pintype "passive"))
      (node (ref "C53") (pin "2") (pinfunction "2_2") (pintype "passive"))
      (node (ref "C54") (pin "2") (pinfunction "2_2") (pintype "passive"))
      (node (ref "C55") (pin "2") (pinfunction "2_2") (pintype "passive"))
      (node (ref "C56") (pin "1") (pinfunction "1_1") (pintype "passive"))
      (node (ref "C57") (pin "1") (pinfunction "1_1") (pintype "passive"))
      (node (ref "C6") (pin "2") (pinfunction "2_2") (pintype "passive"))
      (node (ref "C7") (pin "-") (pinfunction "-_-") (pintype "passive"))
      (node (ref "C8") (pin "2") (pinfunction "2_2") (pintype "passive"))
      (node (ref "C9") (pin "-") (pinfunction "-_-") (pintype "passive"))
      (node (ref "CON1") (pin "1") (pinfunction "GND1_1") (pintype "power_in"))
      (node (ref "CON1") (pin "10") (pinfunction "A09_10") (pintype "input"))
      (node (ref "CON1") (pin "11") (pinfunction "A08_11") (pintype "input"))
      (node (ref "CON1") (pin "12") (pinfunction "A07_12") (pintype "input"))
      (node (ref "CON1") (pin "14") (pinfunction "A06_14") (pintype "input"))
      (node (ref "CON1") (pin "15") (pinfunction "A05_15") (pintype "input"))
      (node (ref "CON1") (pin "16") (pinfunction "A04_16") (pintype "input"))
      (node (ref "CON1") (pin "17") (pinfunction "A03_17") (pintype "input"))
      (node (ref "CON1") (pin "50") (pinfunction "GND2_50") (pintype "power_in"))
      (node (ref "CON1") (pin "8") (pinfunction "A10_8") (pintype "input"))
      (node (ref "CON2") (pin "1") (pinfunction "1_1") (pintype "passive"))
      (node (ref "CON3") (pin "3") (pinfunction "3_3") (pintype "input"))
      (node (ref "CON3") (pin "6") (pinfunction "6_6") (pintype "input"))
      (node (ref "CON3") (pin "S1") (pinfunction "SHIELD_S1") (pintype "passive"))
      (node (ref "CON4") (pin "1-3") (pinfunction "3_1-3") (pintype "passive"))
      (node (ref "CON4") (pin "10") (pinfunction "10_10") (pintype "passive"))
      (node (ref "CON4") (pin "11") (pinfunction "11_11") (pintype "passive"))
      (node (ref "CON4") (pin "12") (pinfunction "12_12") (pintype "passive"))
      (node (ref "CON4") (pin "2-3") (pinfunction "3_2-3") (pintype "passive"))
      (node (ref "CON4") (pin "6") (pinfunction "6_6") (pintype "passive"))
      (node (ref "CON4") (pin "7") (pinfunction "7_7") (pintype "passive"))
      (node (ref "CON4") (pin "8") (pinfunction "8_8") (pintype "passive"))
      (node (ref "CON4") (pin "S1") (pinfunction "SHIELD_S1") (pintype "passive"))
      (node (ref "CON4") (pin "S2") (pinfunction "SHIELD_S2") (pintype "passive"))
      (node (ref "CON4") (pin "S3") (pinfunction "SHIELD_S3") (pintype "passive"))
      (node (ref "CON4") (pin "S4") (pinfunction "SHIELD_S4") (pintype "passive"))
      (node (ref "CON4") (pin "S5") (pinfunction "SHIELD_S5") (pintype "passive"))
      (node (ref "CON4") (pin "S6") (pinfunction "SHIELD_S6") (pintype "passive"))
      (node (ref "D1") (pin "1") (pinfunction "A_1") (pintype "passive"))
      (node (ref "D2") (pin "1") (pinfunction "A_1") (pintype "passive"))
      (node (ref "D3") (pin "1") (pinfunction "A_1") (pintype "passive"))
      (node (ref "D4") (pin "1") (pinfunction "A_1") (pintype "passive"))
      (node (ref "IC10") (pin "1") (pinfunction "ADJ_1") (pintype "power_in"))
      (node (ref "IC11") (pin "15") (pinfunction "GND_15") (pintype "power_in"))
      (node (ref "IC3") (pin "19") (pinfunction "G_19") (pintype "input"))
      (node (ref "IC4") (pin "19") (pinfunction "G_19") (pintype "input"))
      (node (ref "IC5") (pin "19") (pinfunction "G_19") (pintype "input"))
      (node (ref "IC6") (pin "17") (pinfunction "GND_17") (pintype "power_in"))
      (node (ref "IC6") (pin "25") (pinfunction "GND_25") (pintype "power_in"))
      (node (ref "IC6") (pin "4") (pinfunction "GND_4") (pintype "power_in"))
      (node (ref "IC7") (pin "106") (pinfunction "GND_106") (pintype "power_in"))
      (node (ref "IC7") (pin "109") (pinfunction "GNDIO3_109") (pintype "power_in"))
      (node (ref "IC7") (pin "118") (pinfunction "GNDIO3_118") (pintype "power_in"))
      (node (ref "IC7") (pin "121") (pinfunction "GND_121") (pintype "power_in"))
      (node (ref "IC7") (pin "127") (pinfunction "GNDP1_127") (pintype "power_in"))
      (node (ref "IC7") (pin "130") (pinfunction "GND_130") (pintype "power_in"))
      (node (ref "IC7") (pin "135") (pinfunction "GNDIO2_135") (pintype "power_in"))
      (node (ref "IC7") (pin "143") (pinfunction "GNDIO2_143") (pintype "power_in"))
      (node (ref "IC7") (pin "16") (pinfunction "GNDIO7_16") (pintype "power_in"))
      (node (ref "IC7") (pin "163") (pinfunction "GNDIO1_163") (pintype "power_in"))
      (node (ref "IC7") (pin "172") (pinfunction "GNDIO1_172") (pintype "power_in"))
      (node (ref "IC7") (pin "181") (pinfunction "GND_181") (pintype "power_in"))
      (node (ref "IC7") (pin "184") (pinfunction "GNDIO0_184") (pintype "power_in"))
      (node (ref "IC7") (pin "194") (pinfunction "GNDIO0_194") (pintype "power_in"))
      (node (ref "IC7") (pin "207") (pinfunction "GND_207") (pintype "power_in"))
      (node (ref "IC7") (pin "26") (pinfunction "GNDP0_26") (pintype "power_in"))
      (node (ref "IC7") (pin "38") (pinfunction "GNDIO6_38") (pintype "power_in"))
      (node (ref "IC7") (pin "4") (pinfunction "CCLK_4") (pintype "bidirectional"))
      (node (ref "IC7") (pin "47") (pinfunction "GNDIO6_47") (pintype "power_in"))
      (node (ref "IC7") (pin "49") (pinfunction "GND_49") (pintype "power_in"))
      (node (ref "IC7") (pin "5") (pinfunction "GND_5") (pintype "power_in"))
      (node (ref "IC7") (pin "59") (pinfunction "GNDIO5_59") (pintype "power_in"))
      (node (ref "IC7") (pin "69") (pinfunction "GNDIO5_69") (pintype "power_in"))
      (node (ref "IC7") (pin "7") (pinfunction "GNDIO7_7") (pintype "power_in"))
      (node (ref "IC7") (pin "79") (pinfunction "GND_79") (pintype "power_in"))
      (node (ref "IC7") (pin "82") (pinfunction "GNDIO4_82") (pintype "power_in"))
      (node (ref "IC7") (pin "92") (pinfunction "GNDIO4_92") (pintype "power_in"))
      (node (ref "IC8") (pin "12") (pinfunction "GND_12") (pintype "power_in"))
      (node (ref "IC8") (pin "34") (pinfunction "GND_34") (pintype "power_in"))
      (node (ref "IC9") (pin "12") (pinfunction "GND_12") (pintype "power_in"))
      (node (ref "IC9") (pin "34") (pinfunction "GND_34") (pintype "power_in"))
      (node (ref "J1") (pin "A32") (pinfunction "A32_A32") (pintype "passive"))
      (node (ref "J1") (pin "B32") (pinfunction "B32_B32") (pintype "passive"))
      (node (ref "J1") (pin "C32") (pinfunction "C32_C32") (pintype "passive"))
      (node (ref "JP1") (pin "1") (pinfunction "1_1") (pintype "passive"))
      (node (ref "JP15") (pin "2") (pinfunction "2_2") (pintype "passive"))
      (node (ref "JP16") (pin "2") (pinfunction "2_2") (pintype "passive"))
      (node (ref "JP16") (pin "4") (pinfunction "4_4") (pintype "passive"))
      (node (ref "JP16") (pin "8") (pinfunction "8_8") (pintype "passive"))
      (node (ref "JP20") (pin "5") (pinfunction "5_5") (pintype "passive"))
      (node (ref "LED2") (pin "C") (pinfunction "C_C") (pintype "passive"))
      (node (ref "OSZI1") (pin "4") (pinfunction "GND_4") (pintype "power_in"))
      (node (ref "R11") (pin "1") (pinfunction "1_1") (pintype "passive"))
      (node (ref "R20") (pin "2") (pinfunction "2_2") (pintype "passive"))
      (node (ref "R21") (pin "2") (pinfunction "2_2") (pintype "passive"))
      (node (ref "R7") (pin "1") (pinfunction "1_1") (pintype "passive"))
      (node (ref "R8") (pin "1") (pinfunction "1_1") (pintype "passive"))
      (node (ref "T1") (pin "2") (pinfunction "S_2") (pintype "passive"))
    )
    (net (code "132") (name "IDE_CS0") (class "Default")
      (node (ref "CON1") (pin "7") (pinfunction "/CS0_7") (pintype "input"))
      (node (ref "IC7") (pin "203") (pinfunction "PT7B_203") (pintype "bidirectional"))
    )
    (net (code "133") (name "IDE_CS1") (class "Default")
      (node (ref "CON1") (pin "32") (pinfunction "/CS1_32") (pintype "input"))
      (node (ref "IC7") (pin "204") (pinfunction "PT7A_204") (pintype "bidirectional"))
    )
    (net (code "134") (name "IDE_D0") (class "Default")
      (node (ref "CON1") (pin "21") (pinfunction "D00_21") (pintype "bidirectional"))
      (node (ref "IC7") (pin "196") (pinfunction "PT10B_196") (pintype "bidirectional"))
    )
    (net (code "135") (name "IDE_D1") (class "Default")
      (node (ref "CON1") (pin "22") (pinfunction "D01_22") (pintype "bidirectional"))
      (node (ref "IC7") (pin "197") (pinfunction "PT10A/VREF1_0_197") (pintype "bidirectional"))
    )
    (net (code "136") (name "IDE_D2") (class "Default")
      (node (ref "CON1") (pin "23") (pinfunction "D02_23") (pintype "bidirectional"))
      (node (ref "IC7") (pin "200") (pinfunction "PT9A/DI_200") (pintype "bidirectional"))
    )
    (net (code "137") (name "IDE_D3") (class "Default")
      (node (ref "CON1") (pin "2") (pinfunction "D03_2") (pintype "bidirectional"))
      (node (ref "IC7") (pin "183") (pinfunction "PT16B/BUSY_183") (pintype "bidirectional"))
    )
    (net (code "138") (name "IDE_D4") (class "Default")
      (node (ref "CON1") (pin "3") (pinfunction "D04_3") (pintype "bidirectional"))
      (node (ref "IC7") (pin "186") (pinfunction "PT15B/PCLKC0_0_186") (pintype "bidirectional"))
    )
    (net (code "139") (name "IDE_D5") (class "Default")
      (node (ref "CON1") (pin "4") (pinfunction "D05_4") (pintype "bidirectional"))
      (node (ref "IC7") (pin "188") (pinfunction "PT14B_188") (pintype "bidirectional"))
    )
    (net (code "140") (name "IDE_D6") (class "Default")
      (node (ref "CON1") (pin "5") (pinfunction "D06_5") (pintype "bidirectional"))
      (node (ref "IC7") (pin "191") (pinfunction "PT13B_191") (pintype "bidirectional"))
    )
    (net (code "141") (name "IDE_D7") (class "Default")
      (node (ref "CON1") (pin "6") (pinfunction "D07_6") (pintype "bidirectional"))
      (node (ref "IC7") (pin "193") (pinfunction "PT11B_193") (pintype "bidirectional"))
    )
    (net (code "142") (name "IDE_D8") (class "Default")
      (node (ref "CON1") (pin "47") (pinfunction "D08_47") (pintype "bidirectional"))
      (node (ref "IC7") (pin "198") (pinfunction "PT9B_198") (pintype "bidirectional"))
    )
    (net (code "143") (name "IDE_D9") (class "Default")
      (node (ref "CON1") (pin "48") (pinfunction "D09_48") (pintype "bidirectional"))
      (node (ref "IC7") (pin "201") (pinfunction "PT8B_201") (pintype "bidirectional"))
    )
    (net (code "144") (name "IDE_D10") (class "Default")
      (node (ref "CON1") (pin "49") (pinfunction "D10_49") (pintype "bidirectional"))
      (node (ref "IC7") (pin "202") (pinfunction "PT8A/CSN_202") (pintype "bidirectional"))
    )
    (net (code "145") (name "IDE_D11") (class "Default")
      (node (ref "CON1") (pin "27") (pinfunction "D11_27") (pintype "bidirectional"))
      (node (ref "IC7") (pin "185") (pinfunction "PT16A/CS1N_185") (pintype "bidirectional"))
    )
    (net (code "146") (name "IDE_D12") (class "Default")
      (node (ref "CON1") (pin "28") (pinfunction "D12_28") (pintype "bidirectional"))
      (node (ref "IC7") (pin "187") (pinfunction "PT15A/PCLKT0_0_187") (pintype "bidirectional"))
    )
    (net (code "147") (name "IDE_D13") (class "Default")
      (node (ref "CON1") (pin "29") (pinfunction "D13_29") (pintype "bidirectional"))
      (node (ref "IC7") (pin "190") (pinfunction "PT14A/DQS_190") (pintype "bidirectional"))
    )
    (net (code "148") (name "IDE_D14") (class "Default")
      (node (ref "CON1") (pin "30") (pinfunction "D14_30") (pintype "bidirectional"))
      (node (ref "IC7") (pin "192") (pinfunction "PT12A/DOUT_192") (pintype "bidirectional"))
    )
    (net (code "149") (name "IDE_D15") (class "Default")
      (node (ref "CON1") (pin "31") (pinfunction "D15_31") (pintype "bidirectional"))
      (node (ref "IC7") (pin "195") (pinfunction "PT11A/WRITEN_195") (pintype "bidirectional"))
    )
    (net (code "150") (name "IDE_DASP") (class "Default")
      (node (ref "CON1") (pin "45") (pinfunction "/DASP_45") (pintype "bidirectional"))
      (node (ref "R18") (pin "1") (pinfunction "1_1") (pintype "passive"))
      (node (ref "R25") (pin "1") (pinfunction "1_1") (pintype "passive"))
    )
    (net (code "151") (name "IDE_IA0") (class "Default")
      (node (ref "CON1") (pin "20") (pinfunction "A00_20") (pintype "input"))
      (node (ref "IC7") (pin "10") (pinfunction "PL3B/LUM0_PLLC_FB_A_10") (pintype "bidirectional"))
    )
    (net (code "152") (name "IDE_IA1") (class "Default")
      (node (ref "CON1") (pin "19") (pinfunction "A01_19") (pintype "input"))
      (node (ref "IC7") (pin "9") (pinfunction "PL3A/LUM0_PLLT_FB_A_9") (pintype "bidirectional"))
    )
    (net (code "153") (name "IDE_IA2") (class "Default")
      (node (ref "CON1") (pin "18") (pinfunction "A02_18") (pintype "input"))
      (node (ref "IC7") (pin "8") (pinfunction "PL2B_8") (pintype "bidirectional"))
    )
    (net (code "154") (name "IDE_INT") (class "Default")
      (node (ref "CON1") (pin "37") (pinfunction "INTRQ_37") (pintype "output"))
      (node (ref "IC7") (pin "6") (pinfunction "PL2A_6") (pintype "bidirectional"))
    )
    (net (code "155") (name "IDE_IOCS16") (class "Default")
      (node (ref "CON1") (pin "24") (pinfunction "/IOCS16_24") (pintype "output"))
      (node (ref "R14") (pin "1") (pinfunction "1_1") (pintype "passive"))
    )
    (net (code "156") (name "IDE_IORDY") (class "Default")
      (node (ref "CON1") (pin "42") (pinfunction "IORDY_42") (pintype "output"))
      (node (ref "R13") (pin "1") (pinfunction "1_1") (pintype "passive"))
    )
    (net (code "157") (name "IDE_PDIAG") (class "Default")
      (node (ref "CON1") (pin "46") (pinfunction "/PDIAG_46") (pintype "bidirectional"))
      (node (ref "R17") (pin "1") (pinfunction "1_1") (pintype "passive"))
    )
    (net (code "158") (name "IDE_PRESENT") (class "Default")
      (node (ref "CON1") (pin "25") (pinfunction "/CD2_25") (pintype "output"))
      (node (ref "R26") (pin "1") (pinfunction "1_1") (pintype "passive"))
    )
    (net (code "159") (name "IDE_RD") (class "Default")
      (node (ref "CON1") (pin "34") (pinfunction "/IORD_34") (pintype "input"))
      (node (ref "IC7") (pin "205") (pinfunction "PT6B/VREF2_0_205") (pintype "bidirectional"))
    )
    (net (code "160") (name "IDE_VS1") (class "Default")
      (node (ref "CON1") (pin "33") (pinfunction "/VS1_33") (pintype "output"))
      (node (ref "R15") (pin "1") (pinfunction "1_1") (pintype "passive"))
    )
    (net (code "161") (name "IDE_VS2") (class "Default")
      (node (ref "CON1") (pin "40") (pinfunction "/VS2_40") (pintype "output"))
      (node (ref "R16") (pin "1") (pinfunction "1_1") (pintype "passive"))
    )
    (net (code "162") (name "IDE_WR") (class "Default")
      (node (ref "CON1") (pin "35") (pinfunction "/IOWR_35") (pintype "input"))
      (node (ref "IC7") (pin "206") (pinfunction "PT5B_206") (pintype "bidirectional"))
    )
    (net (code "163") (name "IRQ0") (class "Default")
      (node (ref "IC6") (pin "1") (pinfunction "1/7_1") (pintype "bidirectional"))
      (node (ref "J1") (pin "B21") (pinfunction "B21_B21") (pintype "passive"))
    )
    (net (code "164") (name "IRQ1") (class "Default")
      (node (ref "IC6") (pin "43") (pinfunction "1/3_43") (pintype "bidirectional"))
      (node (ref "J1") (pin "B20") (pinfunction "B20_B20") (pintype "passive"))
    )
    (net (code "165") (name "IRQ2") (class "Default")
      (node (ref "J1") (pin "B19") (pinfunction "B19_B19") (pintype "passive"))
    )
    (net (code "166") (name "IRQ3") (class "Default")
      (node (ref "J1") (pin "B18") (pinfunction "B18_B18") (pintype "passive"))
    )
    (net (code "167") (name "IRQ4") (class "Default")
      (node (ref "J1") (pin "B17") (pinfunction "B17_B17") (pintype "passive"))
    )
    (net (code "168") (name "KEY_CLK") (class "Default")
      (node (ref "D2") (pin "3") (pinfunction "AC_3") (pintype "passive"))
      (node (ref "IC7") (pin "45") (pinfunction "PL25B_45") (pintype "bidirectional"))
      (node (ref "R39") (pin "1") (pinfunction "1_1") (pintype "passive"))
    )
    (net (code "169") (name "KEY_DAT") (class "Default")
      (node (ref "D1") (pin "3") (pinfunction "AC_3") (pintype "passive"))
      (node (ref "IC7") (pin "44") (pinfunction "PL25A_44") (pintype "bidirectional"))
      (node (ref "R38") (pin "1") (pinfunction "1_1") (pintype "passive"))
    )
    (net (code "170") (name "MOUSE_CLK") (class "Default")
      (node (ref "D4") (pin "3") (pinfunction "AC_3") (pintype "passive"))
      (node (ref "IC7") (pin "46") (pinfunction "PL26A_46") (pintype "bidirectional"))
      (node (ref "R41") (pin "1") (pinfunction "1_1") (pintype "passive"))
    )
    (net (code "171") (name "MOUSE_DAT") (class "Default")
      (node (ref "D3") (pin "3") (pinfunction "AC_3") (pintype "passive"))
      (node (ref "IC7") (pin "48") (pinfunction "PL26B_48") (pintype "bidirectional"))
      (node (ref "R40") (pin "1") (pinfunction "1_1") (pintype "passive"))
    )
    (net (code "172") (name "Net-(C54-Pad1)") (class "Default")
      (node (ref "C54") (pin "1") (pinfunction "1_1") (pintype "passive"))
      (node (ref "CON2") (pin "5") (pinfunction "5_5") (pintype "passive"))
      (node (ref "R23") (pin "2") (pinfunction "2_2") (pintype "passive"))
    )
    (net (code "173") (name "Net-(C55-Pad1)") (class "Default")
      (node (ref "C55") (pin "1") (pinfunction "1_1") (pintype "passive"))
      (node (ref "CON2") (pin "2") (pinfunction "2_2") (pintype "passive"))
      (node (ref "R24") (pin "2") (pinfunction "2_2") (pintype "passive"))
    )
    (net (code "174") (name "Net-(CON1A-{slash}ATASEL)") (class "Default")
      (node (ref "CON1") (pin "9") (pinfunction "/ATASEL_9") (pintype "input"))
      (node (ref "R20") (pin "1") (pinfunction "1_1") (pintype "passive"))
    )
    (net (code "175") (name "Net-(CON1A-{slash}CD1)") (class "Default")
      (node (ref "CON1") (pin "26") (pinfunction "/CD1_26") (pintype "output"))
      (node (ref "JP21") (pin "1") (pinfunction "1_1") (pintype "passive"))
    )
    (net (code "176") (name "Net-(CON1A-{slash}CSEL)") (class "Default")
      (node (ref "CON1") (pin "39") (pinfunction "/CSEL_39") (pintype "input"))
      (node (ref "R21") (pin "1") (pinfunction "1_1") (pintype "passive"))
    )
    (net (code "177") (name "Net-(CON1A-{slash}DMARQ)") (class "Default")
      (node (ref "CON1") (pin "43") (pinfunction "/DMARQ_43") (pintype "output"))
      (node (ref "JP22") (pin "1") (pinfunction "1_1") (pintype "passive"))
    )
    (net (code "178") (name "Net-(CON1A-{slash}RESET)") (class "Default")
      (node (ref "CON1") (pin "41") (pinfunction "/RESET_41") (pintype "input"))
      (node (ref "JP19") (pin "1") (pinfunction "1_1") (pintype "passive"))
      (node (ref "R22") (pin "1") (pinfunction "1_1") (pintype "passive"))
    )
    (net (code "179") (name "Net-(CON3-COM_TERM)") (class "Default")
      (node (ref "CON3") (pin "CD") (pinfunction "COM_TERM_CD") (pintype "passive"))
      (node (ref "JP25") (pin "1") (pinfunction "1_1") (pintype "passive"))
    )
    (net (code "180") (name "Net-(CON3-Pad8)") (class "Default")
      (node (ref "CON3") (pin "8") (pinfunction "8_8") (pintype "input"))
      (node (ref "JP23") (pin "1") (pinfunction "1_1") (pintype "passive"))
    )
    (net (code "181") (name "Net-(CON3-Pad9)") (class "Default")
      (node (ref "CON3") (pin "9") (pinfunction "9_9") (pintype "input"))
      (node (ref "JP24") (pin "1") (pinfunction "1_1") (pintype "passive"))
    )
    (net (code "182") (name "Net-(CON3-WRITE_PROT)") (class "Default")
      (node (ref "CON3") (pin "WP") (pinfunction "WRITE_PROT_WP") (pintype "passive"))
      (node (ref "JP26") (pin "1") (pinfunction "1_1") (pintype "passive"))
    )
    (net (code "183") (name "Net-(CON4-Pad1)") (class "Default")
      (node (ref "CON4") (pin "1") (pinfunction "1_1") (pintype "passive"))
      (node (ref "R27") (pin "2") (pinfunction "2_2") (pintype "passive"))
      (node (ref "R28") (pin "2") (pinfunction "2_2") (pintype "passive"))
      (node (ref "R29") (pin "2") (pinfunction "2_2") (pintype "passive"))
    )
    (net (code "184") (name "Net-(CON4-Pad2)") (class "Default")
      (node (ref "CON4") (pin "2") (pinfunction "2_2") (pintype "passive"))
      (node (ref "R30") (pin "2") (pinfunction "2_2") (pintype "passive"))
      (node (ref "R31") (pin "2") (pinfunction "2_2") (pintype "passive"))
      (node (ref "R32") (pin "2") (pinfunction "2_2") (pintype "passive"))
    )
    (net (code "185") (name "Net-(CON4-Pad3)") (class "Default")
      (node (ref "CON4") (pin "3") (pinfunction "3_3") (pintype "passive"))
      (node (ref "R33") (pin "2") (pinfunction "2_2") (pintype "passive"))
      (node (ref "R34") (pin "2") (pinfunction "2_2") (pintype "passive"))
      (node (ref "R35") (pin "2") (pinfunction "2_2") (pintype "passive"))
    )
    (net (code "186") (name "Net-(CON4-Pad13)") (class "Default")
      (node (ref "CON4") (pin "13") (pinfunction "13_13") (pintype "passive"))
      (node (ref "R37") (pin "1") (pinfunction "1_1") (pintype "passive"))
    )
    (net (code "187") (name "Net-(CON4-Pad14)") (class "Default")
      (node (ref "CON4") (pin "14") (pinfunction "14_14") (pintype "passive"))
      (node (ref "R36") (pin "1") (pinfunction "1_1") (pintype "passive"))
    )
    (net (code "188") (name "Net-(CON4G-1)") (class "Default")
      (node (ref "CON4") (pin "1-1") (pinfunction "1_1-1") (pintype "passive"))
      (node (ref "R38") (pin "2") (pinfunction "2_2") (pintype "passive"))
      (node (ref "R42") (pin "2") (pinfunction "2_2") (pintype "passive"))
    )
    (net (code "189") (name "Net-(CON4G-5)") (class "Default")
      (node (ref "CON4") (pin "1-5") (pinfunction "5_1-5") (pintype "passive"))
      (node (ref "R39") (pin "2") (pinfunction "2_2") (pintype "passive"))
      (node (ref "R44") (pin "2") (pinfunction "2_2") (pintype "passive"))
    )
    (net (code "190") (name "Net-(CON4H-1)") (class "Default")
      (node (ref "CON4") (pin "2-1") (pinfunction "1_2-1") (pintype "passive"))
      (node (ref "R40") (pin "2") (pinfunction "2_2") (pintype "passive"))
      (node (ref "R43") (pin "2") (pinfunction "2_2") (pintype "passive"))
    )
    (net (code "191") (name "Net-(CON4H-5)") (class "Default")
      (node (ref "CON4") (pin "2-5") (pinfunction "5_2-5") (pintype "passive"))
      (node (ref "R41") (pin "2") (pinfunction "2_2") (pintype "passive"))
      (node (ref "R45") (pin "2") (pinfunction "2_2") (pintype "passive"))
    )
    (net (code "192") (name "Net-(IC1A-G)") (class "Default")
      (node (ref "IC1") (pin "19") (pinfunction "G_19") (pintype "input"))
      (node (ref "IC2") (pin "19") (pinfunction "G_19") (pintype "input"))
      (node (ref "JP4") (pin "1") (pinfunction "1_1") (pintype "passive"))
      (node (ref "R7") (pin "2") (pinfunction "2_2") (pintype "passive"))
    )
    (net (code "193") (name "Net-(IC3A-DIR)") (class "Default")
      (node (ref "IC3") (pin "1") (pinfunction "DIR_1") (pintype "input"))
      (node (ref "IC4") (pin "1") (pinfunction "DIR_1") (pintype "input"))
      (node (ref "IC5") (pin "1") (pinfunction "DIR_1") (pintype "input"))
      (node (ref "JP5") (pin "1") (pinfunction "1_1") (pintype "passive"))
      (node (ref "R8") (pin "2") (pinfunction "2_2") (pintype "passive"))
    )
    (net (code "194") (name "Net-(IC6-1{slash}13)") (class "Default")
      (node (ref "IC6") (pin "12") (pinfunction "1/13_12") (pintype "bidirectional"))
      (node (ref "JP2") (pin "1") (pinfunction "1_1") (pintype "passive"))
    )
    (net (code "195") (name "Net-(IC6-2{slash}2)") (class "Default")
      (node (ref "IC6") (pin "38") (pinfunction "2/2_38") (pintype "bidirectional"))
      (node (ref "JP6") (pin "1") (pinfunction "1_1") (pintype "passive"))
    )
    (net (code "196") (name "Net-(IC6-2{slash}5)") (class "Default")
      (node (ref "IC6") (pin "34") (pinfunction "2/5_34") (pintype "bidirectional"))
      (node (ref "JP7") (pin "1") (pinfunction "1_1") (pintype "passive"))
    )
    (net (code "197") (name "Net-(IC7B-PT17B{slash}D7)") (class "Default")
      (node (ref "IC7") (pin "180") (pinfunction "PT17B/D7_180") (pintype "bidirectional"))
      (node (ref "JP11") (pin "1") (pinfunction "1_1") (pintype "passive"))
    )
    (net (code "198") (name "Net-(IC7C-PR7A{slash}DQS)") (class "Default")
      (node (ref "IC7") (pin "139") (pinfunction "PR7A/DQS_139") (pintype "bidirectional"))
      (node (ref "JP10") (pin "1") (pinfunction "1_1") (pintype "passive"))
    )
    (net (code "199") (name "Net-(IC7J-INITN)") (class "Default")
      (node (ref "IC7") (pin "52") (pinfunction "INITN_52") (pintype "bidirectional"))
      (node (ref "JP12") (pin "1") (pinfunction "1_1") (pintype "passive"))
    )
    (net (code "200") (name "Net-(IC7J-PROGRAMN)") (class "Default")
      (node (ref "IC7") (pin "3") (pinfunction "PROGRAMN_3") (pintype "input"))
      (node (ref "JP13") (pin "1") (pinfunction "1_1") (pintype "passive"))
    )
    (net (code "201") (name "Net-(IC7J-SLEEPN)") (class "Default")
      (node (ref "IC7") (pin "51") (pinfunction "SLEEPN_51") (pintype "input"))
      (node (ref "JP14") (pin "1") (pinfunction "1_1") (pintype "passive"))
      (node (ref "R10") (pin "2") (pinfunction "2_2") (pintype "passive"))
    )
    (net (code "202") (name "Net-(IC11A-C1+)") (class "Default")
      (node (ref "C50") (pin "2") (pinfunction "2_2") (pintype "passive"))
      (node (ref "IC11") (pin "1") (pinfunction "C1+_1") (pintype "bidirectional"))
    )
    (net (code "203") (name "Net-(IC11A-C1-)") (class "Default")
      (node (ref "C50") (pin "1") (pinfunction "1_1") (pintype "passive"))
      (node (ref "IC11") (pin "3") (pinfunction "C1-_3") (pintype "bidirectional"))
    )
    (net (code "204") (name "Net-(IC11A-C2+)") (class "Default")
      (node (ref "C49") (pin "2") (pinfunction "2_2") (pintype "passive"))
      (node (ref "IC11") (pin "4") (pinfunction "C2+_4") (pintype "bidirectional"))
    )
    (net (code "205") (name "Net-(IC11A-C2-)") (class "Default")
      (node (ref "C49") (pin "1") (pinfunction "1_1") (pintype "passive"))
      (node (ref "IC11") (pin "5") (pinfunction "C2-_5") (pintype "bidirectional"))
    )
    (net (code "206") (name "Net-(IC11A-R1IN)") (class "Default")
      (node (ref "IC11") (pin "13") (pinfunction "R1IN_13") (pintype "input"))
      (node (ref "JP20") (pin "8") (pinfunction "8_8") (pintype "passive"))
    )
    (net (code "207") (name "Net-(IC11A-R2IN)") (class "Default")
      (node (ref "IC11") (pin "8") (pinfunction "R2IN_8") (pintype "input"))
      (node (ref "JP20") (pin "2") (pinfunction "2_2") (pintype "passive"))
    )
    (net (code "208") (name "Net-(IC11A-T1OUT)") (class "Default")
      (node (ref "IC11") (pin "14") (pinfunction "T1OUT_14") (pintype "output"))
      (node (ref "JP20") (pin "7") (pinfunction "7_7") (pintype "passive"))
    )
    (net (code "209") (name "Net-(IC11A-T2OUT)") (class "Default")
      (node (ref "IC11") (pin "7") (pinfunction "T2OUT_7") (pintype "output"))
      (node (ref "JP20") (pin "3") (pinfunction "3_3") (pintype "passive"))
    )
    (net (code "210") (name "Net-(IC11A-V+)") (class "Default")
      (node (ref "C51") (pin "2") (pinfunction "2_2") (pintype "passive"))
      (node (ref "IC11") (pin "2") (pinfunction "V+_2") (pintype "bidirectional"))
    )
    (net (code "211") (name "Net-(IC11A-V-)") (class "Default")
      (node (ref "C52") (pin "1") (pinfunction "1_1") (pintype "passive"))
      (node (ref "IC11") (pin "6") (pinfunction "V-_6") (pintype "bidirectional"))
    )
    (net (code "212") (name "Net-(IC12A-A)") (class "Default")
      (node (ref "IC12") (pin "1") (pinfunction "A_1") (pintype "input"))
      (node (ref "JP27") (pin "1") (pinfunction "1_1") (pintype "passive"))
    )
    (net (code "213") (name "Net-(IC12A-B)") (class "Default")
      (node (ref "IC12") (pin "2") (pinfunction "B_2") (pintype "input"))
      (node (ref "JP28") (pin "1") (pinfunction "1_1") (pintype "passive"))
    )
    (net (code "214") (name "Net-(IC12A-C)") (class "Default")
      (node (ref "IC12") (pin "14") (pinfunction "C_14") (pintype "input"))
      (node (ref "JP29") (pin "1") (pinfunction "1_1") (pintype "passive"))
    )
    (net (code "215") (name "Net-(IC12A-CLR)") (class "Default")
      (node (ref "IC12") (pin "3") (pinfunction "CLR_3") (pintype "input"))
      (node (ref "JP31") (pin "1") (pinfunction "1_1") (pintype "passive"))
    )
    (net (code "216") (name "Net-(IC12A-Q)") (class "Default")
      (node (ref "IC12") (pin "13") (pinfunction "Q_13") (pintype "output"))
      (node (ref "JP63") (pin "1") (pinfunction "1_1") (pintype "passive"))
    )
    (net (code "217") (name "Net-(IC12A-R{slash}C)") (class "Default")
      (node (ref "IC12") (pin "15") (pinfunction "R/C_15") (pintype "input"))
      (node (ref "JP30") (pin "1") (pinfunction "1_1") (pintype "passive"))
    )
    (net (code "218") (name "Net-(IC12A-~{Q})") (class "Default")
      (node (ref "IC12") (pin "4") (pinfunction "~{Q}_4") (pintype "output"))
      (node (ref "JP64") (pin "1") (pinfunction "1_1") (pintype "passive"))
    )
    (net (code "219") (name "Net-(IC12B-A)") (class "Default")
      (node (ref "IC12") (pin "9") (pinfunction "A_9") (pintype "input"))
      (node (ref "JP32") (pin "1") (pinfunction "1_1") (pintype "passive"))
    )
    (net (code "220") (name "Net-(IC12B-B)") (class "Default")
      (node (ref "IC12") (pin "10") (pinfunction "B_10") (pintype "input"))
      (node (ref "JP33") (pin "1") (pinfunction "1_1") (pintype "passive"))
    )
    (net (code "221") (name "Net-(IC12B-C)") (class "Default")
      (node (ref "IC12") (pin "6") (pinfunction "C_6") (pintype "input"))
      (node (ref "JP34") (pin "1") (pinfunction "1_1") (pintype "passive"))
    )
    (net (code "222") (name "Net-(IC12B-CLR)") (class "Default")
      (node (ref "IC12") (pin "11") (pinfunction "CLR_11") (pintype "input"))
      (node (ref "JP36") (pin "1") (pinfunction "1_1") (pintype "passive"))
    )
    (net (code "223") (name "Net-(IC12B-Q)") (class "Default")
      (node (ref "IC12") (pin "5") (pinfunction "Q_5") (pintype "output"))
      (node (ref "JP65") (pin "1") (pinfunction "1_1") (pintype "passive"))
    )
    (net (code "224") (name "Net-(IC12B-R{slash}C)") (class "Default")
      (node (ref "IC12") (pin "7") (pinfunction "R/C_7") (pintype "input"))
      (node (ref "JP35") (pin "1") (pinfunction "1_1") (pintype "passive"))
    )
    (net (code "225") (name "Net-(IC12B-~{Q})") (class "Default")
      (node (ref "IC12") (pin "12") (pinfunction "~{Q}_12") (pintype "output"))
      (node (ref "JP66") (pin "1") (pinfunction "1_1") (pintype "passive"))
    )
    (net (code "226") (name "Net-(IC12C-GND)") (class "Default")
      (node (ref "IC12") (pin "8") (pinfunction "GND_8") (pintype "power_in"))
      (node (ref "JP68") (pin "1") (pinfunction "1_1") (pintype "passive"))
    )
    (net (code "227") (name "Net-(IC12C-VCC)") (class "Default")
      (node (ref "IC12") (pin "16") (pinfunction "VCC_16") (pintype "power_in"))
      (node (ref "JP67") (pin "1") (pinfunction "1_1") (pintype "passive"))
    )
    (net (code "228") (name "Net-(LED1-PadA)") (class "Default")
      (node (ref "LED1") (pin "A") (pinfunction "A_A") (pintype "passive"))
      (node (ref "R4") (pin "1") (pinfunction "1_1") (pintype "passive"))
    )
    (net (code "229") (name "Net-(LED2-PadA)") (class "Default")
      (node (ref "LED2") (pin "A") (pinfunction "A_A") (pintype "passive"))
      (node (ref "R12") (pin "1") (pinfunction "1_1") (pintype "passive"))
    )
    (net (code "230") (name "Net-(LED3-PadC)") (class "Default")
      (node (ref "LED3") (pin "C") (pinfunction "C_C") (pintype "passive"))
      (node (ref "R25") (pin "2") (pinfunction "2_2") (pintype "passive"))
    )
    (net (code "231") (name "Net-(LED4-PadC)") (class "Default")
      (node (ref "LED4") (pin "C") (pinfunction "C_C") (pintype "passive"))
      (node (ref "R26") (pin "2") (pinfunction "2_2") (pintype "passive"))
    )
    (net (code "232") (name "Net-(OSZI1-OUT)") (class "Default")
      (node (ref "OSZI1") (pin "5") (pinfunction "OUT_5") (pintype "output"))
      (node (ref "R9") (pin "2") (pinfunction "2_2") (pintype "passive"))
    )
    (net (code "233") (name "Net-(T1-D)") (class "Default")
      (node (ref "LED1") (pin "C") (pinfunction "C_C") (pintype "passive"))
      (node (ref "T1") (pin "3") (pinfunction "D_3") (pintype "passive"))
    )
    (net (code "234") (name "Net-(T1-G)") (class "Default")
      (node (ref "R5") (pin "2") (pinfunction "2_2") (pintype "passive"))
      (node (ref "T1") (pin "1") (pinfunction "G_1") (pintype "passive"))
    )
    (net (code "235") (name "RAM0_CE") (class "Default")
      (node (ref "IC7") (pin "76") (pinfunction "PB15B_76") (pintype "bidirectional"))
      (node (ref "IC8") (pin "6") (pinfunction "~{CE}_6") (pintype "input"))
    )
    (net (code "236") (name "RAM1_CE") (class "Default")
      (node (ref "IC7") (pin "75") (pinfunction "PB15A_75") (pintype "bidirectional"))
      (node (ref "IC9") (pin "6") (pinfunction "~{CE}_6") (pintype "input"))
    )
    (net (code "237") (name "RAM_A0") (class "Default")
      (node (ref "IC7") (pin "86") (pinfunction "PB19A_86") (pintype "bidirectional"))
      (node (ref "IC8") (pin "23") (pinfunction "A10_23") (pintype "input"))
      (node (ref "IC9") (pin "27") (pinfunction "A14_27") (pintype "input"))
    )
    (net (code "238") (name "RAM_A1") (class "Default")
      (node (ref "IC7") (pin "88") (pinfunction "PB19B_88") (pintype "bidirectional"))
      (node (ref "IC8") (pin "24") (pinfunction "A11_24") (pintype "input"))
      (node (ref "IC9") (pin "26") (pinfunction "A13_26") (pintype "input"))
    )
    (net (code "239") (name "RAM_A2") (class "Default")
      (node (ref "IC7") (pin "89") (pinfunction "PB20A_89") (pintype "bidirectional"))
      (node (ref "IC8") (pin "25") (pinfunction "A12_25") (pintype "input"))
      (node (ref "IC9") (pin "25") (pinfunction "A12_25") (pintype "input"))
    )
    (net (code "240") (name "RAM_A3") (class "Default")
      (node (ref "IC7") (pin "90") (pinfunction "PB21B_90") (pintype "bidirectional"))
      (node (ref "IC8") (pin "26") (pinfunction "A13_26") (pintype "input"))
      (node (ref "IC9") (pin "24") (pinfunction "A11_24") (pintype "input"))
    )
    (net (code "241") (name "RAM_A4") (class "Default")
      (node (ref "IC7") (pin "91") (pinfunction "PB22A/DQS_91") (pintype "bidirectional"))
      (node (ref "IC8") (pin "27") (pinfunction "A14_27") (pintype "input"))
      (node (ref "IC9") (pin "23") (pinfunction "A10_23") (pintype "input"))
    )
    (net (code "242") (name "RAM_A5") (class "Default")
      (node (ref "IC7") (pin "81") (pinfunction "PB17A_81") (pintype "bidirectional"))
      (node (ref "IC8") (pin "44") (pinfunction "A17_44") (pintype "input"))
      (node (ref "IC9") (pin "42") (pinfunction "A15_42") (pintype "input"))
    )
    (net (code "243") (name "RAM_A6") (class "Default")
      (node (ref "IC7") (pin "78") (pinfunction "PB16B_78") (pintype "bidirectional"))
      (node (ref "IC8") (pin "43") (pinfunction "A16_43") (pintype "input"))
      (node (ref "IC9") (pin "43") (pinfunction "A16_43") (pintype "input"))
    )
    (net (code "244") (name "RAM_A7") (class "Default")
      (node (ref "IC7") (pin "77") (pinfunction "PB16A_77") (pintype "bidirectional"))
      (node (ref "IC8") (pin "42") (pinfunction "A15_42") (pintype "input"))
      (node (ref "IC9") (pin "44") (pinfunction "A17_44") (pintype "input"))
    )
    (net (code "245") (name "RAM_A8") (class "Default")
      (node (ref "IC7") (pin "103") (pinfunction "PB27A/VREF2_4_103") (pintype "bidirectional"))
      (node (ref "IC8") (pin "22") (pinfunction "A9_22") (pintype "input"))
      (node (ref "IC9") (pin "22") (pinfunction "A9_22") (pintype "input"))
    )
    (net (code "246") (name "RAM_A9") (class "Default")
      (node (ref "IC7") (pin "93") (pinfunction "PB22B/VREF1_4_93") (pintype "bidirectional"))
      (node (ref "IC8") (pin "1") (pinfunction "A0_1") (pintype "input"))
      (node (ref "IC9") (pin "1") (pinfunction "A0_1") (pintype "input"))
    )
    (net (code "247") (name "RAM_A10") (class "Default")
      (node (ref "IC7") (pin "94") (pinfunction "PB23A_94") (pintype "bidirectional"))
      (node (ref "IC8") (pin "2") (pinfunction "A1_2") (pintype "input"))
      (node (ref "IC9") (pin "2") (pinfunction "A1_2") (pintype "input"))
    )
    (net (code "248") (name "RAM_A11") (class "Default")
      (node (ref "IC7") (pin "95") (pinfunction "PB23B_95") (pintype "bidirectional"))
      (node (ref "IC8") (pin "3") (pinfunction "A2_3") (pintype "input"))
      (node (ref "IC9") (pin "3") (pinfunction "A2_3") (pintype "input"))
    )
    (net (code "249") (name "RAM_A12") (class "Default")
      (node (ref "IC7") (pin "96") (pinfunction "PB24A_96") (pintype "bidirectional"))
      (node (ref "IC8") (pin "4") (pinfunction "A3_4") (pintype "input"))
      (node (ref "IC9") (pin "4") (pinfunction "A3_4") (pintype "input"))
    )
    (net (code "250") (name "RAM_A13") (class "Default")
      (node (ref "IC7") (pin "98") (pinfunction "PB24B_98") (pintype "bidirectional"))
      (node (ref "IC8") (pin "5") (pinfunction "A4_5") (pintype "input"))
      (node (ref "IC9") (pin "5") (pinfunction "A4_5") (pintype "input"))
    )
    (net (code "251") (name "RAM_A14") (class "Default")
      (node (ref "IC7") (pin "99") (pinfunction "PB25A_99") (pintype "bidirectional"))
      (node (ref "IC8") (pin "18") (pinfunction "A5_18") (pintype "input"))
      (node (ref "IC9") (pin "18") (pinfunction "A5_18") (pintype "input"))
    )
    (net (code "252") (name "RAM_A15") (class "Default")
      (node (ref "IC7") (pin "100") (pinfunction "PB25B_100") (pintype "bidirectional"))
      (node (ref "IC8") (pin "19") (pinfunction "A6_19") (pintype "input"))
      (node (ref "IC9") (pin "19") (pinfunction "A6_19") (pintype "input"))
    )
    (net (code "253") (name "RAM_A16") (class "Default")
      (node (ref "IC7") (pin "101") (pinfunction "PB26A_101") (pintype "bidirectional"))
      (node (ref "IC8") (pin "20") (pinfunction "A7_20") (pintype "input"))
      (node (ref "IC9") (pin "20") (pinfunction "A7_20") (pintype "input"))
    )
    (net (code "254") (name "RAM_A17") (class "Default")
      (node (ref "IC7") (pin "102") (pinfunction "PB26B_102") (pintype "bidirectional"))
      (node (ref "IC8") (pin "21") (pinfunction "A8_21") (pintype "input"))
      (node (ref "IC9") (pin "21") (pinfunction "A8_21") (pintype "input"))
    )
    (net (code "255") (name "RAM_BHE") (class "Default")
      (node (ref "IC7") (pin "84") (pinfunction "PB18A/PCLKT4_0_84") (pintype "bidirectional"))
      (node (ref "IC8") (pin "40") (pinfunction "~{BHE}_40") (pintype "output"))
      (node (ref "IC9") (pin "40") (pinfunction "~{BHE}_40") (pintype "output"))
    )
    (net (code "256") (name "RAM_BLE") (class "Default")
      (node (ref "IC7") (pin "85") (pinfunction "PB18B/PCLKC4_0_85") (pintype "bidirectional"))
      (node (ref "IC8") (pin "39") (pinfunction "~{BLE}_39") (pintype "output"))
      (node (ref "IC9") (pin "39") (pinfunction "~{BLE}_39") (pintype "output"))
    )
    (net (code "257") (name "RAM_D0") (class "Default")
      (node (ref "IC7") (pin "54") (pinfunction "PB5B/VREF1_5_54") (pintype "bidirectional"))
      (node (ref "IC8") (pin "7") (pinfunction "D0_7") (pintype "tri_state"))
      (node (ref "IC9") (pin "7") (pinfunction "D0_7") (pintype "tri_state"))
    )
    (net (code "258") (name "RAM_D1") (class "Default")
      (node (ref "IC7") (pin "55") (pinfunction "PB6A/DQS_55") (pintype "bidirectional"))
      (node (ref "IC8") (pin "8") (pinfunction "D1_8") (pintype "tri_state"))
      (node (ref "IC9") (pin "8") (pinfunction "D1_8") (pintype "tri_state"))
    )
    (net (code "259") (name "RAM_D2") (class "Default")
      (node (ref "IC7") (pin "56") (pinfunction "PB6B_56") (pintype "bidirectional"))
      (node (ref "IC8") (pin "9") (pinfunction "D2_9") (pintype "tri_state"))
      (node (ref "IC9") (pin "9") (pinfunction "D2_9") (pintype "tri_state"))
    )
    (net (code "260") (name "RAM_D3") (class "Default")
      (node (ref "IC7") (pin "57") (pinfunction "PB7A_57") (pintype "bidirectional"))
      (node (ref "IC8") (pin "10") (pinfunction "D3_10") (pintype "tri_state"))
      (node (ref "IC9") (pin "10") (pinfunction "D3_10") (pintype "tri_state"))
    )
    (net (code "261") (name "RAM_D4") (class "Default")
      (node (ref "IC7") (pin "58") (pinfunction "PB7B_58") (pintype "bidirectional"))
      (node (ref "IC8") (pin "13") (pinfunction "D4_13") (pintype "tri_state"))
      (node (ref "IC9") (pin "13") (pinfunction "D4_13") (pintype "tri_state"))
    )
    (net (code "262") (name "RAM_D5") (class "Default")
      (node (ref "IC7") (pin "60") (pinfunction "PB8A_60") (pintype "bidirectional"))
      (node (ref "IC8") (pin "14") (pinfunction "D5_14") (pintype "tri_state"))
      (node (ref "IC9") (pin "14") (pinfunction "D5_14") (pintype "tri_state"))
    )
    (net (code "263") (name "RAM_D6") (class "Default")
      (node (ref "IC7") (pin "61") (pinfunction "PB8B/VREF2_5_61") (pintype "bidirectional"))
      (node (ref "IC8") (pin "15") (pinfunction "D6_15") (pintype "tri_state"))
      (node (ref "IC9") (pin "15") (pinfunction "D6_15") (pintype "tri_state"))
    )
    (net (code "264") (name "RAM_D7") (class "Default")
      (node (ref "IC7") (pin "62") (pinfunction "PB9A_62") (pintype "bidirectional"))
      (node (ref "IC8") (pin "16") (pinfunction "D7_16") (pintype "tri_state"))
      (node (ref "IC9") (pin "16") (pinfunction "D7_16") (pintype "tri_state"))
    )
    (net (code "265") (name "RAM_D8") (class "Default")
      (node (ref "IC7") (pin "63") (pinfunction "PB9B_63") (pintype "bidirectional"))
      (node (ref "IC8") (pin "29") (pinfunction "D8_29") (pintype "tri_state"))
      (node (ref "IC9") (pin "29") (pinfunction "D8_29") (pintype "tri_state"))
    )
    (net (code "266") (name "RAM_D9") (class "Default")
      (node (ref "IC7") (pin "65") (pinfunction "PB10A_65") (pintype "bidirectional"))
      (node (ref "IC8") (pin "30") (pinfunction "D9_30") (pintype "tri_state"))
      (node (ref "IC9") (pin "30") (pinfunction "D9_30") (pintype "tri_state"))
    )
    (net (code "267") (name "RAM_D10") (class "Default")
      (node (ref "IC7") (pin "66") (pinfunction "PB10B_66") (pintype "bidirectional"))
      (node (ref "IC8") (pin "31") (pinfunction "D10_31") (pintype "tri_state"))
      (node (ref "IC9") (pin "31") (pinfunction "D10_31") (pintype "tri_state"))
    )
    (net (code "268") (name "RAM_D11") (class "Default")
      (node (ref "IC7") (pin "67") (pinfunction "PB11A_67") (pintype "bidirectional"))
      (node (ref "IC8") (pin "32") (pinfunction "D11_32") (pintype "tri_state"))
      (node (ref "IC9") (pin "32") (pinfunction "D11_32") (pintype "tri_state"))
    )
    (net (code "269") (name "RAM_D12") (class "Default")
      (node (ref "IC7") (pin "68") (pinfunction "PB11B_68") (pintype "bidirectional"))
      (node (ref "IC8") (pin "35") (pinfunction "D12_35") (pintype "tri_state"))
      (node (ref "IC9") (pin "35") (pinfunction "D12_35") (pintype "tri_state"))
    )
    (net (code "270") (name "RAM_D13") (class "Default")
      (node (ref "IC7") (pin "70") (pinfunction "PB12A_70") (pintype "bidirectional"))
      (node (ref "IC8") (pin "36") (pinfunction "D13_36") (pintype "tri_state"))
      (node (ref "IC9") (pin "36") (pinfunction "D13_36") (pintype "tri_state"))
    )
    (net (code "271") (name "RAM_D14") (class "Default")
      (node (ref "IC7") (pin "71") (pinfunction "PB13B_71") (pintype "bidirectional"))
      (node (ref "IC8") (pin "37") (pinfunction "D14_37") (pintype "tri_state"))
      (node (ref "IC9") (pin "37") (pinfunction "D14_37") (pintype "tri_state"))
    )
    (net (code "272") (name "RAM_D15") (class "Default")
      (node (ref "IC7") (pin "72") (pinfunction "PB14A/DQS_72") (pintype "bidirectional"))
      (node (ref "IC8") (pin "38") (pinfunction "D15_38") (pintype "tri_state"))
      (node (ref "IC9") (pin "38") (pinfunction "D15_38") (pintype "tri_state"))
    )
    (net (code "273") (name "RAM_OE") (class "Default")
      (node (ref "IC7") (pin "83") (pinfunction "PB17B_83") (pintype "bidirectional"))
      (node (ref "IC8") (pin "41") (pinfunction "~{OE}_41") (pintype "input"))
      (node (ref "IC9") (pin "41") (pinfunction "~{OE}_41") (pintype "input"))
    )
    (net (code "274") (name "RAM_WE") (class "Default")
      (node (ref "IC7") (pin "73") (pinfunction "PB14B_73") (pintype "bidirectional"))
      (node (ref "IC8") (pin "17") (pinfunction "~{WE}_17") (pintype "input"))
      (node (ref "IC9") (pin "17") (pinfunction "~{WE}_17") (pintype "input"))
    )
    (net (code "275") (name "S1_CTS") (class "Default")
      (node (ref "IC11") (pin "12") (pinfunction "R1OUT_12") (pintype "output"))
      (node (ref "IC7") (pin "17") (pinfunction "PL7A/DQS_17") (pintype "bidirectional"))
    )
    (net (code "276") (name "S1_RTS") (class "Default")
      (node (ref "IC11") (pin "11") (pinfunction "T1IN_11") (pintype "input"))
      (node (ref "IC7") (pin "15") (pinfunction "PL6B/VREF2_7_15") (pintype "bidirectional"))
    )
    (net (code "277") (name "S1_RXD") (class "Default")
      (node (ref "IC11") (pin "9") (pinfunction "R2OUT_9") (pintype "output"))
      (node (ref "IC7") (pin "14") (pinfunction "PL5A/VREF1_7_14") (pintype "bidirectional"))
    )
    (net (code "278") (name "S1_TXD") (class "Default")
      (node (ref "IC11") (pin "10") (pinfunction "T2IN_10") (pintype "input"))
      (node (ref "IC7") (pin "12") (pinfunction "PL4B_12") (pintype "bidirectional"))
    )
    (net (code "279") (name "SD0_CS") (class "Default")
      (node (ref "CON3") (pin "1") (pinfunction "1_1") (pintype "input"))
      (node (ref "IC7") (pin "22") (pinfunction "PL9A_22") (pintype "bidirectional"))
    )
    (net (code "280") (name "SD0_DI") (class "Default")
      (node (ref "CON3") (pin "2") (pinfunction "2_2") (pintype "input"))
      (node (ref "IC7") (pin "21") (pinfunction "PL8B/LUM0_PLLC_IN_A_21") (pintype "bidirectional"))
    )
    (net (code "281") (name "SD0_DO") (class "Default")
      (node (ref "CON3") (pin "7") (pinfunction "7_7") (pintype "input"))
      (node (ref "IC7") (pin "18") (pinfunction "PL7B_18") (pintype "bidirectional"))
    )
    (net (code "282") (name "SD0_SCLK") (class "Default")
      (node (ref "CON3") (pin "5") (pinfunction "5_5") (pintype "input"))
      (node (ref "IC7") (pin "20") (pinfunction "PL8A/LUM0_PLLT_IN_A_20") (pintype "bidirectional"))
    )
    (net (code "283") (name "SIZ0") (class "Default")
      (node (ref "IC6") (pin "6") (pinfunction "1/10_6") (pintype "bidirectional"))
      (node (ref "J1") (pin "B29") (pinfunction "B29_B29") (pintype "passive"))
    )
    (net (code "284") (name "SIZ1") (class "Default")
      (node (ref "IC6") (pin "5") (pinfunction "1/9_5") (pintype "bidirectional"))
      (node (ref "J1") (pin "B28") (pinfunction "B28_B28") (pintype "passive"))
    )
    (net (code "285") (name "TCK") (class "Default")
      (node (ref "IC6") (pin "11") (pinfunction "TCK_11") (pintype "input"))
      (node (ref "JP15") (pin "3") (pinfunction "3_3") (pintype "passive"))
    )
    (net (code "286") (name "TDI") (class "Default")
      (node (ref "IC6") (pin "9") (pinfunction "TDI_9") (pintype "input"))
      (node (ref "JP15") (pin "5") (pinfunction "5_5") (pintype "passive"))
    )
    (net (code "287") (name "TDO") (class "Default")
      (node (ref "IC6") (pin "24") (pinfunction "TDO_24") (pintype "output"))
      (node (ref "JP15") (pin "4") (pinfunction "4_4") (pintype "passive"))
    )
    (net (code "288") (name "TMS") (class "Default")
      (node (ref "IC6") (pin "10") (pinfunction "TMS_10") (pintype "input"))
      (node (ref "JP15") (pin "6") (pinfunction "6_6") (pintype "passive"))
    )
    (net (code "289") (name "VCC") (class "Default")
      (node (ref "C1") (pin "1") (pinfunction "1_1") (pintype "passive"))
      (node (ref "C10") (pin "1") (pinfunction "1_1") (pintype "passive"))
      (node (ref "C11") (pin "+") (pinfunction "+_+") (pintype "passive"))
      (node (ref "C12") (pin "+") (pinfunction "+_+") (pintype "passive"))
      (node (ref "C13") (pin "1") (pinfunction "1_1") (pintype "passive"))
      (node (ref "C14") (pin "1") (pinfunction "1_1") (pintype "passive"))
      (node (ref "C15") (pin "+") (pinfunction "+_+") (pintype "passive"))
      (node (ref "C16") (pin "1") (pinfunction "1_1") (pintype "passive"))
      (node (ref "C17") (pin "1") (pinfunction "1_1") (pintype "passive"))
      (node (ref "C18") (pin "+") (pinfunction "+_+") (pintype "passive"))
      (node (ref "C19") (pin "+") (pinfunction "+_+") (pintype "passive"))
      (node (ref "C2") (pin "1") (pinfunction "1_1") (pintype "passive"))
      (node (ref "C20") (pin "+") (pinfunction "+_+") (pintype "passive"))
      (node (ref "C21") (pin "1") (pinfunction "1_1") (pintype "passive"))
      (node (ref "C22") (pin "+") (pinfunction "+_+") (pintype "passive"))
      (node (ref "C23") (pin "1") (pinfunction "1_1") (pintype "passive"))
      (node (ref "C24") (pin "+") (pinfunction "+_+") (pintype "passive"))
      (node (ref "C25") (pin "1") (pinfunction "1_1") (pintype "passive"))
      (node (ref "C26") (pin "1") (pinfunction "1_1") (pintype "passive"))
      (node (ref "C27") (pin "1") (pinfunction "1_1") (pintype "passive"))
      (node (ref "C29") (pin "1") (pinfunction "1_1") (pintype "passive"))
      (node (ref "C3") (pin "1") (pinfunction "1_1") (pintype "passive"))
      (node (ref "C31") (pin "1") (pinfunction "1_1") (pintype "passive"))
      (node (ref "C32") (pin "1") (pinfunction "1_1") (pintype "passive"))
      (node (ref "C34") (pin "1") (pinfunction "1_1") (pintype "passive"))
      (node (ref "C36") (pin "1") (pinfunction "1_1") (pintype "passive"))
      (node (ref "C37") (pin "1") (pinfunction "1_1") (pintype "passive"))
      (node (ref "C38") (pin "1") (pinfunction "1_1") (pintype "passive"))
      (node (ref "C39") (pin "1") (pinfunction "1_1") (pintype "passive"))
      (node (ref "C4") (pin "+") (pinfunction "+_+") (pintype "passive"))
      (node (ref "C40") (pin "1") (pinfunction "1_1") (pintype "passive"))
      (node (ref "C41") (pin "1") (pinfunction "1_1") (pintype "passive"))
      (node (ref "C42") (pin "1") (pinfunction "1_1") (pintype "passive"))
      (node (ref "C43") (pin "1") (pinfunction "1_1") (pintype "passive"))
      (node (ref "C44") (pin "1") (pinfunction "1_1") (pintype "passive"))
      (node (ref "C45") (pin "1") (pinfunction "1_1") (pintype "passive"))
      (node (ref "C46") (pin "1") (pinfunction "1_1") (pintype "passive"))
      (node (ref "C47") (pin "1") (pinfunction "1_1") (pintype "passive"))
      (node (ref "C48") (pin "1") (pinfunction "1_1") (pintype "passive"))
      (node (ref "C5") (pin "1") (pinfunction "1_1") (pintype "passive"))
      (node (ref "C51") (pin "1") (pinfunction "1_1") (pintype "passive"))
      (node (ref "C53") (pin "1") (pinfunction "1_1") (pintype "passive"))
      (node (ref "C6") (pin "1") (pinfunction "1_1") (pintype "passive"))
      (node (ref "C7") (pin "+") (pinfunction "+_+") (pintype "passive"))
      (node (ref "C8") (pin "1") (pinfunction "1_1") (pintype "passive"))
      (node (ref "C9") (pin "+") (pinfunction "+_+") (pintype "passive"))
      (node (ref "CON1") (pin "13") (pinfunction "VCC2_13") (pintype "power_in"))
      (node (ref "CON1") (pin "36") (pinfunction "/WE_36") (pintype "input"))
      (node (ref "CON1") (pin "38") (pinfunction "VCC1_38") (pintype "power_in"))
      (node (ref "CON3") (pin "4") (pinfunction "4_4") (pintype "input"))
      (node (ref "D1") (pin "2") (pinfunction "C_2") (pintype "passive"))
      (node (ref "D2") (pin "2") (pinfunction "C_2") (pintype "passive"))
      (node (ref "D3") (pin "2") (pinfunction "C_2") (pintype "passive"))
      (node (ref "D4") (pin "2") (pinfunction "C_2") (pintype "passive"))
      (node (ref "IC10") (pin "2") (pinfunction "OUT_2") (pintype "power_in"))
      (node (ref "IC10") (pin "4") (pinfunction "OUT_4") (pintype "power_in"))
      (node (ref "IC11") (pin "16") (pinfunction "VCC_16") (pintype "power_in"))
      (node (ref "IC6") (pin "26") (pinfunction "VCCIO_26") (pintype "power_in"))
      (node (ref "IC7") (pin "1") (pinfunction "CFG1_1") (pintype "input"))
      (node (ref "IC7") (pin "107") (pinfunction "VCC_107") (pintype "power_in"))
      (node (ref "IC7") (pin "115") (pinfunction "VCCIO3_115") (pintype "power_in"))
      (node (ref "IC7") (pin "125") (pinfunction "VCCIO3_125") (pintype "power_in"))
      (node (ref "IC7") (pin "128") (pinfunction "VCCP1_128") (pintype "power_in"))
      (node (ref "IC7") (pin "13") (pinfunction "VCCIO7_13") (pintype "power_in"))
      (node (ref "IC7") (pin "140") (pinfunction "VCCIO2_140") (pintype "power_in"))
      (node (ref "IC7") (pin "149") (pinfunction "VCCIO2_149") (pintype "power_in"))
      (node (ref "IC7") (pin "151") (pinfunction "VCC_151") (pintype "power_in"))
      (node (ref "IC7") (pin "152") (pinfunction "VCCAUX_152") (pintype "power_in"))
      (node (ref "IC7") (pin "154") (pinfunction "VCCJ_154") (pintype "power_in"))
      (node (ref "IC7") (pin "158") (pinfunction "VCC_158") (pintype "power_in"))
      (node (ref "IC7") (pin "167") (pinfunction "VCCIO1_167") (pintype "power_in"))
      (node (ref "IC7") (pin "177") (pinfunction "VCCIO1_177") (pintype "power_in"))
      (node (ref "IC7") (pin "182") (pinfunction "VCC_182") (pintype "power_in"))
      (node (ref "IC7") (pin "189") (pinfunction "VCCIO0_189") (pintype "power_in"))
      (node (ref "IC7") (pin "19") (pinfunction "VCC_19") (pintype "power_in"))
      (node (ref "IC7") (pin "199") (pinfunction "VCCIO0_199") (pintype "power_in"))
      (node (ref "IC7") (pin "208") (pinfunction "CFG0_208") (pintype "input"))
      (node (ref "IC7") (pin "23") (pinfunction "VCCIO7_23") (pintype "power_in"))
      (node (ref "IC7") (pin "25") (pinfunction "VCCP0_25") (pintype "power_in"))
      (node (ref "IC7") (pin "28") (pinfunction "VCCIO6_28") (pintype "power_in"))
      (node (ref "IC7") (pin "35") (pinfunction "VCC_35") (pintype "power_in"))
      (node (ref "IC7") (pin "41") (pinfunction "VCCIO6_41") (pintype "power_in"))
      (node (ref "IC7") (pin "50") (pinfunction "VCCAUX_50") (pintype "power_in"))
      (node (ref "IC7") (pin "53") (pinfunction "VCC_53") (pintype "power_in"))
      (node (ref "IC7") (pin "64") (pinfunction "VCCIO5_64") (pintype "power_in"))
      (node (ref "IC7") (pin "74") (pinfunction "VCCIO5_74") (pintype "power_in"))
      (node (ref "IC7") (pin "80") (pinfunction "VCC_80") (pintype "power_in"))
      (node (ref "IC7") (pin "87") (pinfunction "VCCIO4_87") (pintype "power_in"))
      (node (ref "IC7") (pin "97") (pinfunction "VCCIO4_97") (pintype "power_in"))
      (node (ref "IC8") (pin "11") (pinfunction "VCC_11") (pintype "power_in"))
      (node (ref "IC8") (pin "33") (pinfunction "VCC2_33") (pintype "power_in"))
      (node (ref "IC9") (pin "11") (pinfunction "VCC_11") (pintype "power_in"))
      (node (ref "IC9") (pin "33") (pinfunction "VCC2_33") (pintype "power_in"))
      (node (ref "JP15") (pin "1") (pinfunction "1_1") (pintype "passive"))
      (node (ref "JP16") (pin "6") (pinfunction "6_6") (pintype "passive"))
      (node (ref "LED3") (pin "A") (pinfunction "A_A") (pintype "passive"))
      (node (ref "LED4") (pin "A") (pinfunction "A_A") (pintype "passive"))
      (node (ref "OSZI1") (pin "1") (pinfunction "EN_1") (pintype "passive"))
      (node (ref "OSZI1") (pin "8") (pinfunction "VCC_8") (pintype "power_in"))
      (node (ref "R10") (pin "1") (pinfunction "1_1") (pintype "passive"))
      (node (ref "R12") (pin "2") (pinfunction "2_2") (pintype "passive"))
      (node (ref "R13") (pin "2") (pinfunction "2_2") (pintype "passive"))
      (node (ref "R14") (pin "2") (pinfunction "2_2") (pintype "passive"))
      (node (ref "R15") (pin "2") (pinfunction "2_2") (pintype "passive"))
      (node (ref "R16") (pin "2") (pinfunction "2_2") (pintype "passive"))
      (node (ref "R17") (pin "2") (pinfunction "2_2") (pintype "passive"))
      (node (ref "R18") (pin "2") (pinfunction "2_2") (pintype "passive"))
      (node (ref "R19") (pin "2") (pinfunction "2_2") (pintype "passive"))
      (node (ref "R4") (pin "2") (pinfunction "2_2") (pintype "passive"))
      (node (ref "R6") (pin "1") (pinfunction "1_1") (pintype "passive"))
    )
    (net (code "290") (name "VGA_BL0") (class "Default")
      (node (ref "IC7") (pin "32") (pinfunction "PL17B/PCLKC6_0_32") (pintype "bidirectional"))
      (node (ref "R35") (pin "1") (pinfunction "1_1") (pintype "passive"))
    )
    (net (code "291") (name "VGA_BL1") (class "Default")
      (node (ref "IC7") (pin "33") (pinfunction "PL18A_33") (pintype "bidirectional"))
      (node (ref "R34") (pin "1") (pinfunction "1_1") (pintype "passive"))
    )
    (net (code "292") (name "VGA_BL2") (class "Default")
      (node (ref "IC7") (pin "34") (pinfunction "PL18B_34") (pintype "bidirectional"))
      (node (ref "R33") (pin "1") (pinfunction "1_1") (pintype "passive"))
    )
    (net (code "293") (name "VGA_GR0") (class "Default")
      (node (ref "IC7") (pin "36") (pinfunction "PL21A_36") (pintype "bidirectional"))
      (node (ref "R32") (pin "1") (pinfunction "1_1") (pintype "passive"))
    )
    (net (code "294") (name "VGA_GR1") (class "Default")
      (node (ref "IC7") (pin "37") (pinfunction "PL21B_37") (pintype "bidirectional"))
      (node (ref "R31") (pin "1") (pinfunction "1_1") (pintype "passive"))
    )
    (net (code "295") (name "VGA_GR2") (class "Default")
      (node (ref "IC7") (pin "39") (pinfunction "PL22A/VREF1_6_39") (pintype "bidirectional"))
      (node (ref "R30") (pin "1") (pinfunction "1_1") (pintype "passive"))
    )
    (net (code "296") (name "VGA_HSYNC") (class "Default")
      (node (ref "IC7") (pin "27") (pinfunction "PL15B_27") (pintype "bidirectional"))
      (node (ref "R37") (pin "2") (pinfunction "2_2") (pintype "passive"))
    )
    (net (code "297") (name "VGA_RD0") (class "Default")
      (node (ref "IC7") (pin "40") (pinfunction "PL23B/VREF2_6_40") (pintype "bidirectional"))
      (node (ref "R29") (pin "1") (pinfunction "1_1") (pintype "passive"))
    )
    (net (code "298") (name "VGA_RD1") (class "Default")
      (node (ref "IC7") (pin "42") (pinfunction "PL24A/DQS_42") (pintype "bidirectional"))
      (node (ref "R28") (pin "1") (pinfunction "1_1") (pintype "passive"))
    )
    (net (code "299") (name "VGA_RD2") (class "Default")
      (node (ref "IC7") (pin "43") (pinfunction "PL24B_43") (pintype "bidirectional"))
      (node (ref "R27") (pin "1") (pinfunction "1_1") (pintype "passive"))
    )
    (net (code "300") (name "VGA_VSYNC") (class "Default")
      (node (ref "IC7") (pin "24") (pinfunction "PL9B_24") (pintype "bidirectional"))
      (node (ref "R36") (pin "2") (pinfunction "2_2") (pintype "passive"))
    )
    (net (code "301") (name "unconnected-(CON2-Pad3)") (class "Default")
      (node (ref "CON2") (pin "3") (pinfunction "3_3") (pintype "passive"))
    )
    (net (code "302") (name "unconnected-(CON2-Pad4)") (class "Default")
      (node (ref "CON2") (pin "4") (pinfunction "4_4") (pintype "passive"))
    )
    (net (code "303") (name "unconnected-(CON4-Pad4)") (class "Default")
      (node (ref "CON4") (pin "4") (pinfunction "4_4") (pintype "passive"))
    )
    (net (code "304") (name "unconnected-(CON4-Pad5)") (class "Default")
      (node (ref "CON4") (pin "5") (pinfunction "5_5") (pintype "passive"))
    )
    (net (code "305") (name "unconnected-(CON4-Pad9)") (class "Default")
      (node (ref "CON4") (pin "9") (pinfunction "9_9") (pintype "passive"))
    )
    (net (code "306") (name "unconnected-(CON4-Pad15)") (class "Default")
      (node (ref "CON4") (pin "15") (pinfunction "15_15") (pintype "passive"))
    )
    (net (code "307") (name "unconnected-(CON4G-2-Pad1-2)") (class "Default")
      (node (ref "CON4") (pin "1-2") (pinfunction "2_1-2") (pintype "passive"))
    )
    (net (code "308") (name "unconnected-(CON4G-6-Pad1-6)") (class "Default")
      (node (ref "CON4") (pin "1-6") (pinfunction "6_1-6") (pintype "passive"))
    )
    (net (code "309") (name "unconnected-(CON4H-2-Pad2-2)") (class "Default")
      (node (ref "CON4") (pin "2-2") (pinfunction "2_2-2") (pintype "passive"))
    )
    (net (code "310") (name "unconnected-(CON4H-6-Pad2-6)") (class "Default")
      (node (ref "CON4") (pin "2-6") (pinfunction "6_2-6") (pintype "passive"))
    )
    (net (code "311") (name "unconnected-(IC8B-NC-Pad28)") (class "Default")
      (node (ref "IC8") (pin "28") (pinfunction "NC_28") (pintype "no_connect"))
    )
    (net (code "312") (name "unconnected-(IC9B-NC-Pad28)") (class "Default")
      (node (ref "IC9") (pin "28") (pinfunction "NC_28") (pintype "no_connect"))
    )
    (net (code "313") (name "unconnected-(J1-PadA13)") (class "Default")
      (node (ref "J1") (pin "A13") (pinfunction "A13_A13") (pintype "passive"))
    )
    (net (code "314") (name "unconnected-(J1-PadA20)") (class "Default")
      (node (ref "J1") (pin "A20") (pinfunction "A20_A20") (pintype "passive"))
    )
    (net (code "315") (name "unconnected-(J1-PadA21)") (class "Default")
      (node (ref "J1") (pin "A21") (pinfunction "A21_A21") (pintype "passive"))
    )
    (net (code "316") (name "unconnected-(J1-PadA28)") (class "Default")
      (node (ref "J1") (pin "A28") (pinfunction "A28_A28") (pintype "passive"))
    )
    (net (code "317") (name "unconnected-(J1-PadC13)") (class "Default")
      (node (ref "J1") (pin "C13") (pinfunction "C13_C13") (pintype "passive"))
    )
    (net (code "318") (name "unconnected-(J1-PadC23)") (class "Default")
      (node (ref "J1") (pin "C23") (pinfunction "C23_C23") (pintype "passive"))
    )
    (net (code "319") (name "unconnected-(J1-PadC26)") (class "Default")
      (node (ref "J1") (pin "C26") (pinfunction "C26_C26") (pintype "passive"))
    )
    (net (code "320") (name "unconnected-(J1-PadC29)") (class "Default")
      (node (ref "J1") (pin "C29") (pinfunction "C29_C29") (pintype "passive"))
    )
    (net (code "321") (name "unconnected-(JP16-Pad9)") (class "Default")
      (node (ref "JP16") (pin "9") (pinfunction "9_9") (pintype "passive"))
    )
    (net (code "322") (name "unconnected-(JP16-Pad10)") (class "Default")
      (node (ref "JP16") (pin "10") (pinfunction "10_10") (pintype "passive"))
    )
    (net (code "323") (name "unconnected-(JP20-Pad1)") (class "Default")
      (node (ref "JP20") (pin "1") (pinfunction "1_1") (pintype "passive"))
    )
    (net (code "324") (name "unconnected-(JP20-Pad4)") (class "Default")
      (node (ref "JP20") (pin "4") (pinfunction "4_4") (pintype "passive"))
    )
    (net (code "325") (name "unconnected-(JP20-Pad6)") (class "Default")
      (node (ref "JP20") (pin "6") (pinfunction "6_6") (pintype "passive"))
    )
    (net (code "326") (name "unconnected-(JP20-Pad9)") (class "Default")
      (node (ref "JP20") (pin "9") (pinfunction "9_9") (pintype "passive"))
    )
    (net (code "327") (name "unconnected-(JP20-Pad10)") (class "Default")
      (node (ref "JP20") (pin "10") (pinfunction "10_10") (pintype "passive"))
    )
    (net (code "328") (name "unconnected-(JP37-Pad1)") (class "Default")
      (node (ref "JP37") (pin "1") (pinfunction "1_1") (pintype "passive"))
    )
    (net (code "329") (name "unconnected-(JP38-Pad1)") (class "Default")
      (node (ref "JP38") (pin "1") (pinfunction "1_1") (pintype "passive"))
    )
    (net (code "330") (name "unconnected-(JP39-Pad1)") (class "Default")
      (node (ref "JP39") (pin "1") (pinfunction "1_1") (pintype "passive"))
    )
    (net (code "331") (name "unconnected-(JP40-Pad1)") (class "Default")
      (node (ref "JP40") (pin "1") (pinfunction "1_1") (pintype "passive"))
    )
    (net (code "332") (name "unconnected-(JP41-Pad1)") (class "Default")
      (node (ref "JP41") (pin "1") (pinfunction "1_1") (pintype "passive"))
    )
    (net (code "333") (name "unconnected-(JP42-Pad1)") (class "Default")
      (node (ref "JP42") (pin "1") (pinfunction "1_1") (pintype "passive"))
    )
    (net (code "334") (name "unconnected-(JP43-Pad1)") (class "Default")
      (node (ref "JP43") (pin "1") (pinfunction "1_1") (pintype "passive"))
    )
    (net (code "335") (name "unconnected-(JP44-Pad1)") (class "Default")
      (node (ref "JP44") (pin "1") (pinfunction "1_1") (pintype "passive"))
    )
    (net (code "336") (name "unconnected-(JP45-Pad1)") (class "Default")
      (node (ref "JP45") (pin "1") (pinfunction "1_1") (pintype "passive"))
    )
    (net (code "337") (name "unconnected-(JP46-Pad1)") (class "Default")
      (node (ref "JP46") (pin "1") (pinfunction "1_1") (pintype "passive"))
    )
    (net (code "338") (name "unconnected-(JP47-Pad1)") (class "Default")
      (node (ref "JP47") (pin "1") (pinfunction "1_1") (pintype "passive"))
    )
    (net (code "339") (name "unconnected-(JP48-Pad1)") (class "Default")
      (node (ref "JP48") (pin "1") (pinfunction "1_1") (pintype "passive"))
    )
    (net (code "340") (name "unconnected-(JP49-Pad1)") (class "Default")
      (node (ref "JP49") (pin "1") (pinfunction "1_1") (pintype "passive"))
    )
    (net (code "341") (name "unconnected-(JP50-Pad1)") (class "Default")
      (node (ref "JP50") (pin "1") (pinfunction "1_1") (pintype "passive"))
    )
    (net (code "342") (name "unconnected-(JP51-Pad1)") (class "Default")
      (node (ref "JP51") (pin "1") (pinfunction "1_1") (pintype "passive"))
    )
    (net (code "343") (name "unconnected-(JP52-Pad1)") (class "Default")
      (node (ref "JP52") (pin "1") (pinfunction "1_1") (pintype "passive"))
    )
    (net (code "344") (name "unconnected-(JP53-Pad1)") (class "Default")
      (node (ref "JP53") (pin "1") (pinfunction "1_1") (pintype "passive"))
    )
    (net (code "345") (name "unconnected-(JP54-Pad1)") (class "Default")
      (node (ref "JP54") (pin "1") (pinfunction "1_1") (pintype "passive"))
    )
    (net (code "346") (name "unconnected-(JP55-Pad1)") (class "Default")
      (node (ref "JP55") (pin "1") (pinfunction "1_1") (pintype "passive"))
    )
    (net (code "347") (name "unconnected-(JP56-Pad1)") (class "Default")
      (node (ref "JP56") (pin "1") (pinfunction "1_1") (pintype "passive"))
    )
    (net (code "348") (name "unconnected-(JP57-Pad1)") (class "Default")
      (node (ref "JP57") (pin "1") (pinfunction "1_1") (pintype "passive"))
    )
    (net (code "349") (name "unconnected-(JP58-Pad1)") (class "Default")
      (node (ref "JP58") (pin "1") (pinfunction "1_1") (pintype "passive"))
    )
    (net (code "350") (name "unconnected-(JP59-Pad1)") (class "Default")
      (node (ref "JP59") (pin "1") (pinfunction "1_1") (pintype "passive"))
    )
    (net (code "351") (name "unconnected-(JP60-Pad1)") (class "Default")
      (node (ref "JP60") (pin "1") (pinfunction "1_1") (pintype "passive"))
    )
    (net (code "352") (name "unconnected-(JP61-Pad1)") (class "Default")
      (node (ref "JP61") (pin "1") (pinfunction "1_1") (pintype "passive"))
    )
    (net (code "353") (name "unconnected-(JP62-Pad1)") (class "Default")
      (node (ref "JP62") (pin "1") (pinfunction "1_1") (pintype "passive"))
    )
    (net (code "354") (name "unconnected-(JP69-Pad1)") (class "Default")
      (node (ref "JP69") (pin "1") (pinfunction "1_1") (pintype "passive"))
    )
    (net (code "355") (name "unconnected-(JP70-Pad1)") (class "Default")
      (node (ref "JP70") (pin "1") (pinfunction "1_1") (pintype "passive"))
    )
    (net (code "356") (name "unconnected-(JP71-Pad1)") (class "Default")
      (node (ref "JP71") (pin "1") (pinfunction "1_1") (pintype "passive"))
    )
    (net (code "357") (name "unconnected-(JP72-Pad1)") (class "Default")
      (node (ref "JP72") (pin "1") (pinfunction "1_1") (pintype "passive"))
    )
    (net (code "358") (name "unconnected-(JP73-Pad1)") (class "Default")
      (node (ref "JP73") (pin "1") (pinfunction "1_1") (pintype "passive"))
    )
    (net (code "359") (name "unconnected-(JP74-Pad1)") (class "Default")
      (node (ref "JP74") (pin "1") (pinfunction "1_1") (pintype "passive"))
    )
    (net (code "360") (name "unconnected-(JP75-Pad1)") (class "Default")
      (node (ref "JP75") (pin "1") (pinfunction "1_1") (pintype "passive"))
    )
    (net (code "361") (name "unconnected-(JP76-Pad1)") (class "Default")
      (node (ref "JP76") (pin "1") (pinfunction "1_1") (pintype "passive"))
    )
    (net (code "362") (name "unconnected-(JP77-Pad1)") (class "Default")
      (node (ref "JP77") (pin "1") (pinfunction "1_1") (pintype "passive"))
    )
    (net (code "363") (name "unconnected-(JP78-Pad1)") (class "Default")
      (node (ref "JP78") (pin "1") (pinfunction "1_1") (pintype "passive"))
    )
    (net (code "364") (name "unconnected-(JP79-Pad1)") (class "Default")
      (node (ref "JP79") (pin "1") (pinfunction "1_1") (pintype "passive"))
    )
    (net (code "365") (name "unconnected-(JP80-Pad1)") (class "Default")
      (node (ref "JP80") (pin "1") (pinfunction "1_1") (pintype "passive"))
    )
    (net (code "366") (name "unconnected-(JP81-Pad1)") (class "Default")
      (node (ref "JP81") (pin "1") (pinfunction "1_1") (pintype "passive"))
    )
    (net (code "367") (name "unconnected-(JP82-Pad1)") (class "Default")
      (node (ref "JP82") (pin "1") (pinfunction "1_1") (pintype "passive"))
    )
    (net (code "368") (name "unconnected-(JP83-Pad1)") (class "Default")
      (node (ref "JP83") (pin "1") (pinfunction "1_1") (pintype "passive"))
    )
    (net (code "369") (name "unconnected-(JP84-Pad1)") (class "Default")
      (node (ref "JP84") (pin "1") (pinfunction "1_1") (pintype "passive"))
    )
    (net (code "370") (name "unconnected-(JP85-Pad1)") (class "Default")
      (node (ref "JP85") (pin "1") (pinfunction "1_1") (pintype "passive"))
    )
    (net (code "371") (name "unconnected-(JP86-Pad1)") (class "Default")
      (node (ref "JP86") (pin "1") (pinfunction "1_1") (pintype "passive"))
    )
    (net (code "372") (name "unconnected-(JP87-Pad1)") (class "Default")
      (node (ref "JP87") (pin "1") (pinfunction "1_1") (pintype "passive"))
    )
    (net (code "373") (name "unconnected-(JP88-Pad1)") (class "Default")
      (node (ref "JP88") (pin "1") (pinfunction "1_1") (pintype "passive"))
    )
    (net (code "374") (name "unconnected-(JP89-Pad1)") (class "Default")
      (node (ref "JP89") (pin "1") (pinfunction "1_1") (pintype "passive"))
    )
    (net (code "375") (name "unconnected-(JP90-Pad1)") (class "Default")
      (node (ref "JP90") (pin "1") (pinfunction "1_1") (pintype "passive"))
    )
    (net (code "376") (name "unconnected-(JP91-Pad1)") (class "Default")
      (node (ref "JP91") (pin "1") (pinfunction "1_1") (pintype "passive"))
    )
    (net (code "377") (name "unconnected-(JP92-Pad1)") (class "Default")
      (node (ref "JP92") (pin "1") (pinfunction "1_1") (pintype "passive"))
    )
    (net (code "378") (name "unconnected-(JP93-Pad1)") (class "Default")
      (node (ref "JP93") (pin "1") (pinfunction "1_1") (pintype "passive"))
    )
    (net (code "379") (name "unconnected-(JP94-Pad1)") (class "Default")
      (node (ref "JP94") (pin "1") (pinfunction "1_1") (pintype "passive"))
    )
    (net (code "380") (name "unconnected-(JP95-Pad1)") (class "Default")
      (node (ref "JP95") (pin "1") (pinfunction "1_1") (pintype "passive"))
    )
    (net (code "381") (name "unconnected-(JP96-Pad1)") (class "Default")
      (node (ref "JP96") (pin "1") (pinfunction "1_1") (pintype "passive"))
    )
    (net (code "382") (name "unconnected-(JP97-Pad1)") (class "Default")
      (node (ref "JP97") (pin "1") (pinfunction "1_1") (pintype "passive"))
    )
    (net (code "383") (name "unconnected-(JP98-Pad1)") (class "Default")
      (node (ref "JP98") (pin "1") (pinfunction "1_1") (pintype "passive"))
    )
    (net (code "384") (name "unconnected-(JP99-Pad1)") (class "Default")
      (node (ref "JP99") (pin "1") (pinfunction "1_1") (pintype "passive"))
    )
    (net (code "385") (name "unconnected-(JP100-Pad1)") (class "Default")
      (node (ref "JP100") (pin "1") (pinfunction "1_1") (pintype "passive"))
    )
    (net (code "386") (name "unconnected-(JP101-Pad1)") (class "Default")
      (node (ref "JP101") (pin "1") (pinfunction "1_1") (pintype "passive"))
    )
    (net (code "387") (name "unconnected-(JP102-Pad1)") (class "Default")
      (node (ref "JP102") (pin "1") (pinfunction "1_1") (pintype "passive"))
    )
    (net (code "388") (name "unconnected-(JP103-Pad1)") (class "Default")
      (node (ref "JP103") (pin "1") (pinfunction "1_1") (pintype "passive"))
    )
    (net (code "389") (name "unconnected-(JP104-Pad1)") (class "Default")
      (node (ref "JP104") (pin "1") (pinfunction "1_1") (pintype "passive"))
    )
    (net (code "390") (name "unconnected-(JP105-Pad1)") (class "Default")
      (node (ref "JP105") (pin "1") (pinfunction "1_1") (pintype "passive"))
    )
    (net (code "391") (name "unconnected-(JP106-Pad1)") (class "Default")
      (node (ref "JP106") (pin "1") (pinfunction "1_1") (pintype "passive"))
    )
    (net (code "392") (name "unconnected-(JP107-Pad1)") (class "Default")
      (node (ref "JP107") (pin "1") (pinfunction "1_1") (pintype "passive"))
    )
    (net (code "393") (name "unconnected-(JP108-Pad1)") (class "Default")
      (node (ref "JP108") (pin "1") (pinfunction "1_1") (pintype "passive"))
    )
    (net (code "394") (name "unconnected-(JP109-Pad1)") (class "Default")
      (node (ref "JP109") (pin "1") (pinfunction "1_1") (pintype "passive"))
    )
    (net (code "395") (name "unconnected-(JP110-Pad1)") (class "Default")
      (node (ref "JP110") (pin "1") (pinfunction "1_1") (pintype "passive"))
    )
    (net (code "396") (name "unconnected-(JP111-Pad1)") (class "Default")
      (node (ref "JP111") (pin "1") (pinfunction "1_1") (pintype "passive"))
    )
    (net (code "397") (name "unconnected-(JP112-Pad1)") (class "Default")
      (node (ref "JP112") (pin "1") (pinfunction "1_1") (pintype "passive"))
    )
    (net (code "398") (name "unconnected-(JP113-Pad1)") (class "Default")
      (node (ref "JP113") (pin "1") (pinfunction "1_1") (pintype "passive"))
    )
    (net (code "399") (name "unconnected-(JP114-Pad1)") (class "Default")
      (node (ref "JP114") (pin "1") (pinfunction "1_1") (pintype "passive"))
    )
    (net (code "400") (name "unconnected-(JP115-Pad1)") (class "Default")
      (node (ref "JP115") (pin "1") (pinfunction "1_1") (pintype "passive"))
    )
    (net (code "401") (name "unconnected-(JP116-Pad1)") (class "Default")
      (node (ref "JP116") (pin "1") (pinfunction "1_1") (pintype "passive"))
    )
    (net (code "402") (name "unconnected-(JP117-Pad1)") (class "Default")
      (node (ref "JP117") (pin "1") (pinfunction "1_1") (pintype "passive"))
    )
    (net (code "403") (name "unconnected-(JP118-Pad1)") (class "Default")
      (node (ref "JP118") (pin "1") (pinfunction "1_1") (pintype "passive"))
    )
    (net (code "404") (name "unconnected-(JP119-Pad1)") (class "Default")
      (node (ref "JP119") (pin "1") (pinfunction "1_1") (pintype "passive"))
    )
    (net (code "405") (name "unconnected-(JP120-Pad1)") (class "Default")
      (node (ref "JP120") (pin "1") (pinfunction "1_1") (pintype "passive"))
    )
    (net (code "406") (name "unconnected-(JP121-Pad1)") (class "Default")
      (node (ref "JP121") (pin "1") (pinfunction "1_1") (pintype "passive"))
    )
    (net (code "407") (name "unconnected-(JP122-Pad1)") (class "Default")
      (node (ref "JP122") (pin "1") (pinfunction "1_1") (pintype "passive"))
    )
    (net (code "408") (name "unconnected-(JP123-Pad1)") (class "Default")
      (node (ref "JP123") (pin "1") (pinfunction "1_1") (pintype "passive"))
    )
    (net (code "409") (name "unconnected-(JP124-Pad1)") (class "Default")
      (node (ref "JP124") (pin "1") (pinfunction "1_1") (pintype "passive"))
    )
    (net (code "410") (name "unconnected-(JP125-Pad1)") (class "Default")
      (node (ref "JP125") (pin "1") (pinfunction "1_1") (pintype "passive"))
    )
    (net (code "411") (name "unconnected-(JP126-Pad1)") (class "Default")
      (node (ref "JP126") (pin "1") (pinfunction "1_1") (pintype "passive"))
    )
    (net (code "412") (name "unconnected-(JP127-Pad1)") (class "Default")
      (node (ref "JP127") (pin "1") (pinfunction "1_1") (pintype "passive"))
    )
    (net (code "413") (name "unconnected-(JP128-Pad1)") (class "Default")
      (node (ref "JP128") (pin "1") (pinfunction "1_1") (pintype "passive"))
    )
    (net (code "414") (name "unconnected-(JP129-Pad1)") (class "Default")
      (node (ref "JP129") (pin "1") (pinfunction "1_1") (pintype "passive"))
    )
    (net (code "415") (name "unconnected-(JP130-Pad1)") (class "Default")
      (node (ref "JP130") (pin "1") (pinfunction "1_1") (pintype "passive"))
    )
    (net (code "416") (name "unconnected-(JP131-Pad1)") (class "Default")
      (node (ref "JP131") (pin "1") (pinfunction "1_1") (pintype "passive"))
    )
    (net (code "417") (name "unconnected-(JP132-Pad1)") (class "Default")
      (node (ref "JP132") (pin "1") (pinfunction "1_1") (pintype "passive"))
    )
    (net (code "418") (name "{slash}BUSACK") (class "Default")
      (node (ref "J1") (pin "A31") (pinfunction "A31_A31") (pintype "passive"))
    )
    (net (code "419") (name "{slash}BUSRQ") (class "Default")
      (node (ref "J1") (pin "A11") (pinfunction "A11_A11") (pintype "passive"))
    )
    (net (code "420") (name "{slash}HALT") (class "Default")
      (node (ref "J1") (pin "C25") (pinfunction "C25_C25") (pintype "passive"))
    )
    (net (code "421") (name "{slash}INT") (class "Default")
      (node (ref "IC6") (pin "2") (pinfunction "1/6_2") (pintype "bidirectional"))
      (node (ref "J1") (pin "C21") (pinfunction "C21_C21") (pintype "passive"))
      (node (ref "R2") (pin "1") (pinfunction "1_1") (pintype "passive"))
    )
    (net (code "422") (name "{slash}NMI") (class "Default")
      (node (ref "IC6") (pin "44") (pinfunction "1/5_44") (pintype "bidirectional"))
      (node (ref "J1") (pin "C20") (pinfunction "C20_C20") (pintype "passive"))
      (node (ref "R1") (pin "1") (pinfunction "1_1") (pintype "passive"))
    )
    (net (code "423") (name "{slash}WAIT") (class "Default")
      (node (ref "IC6") (pin "37") (pinfunction "2/4_37") (pintype "bidirectional"))
      (node (ref "J1") (pin "A10") (pinfunction "A10_A10") (pintype "passive"))
      (node (ref "R3") (pin "1") (pinfunction "1_1") (pintype "passive"))
    )
  )
)
